# Spartan_Edge_Accelerator_Board_v1_0.net
KiCad netlist of a schematic drawn in EAGLE
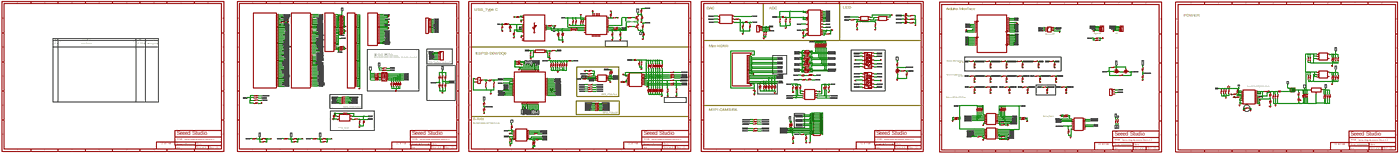
[diagram p0: schematic, sheet 1, overview]
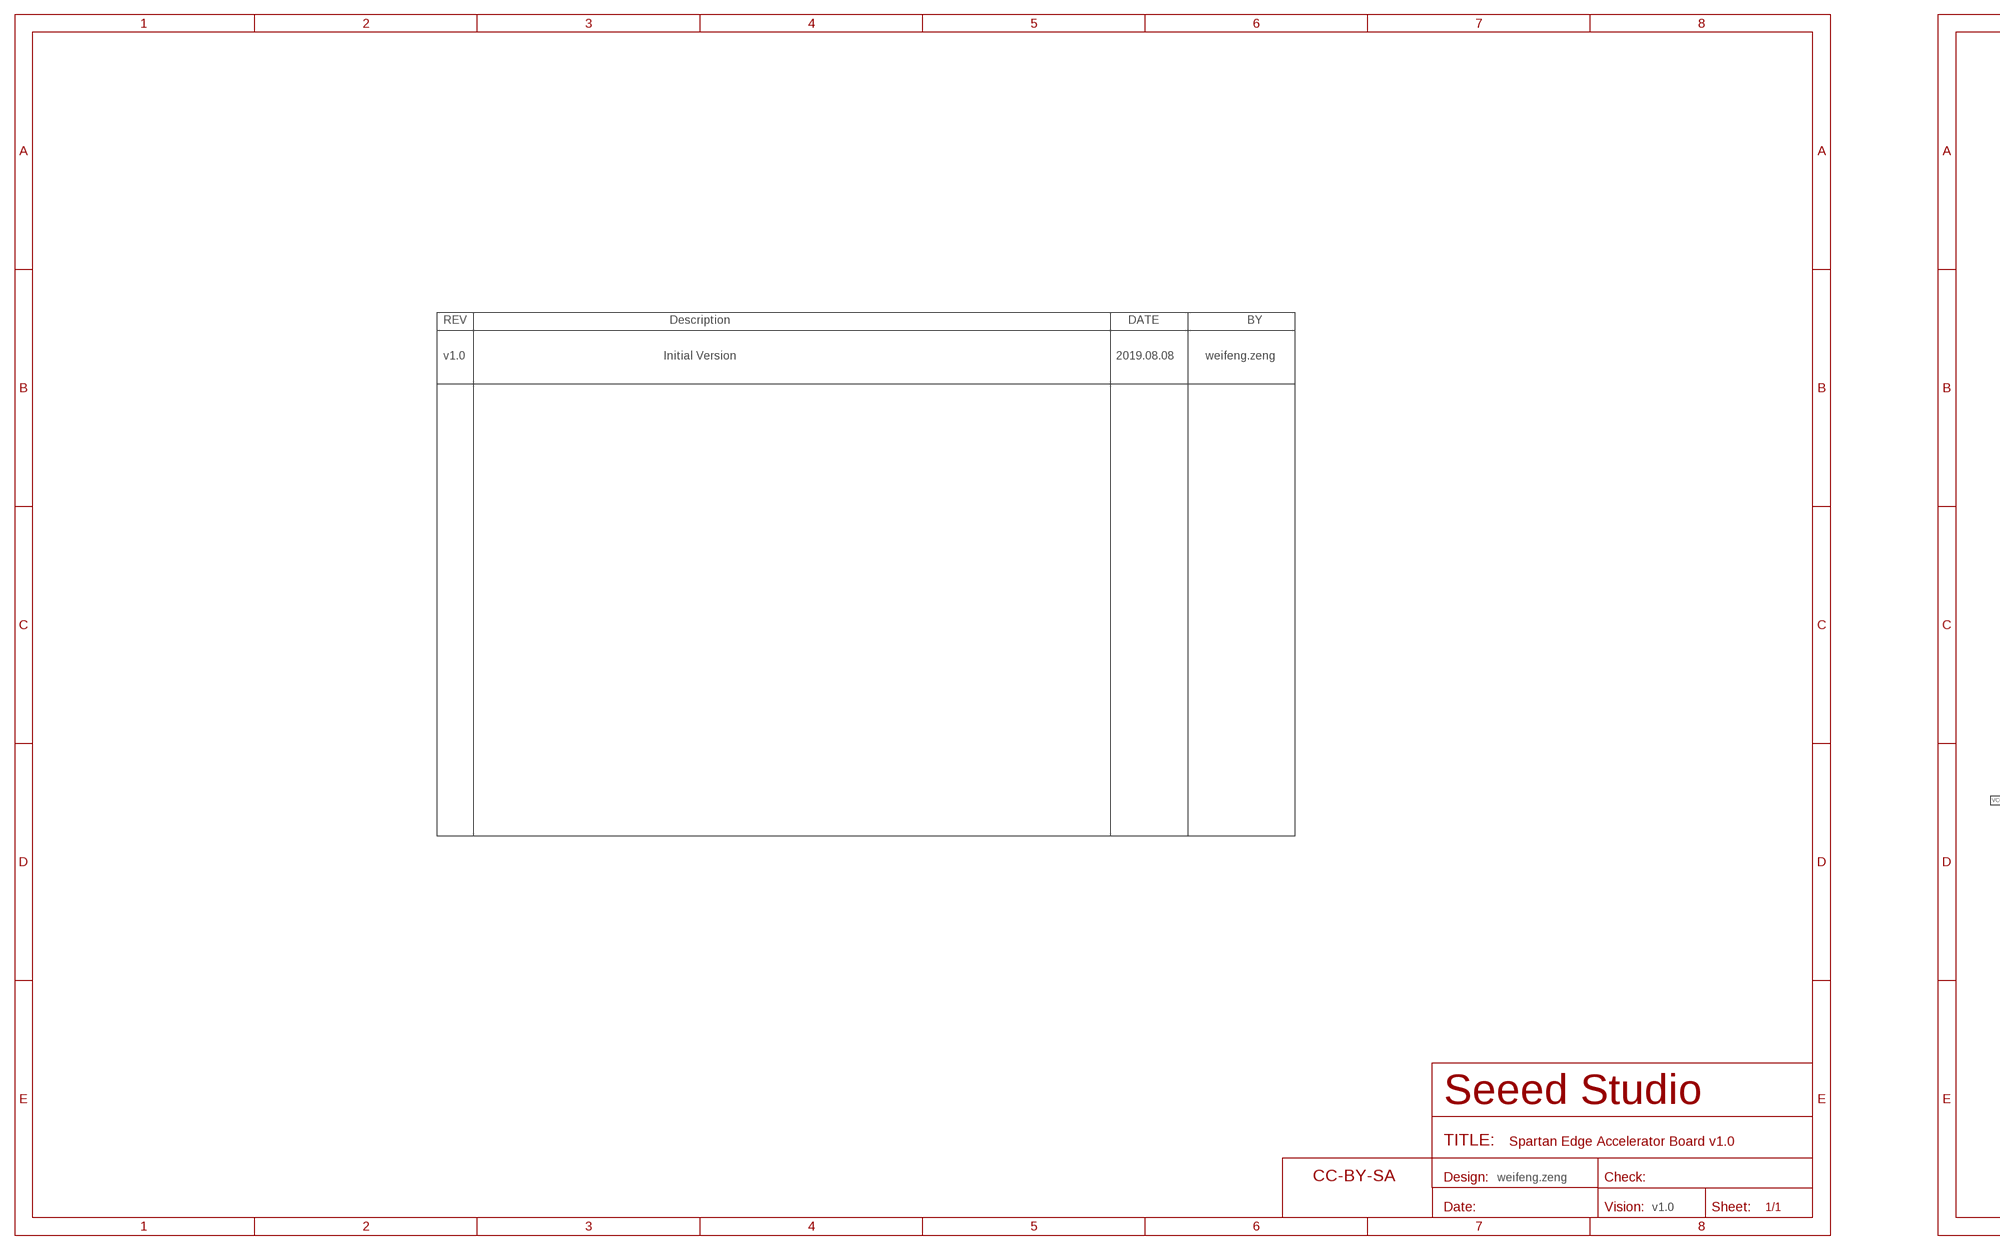
[diagram p1: schematic, sheet 1, part 1 of 7]
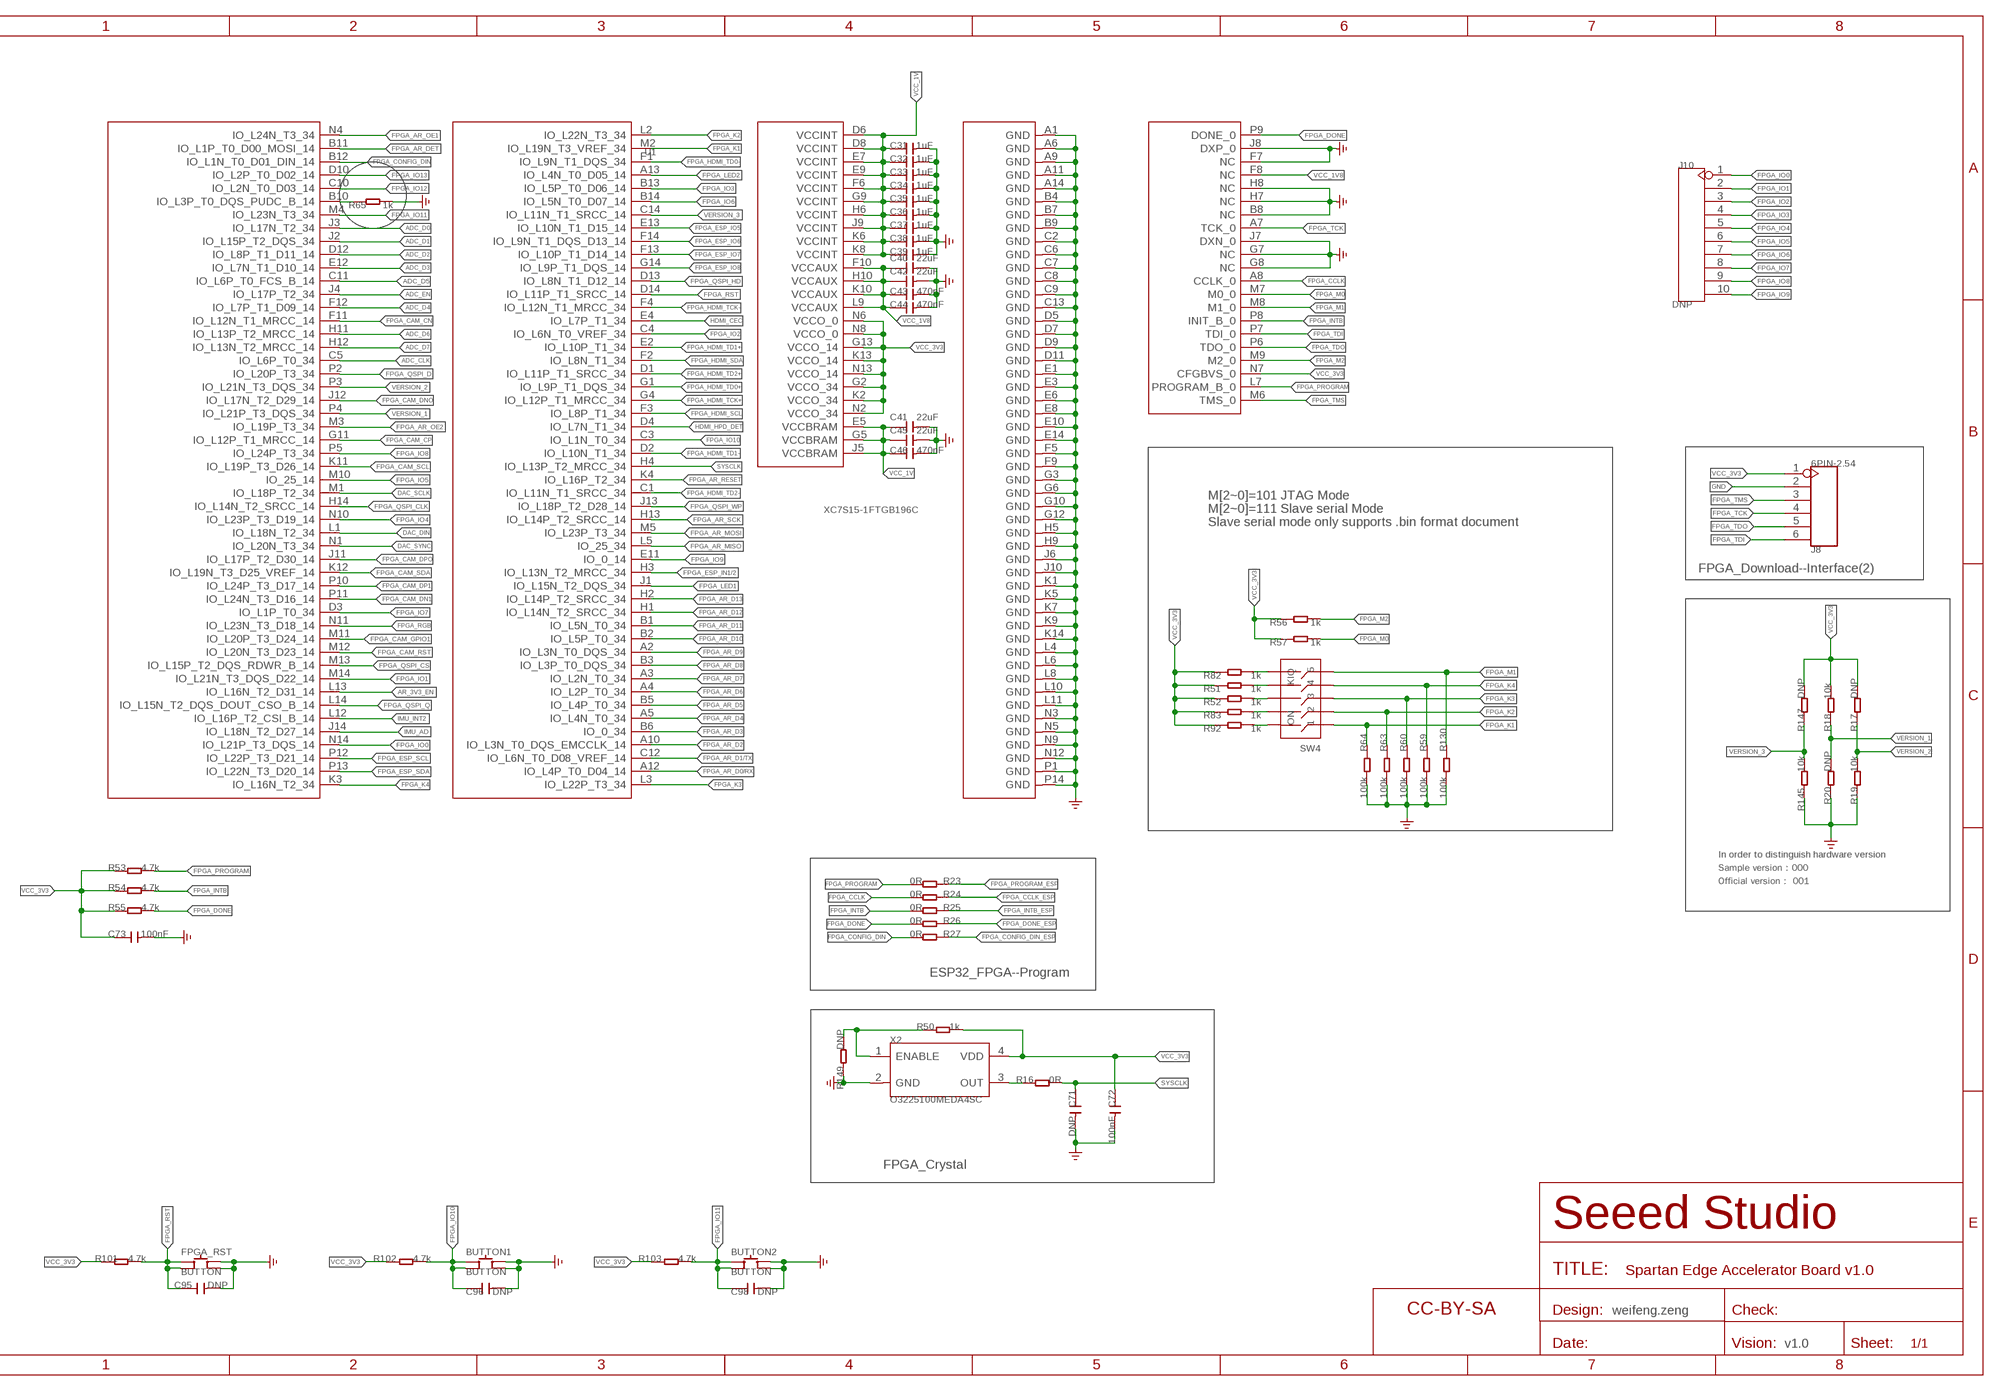
[diagram p2: schematic, sheet 1, part 2 of 7]
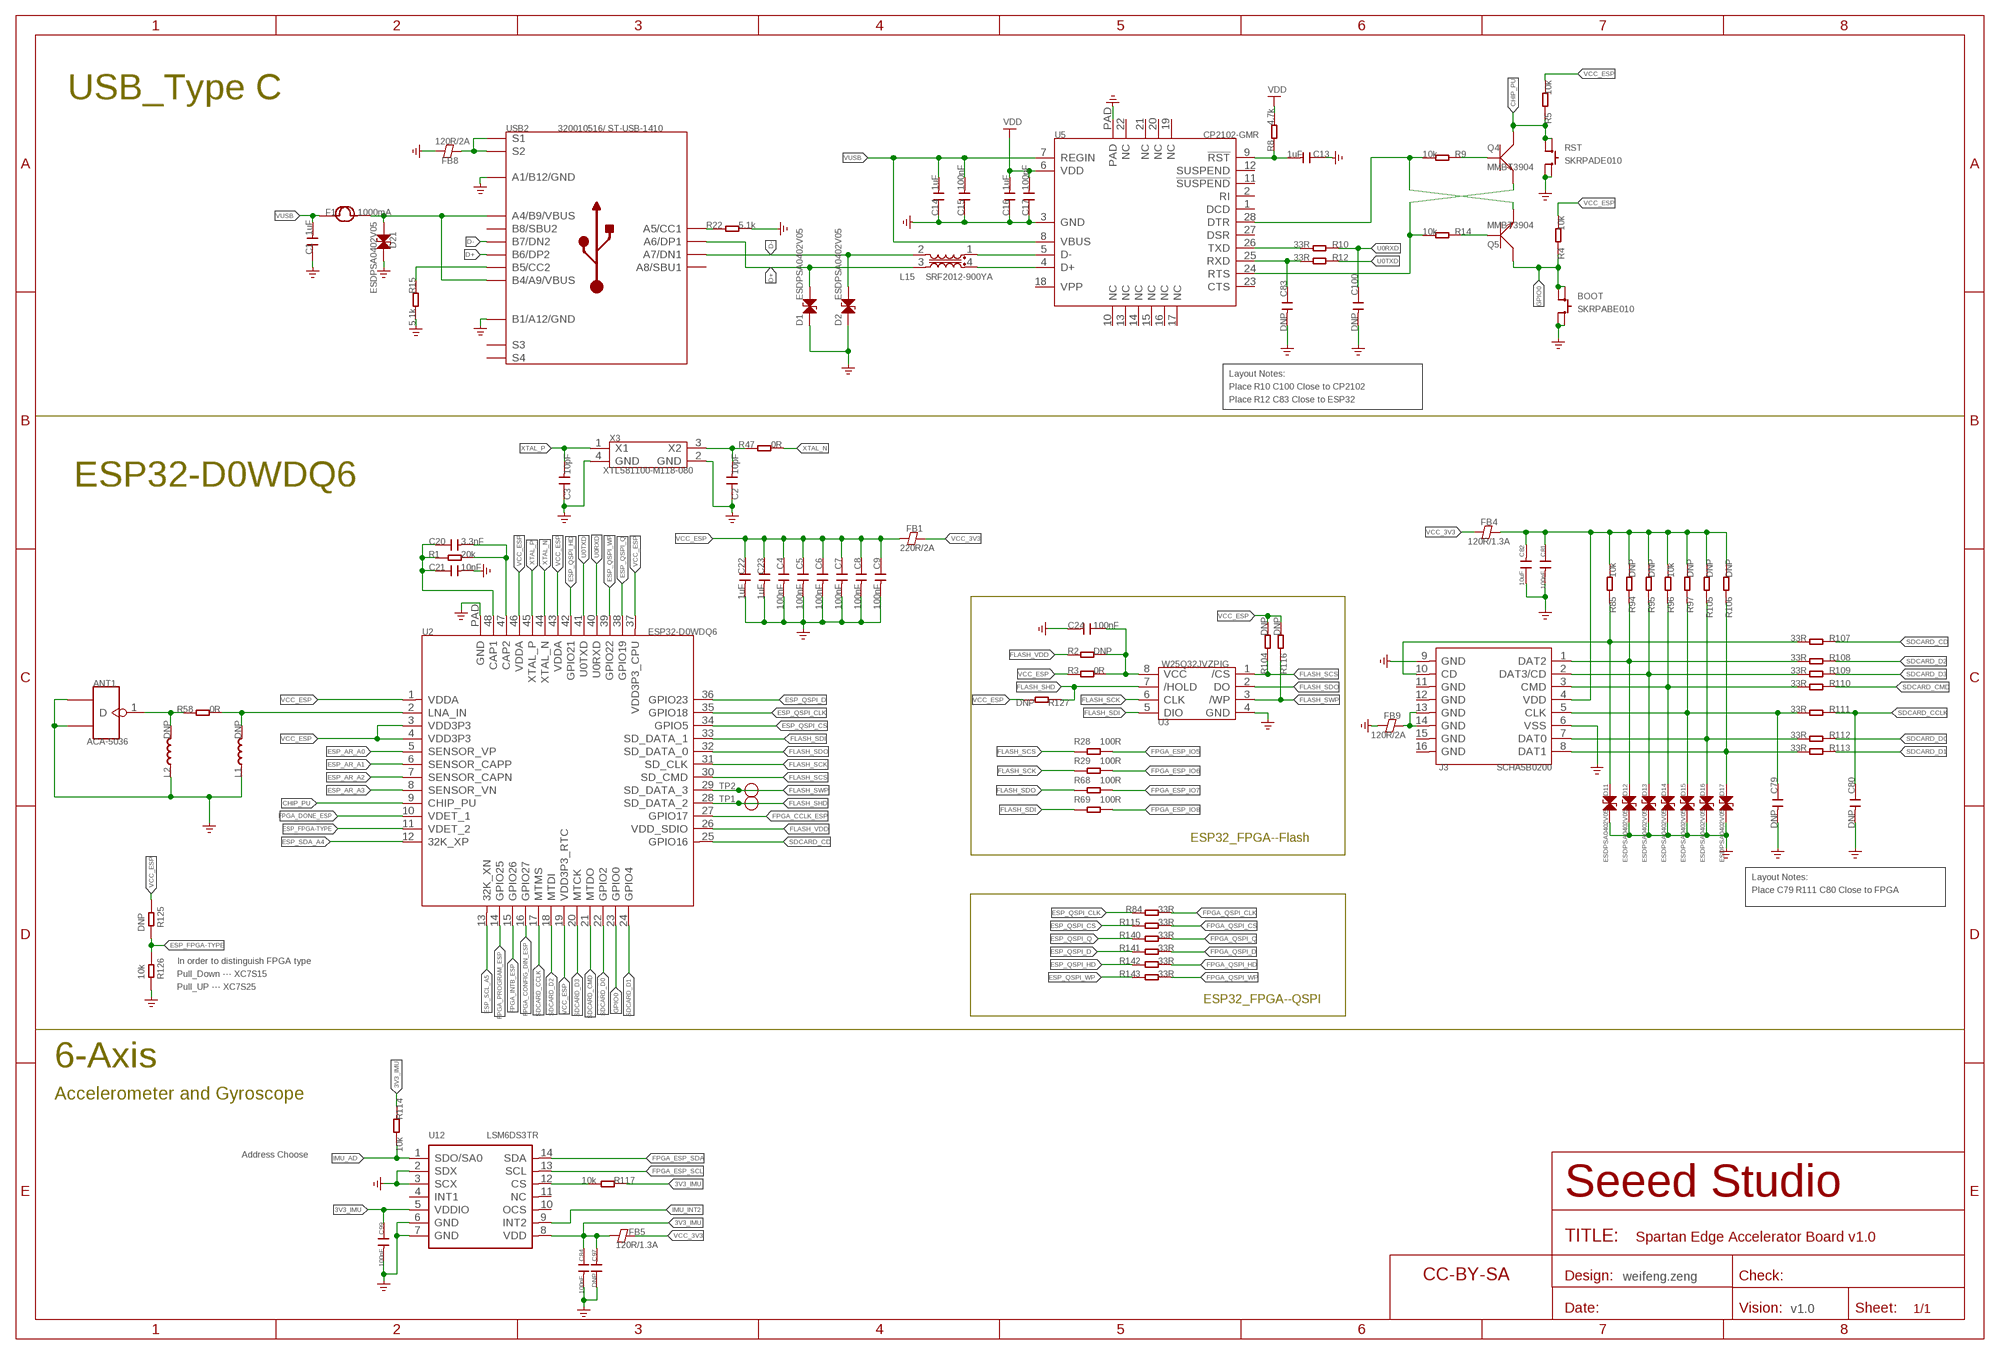
[diagram p3: schematic, sheet 1, part 3 of 7]
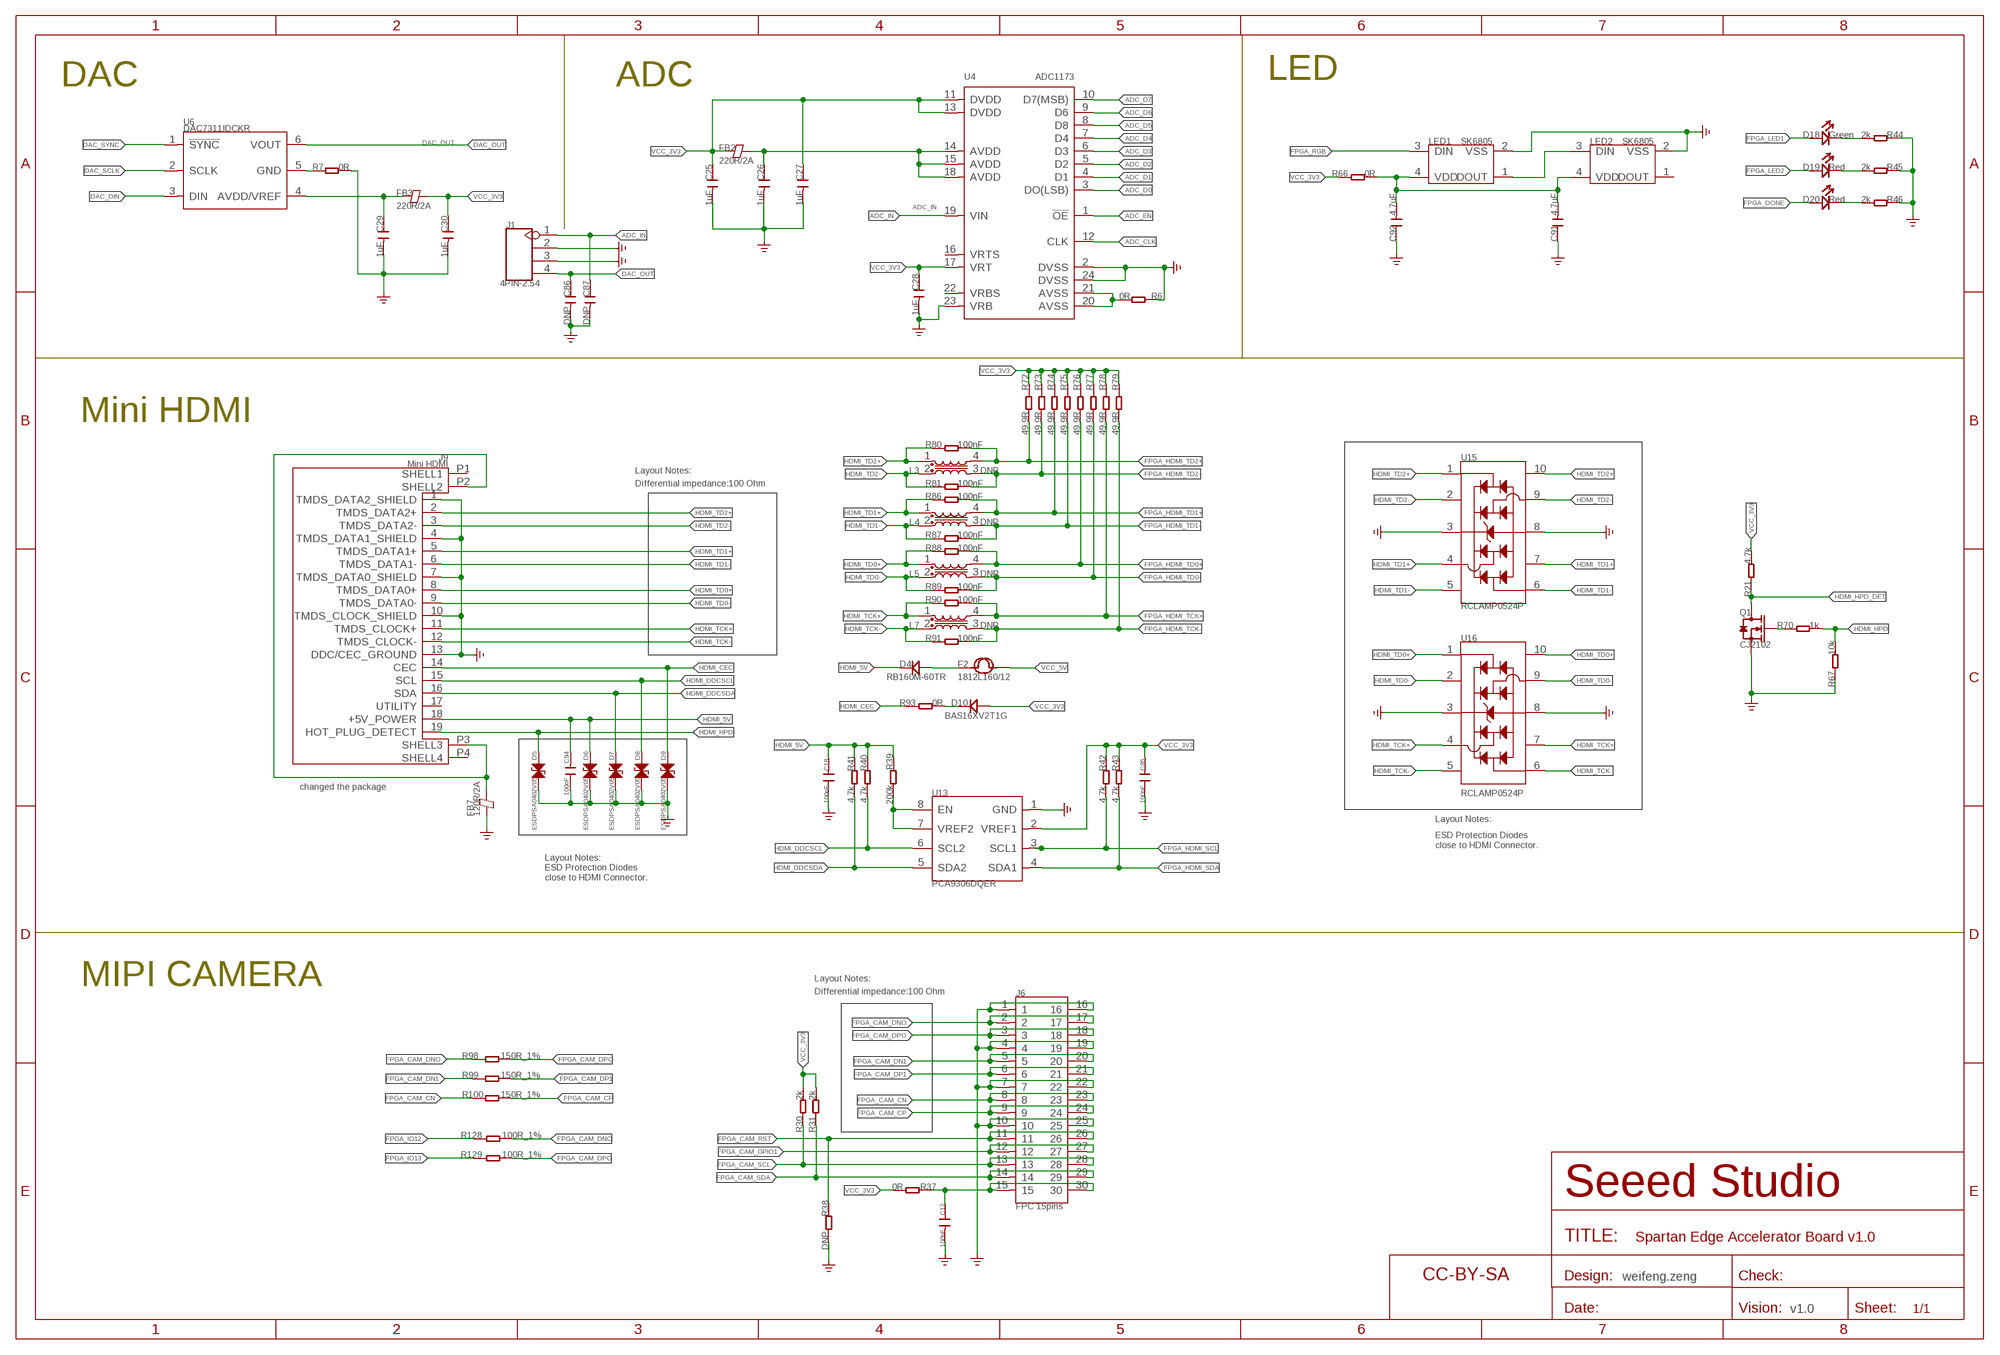
[diagram p4: schematic, sheet 1, part 4 of 7]
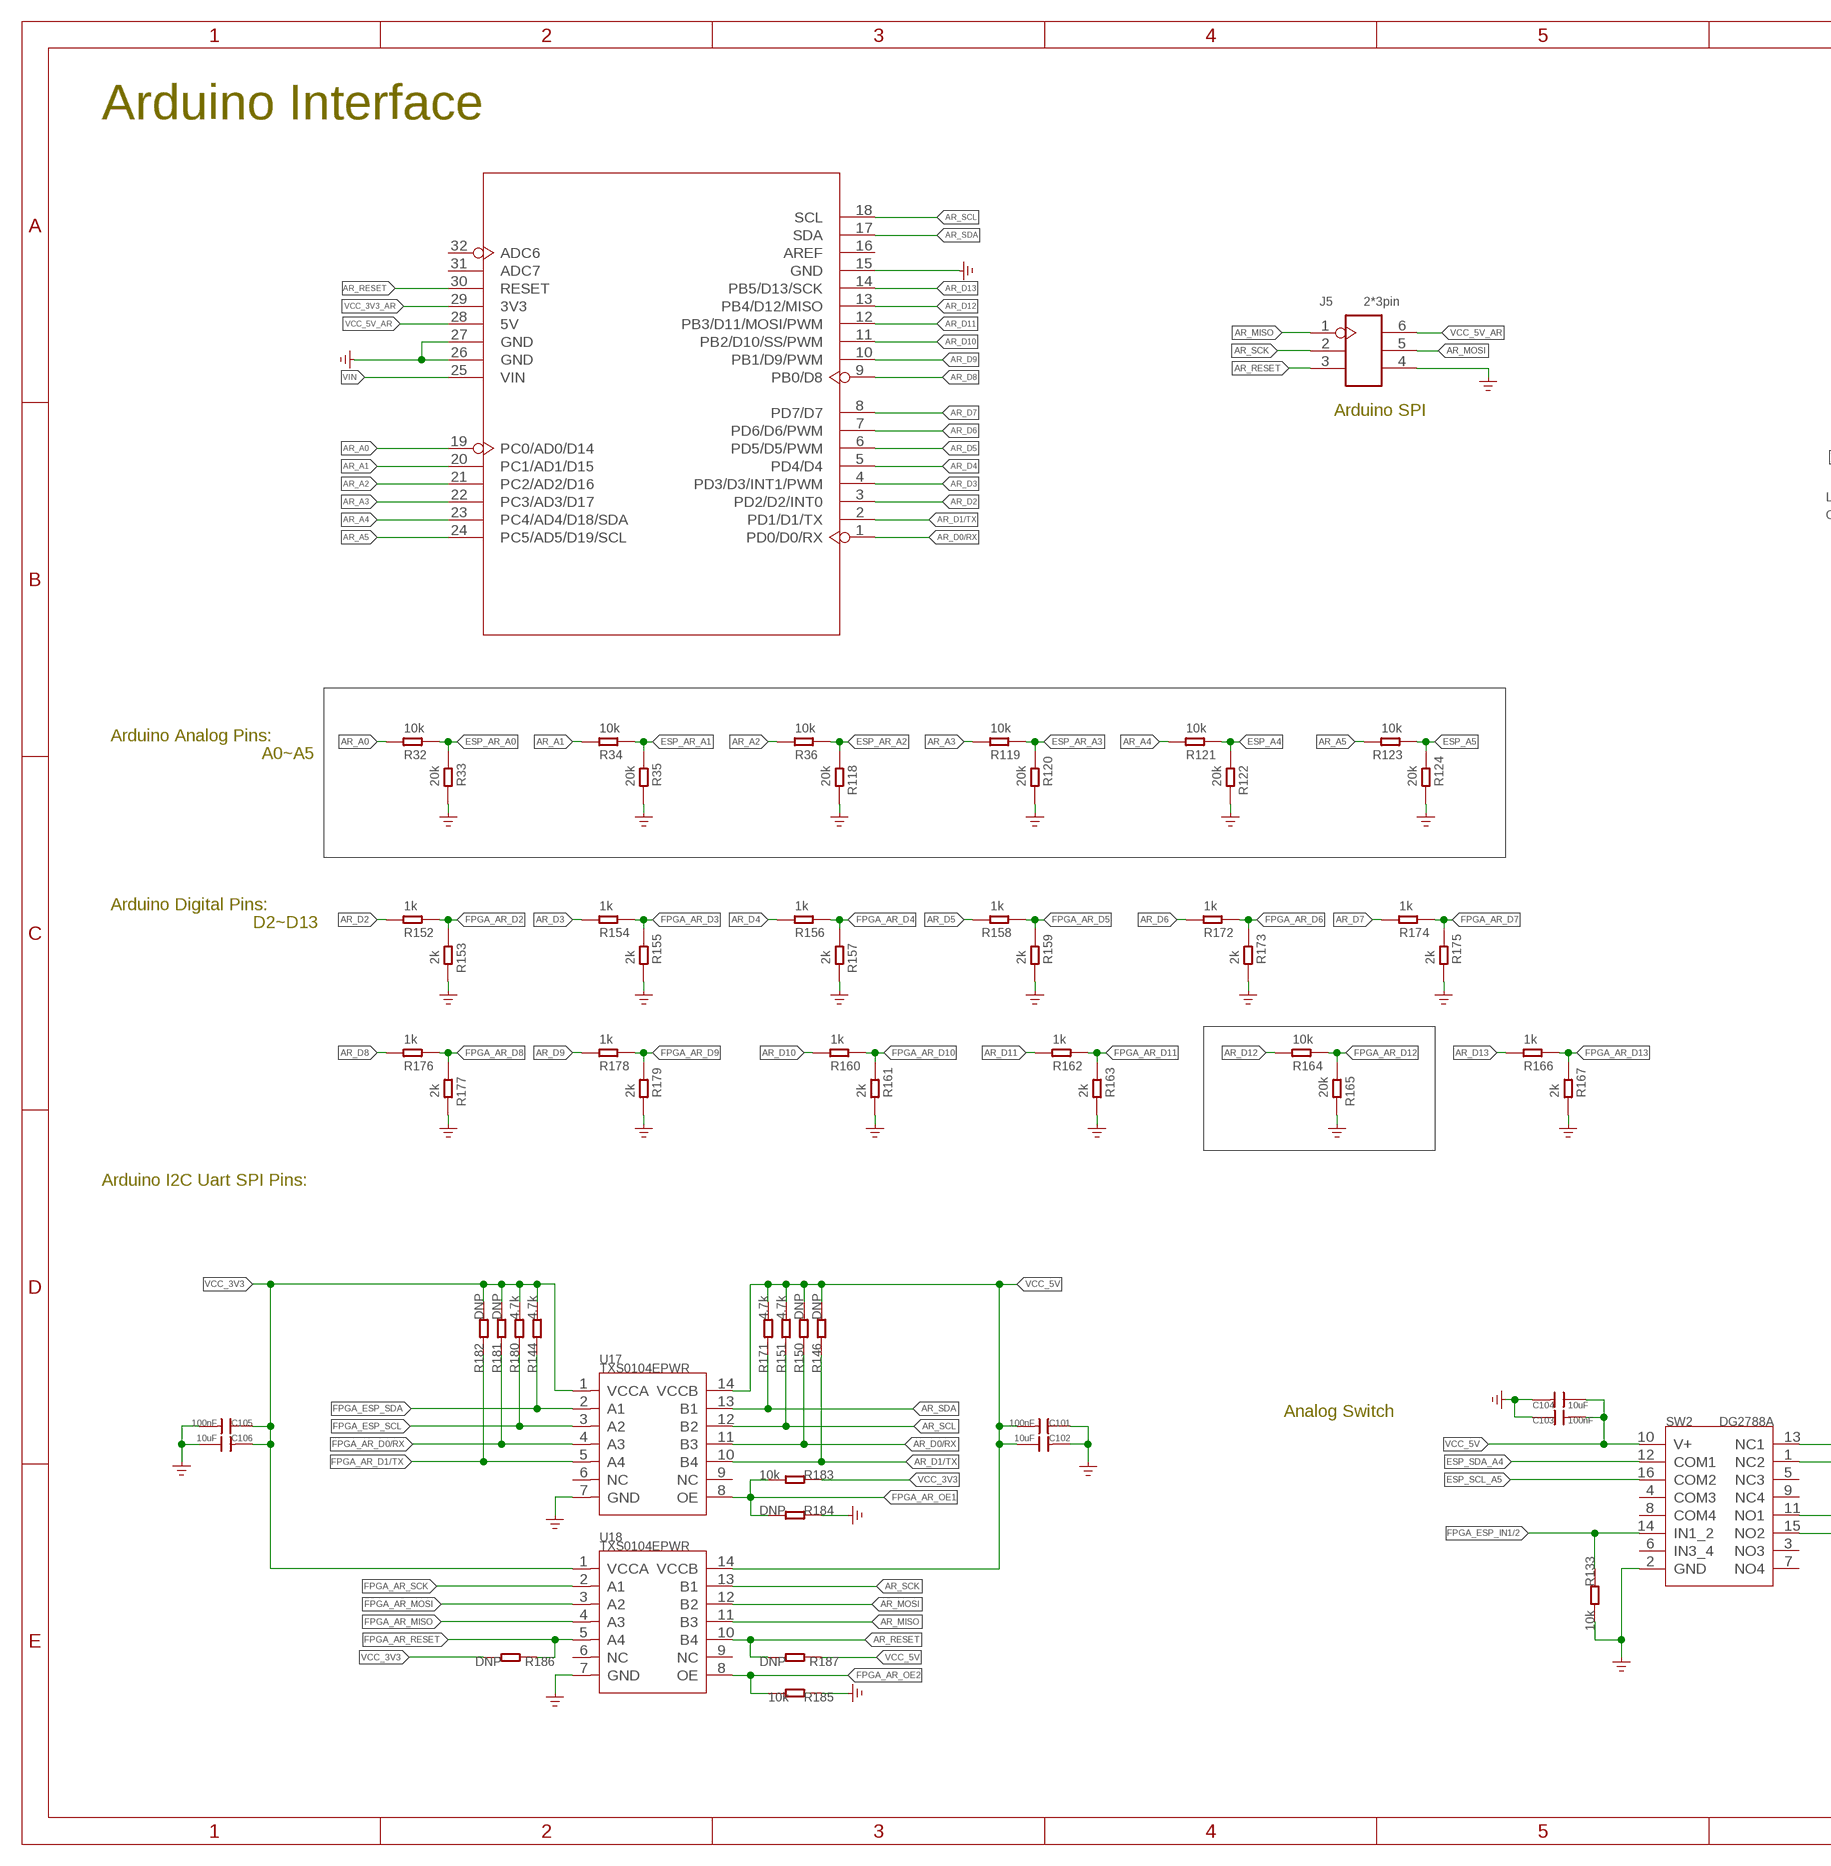
[diagram p5: schematic, sheet 1, part 5 of 7]
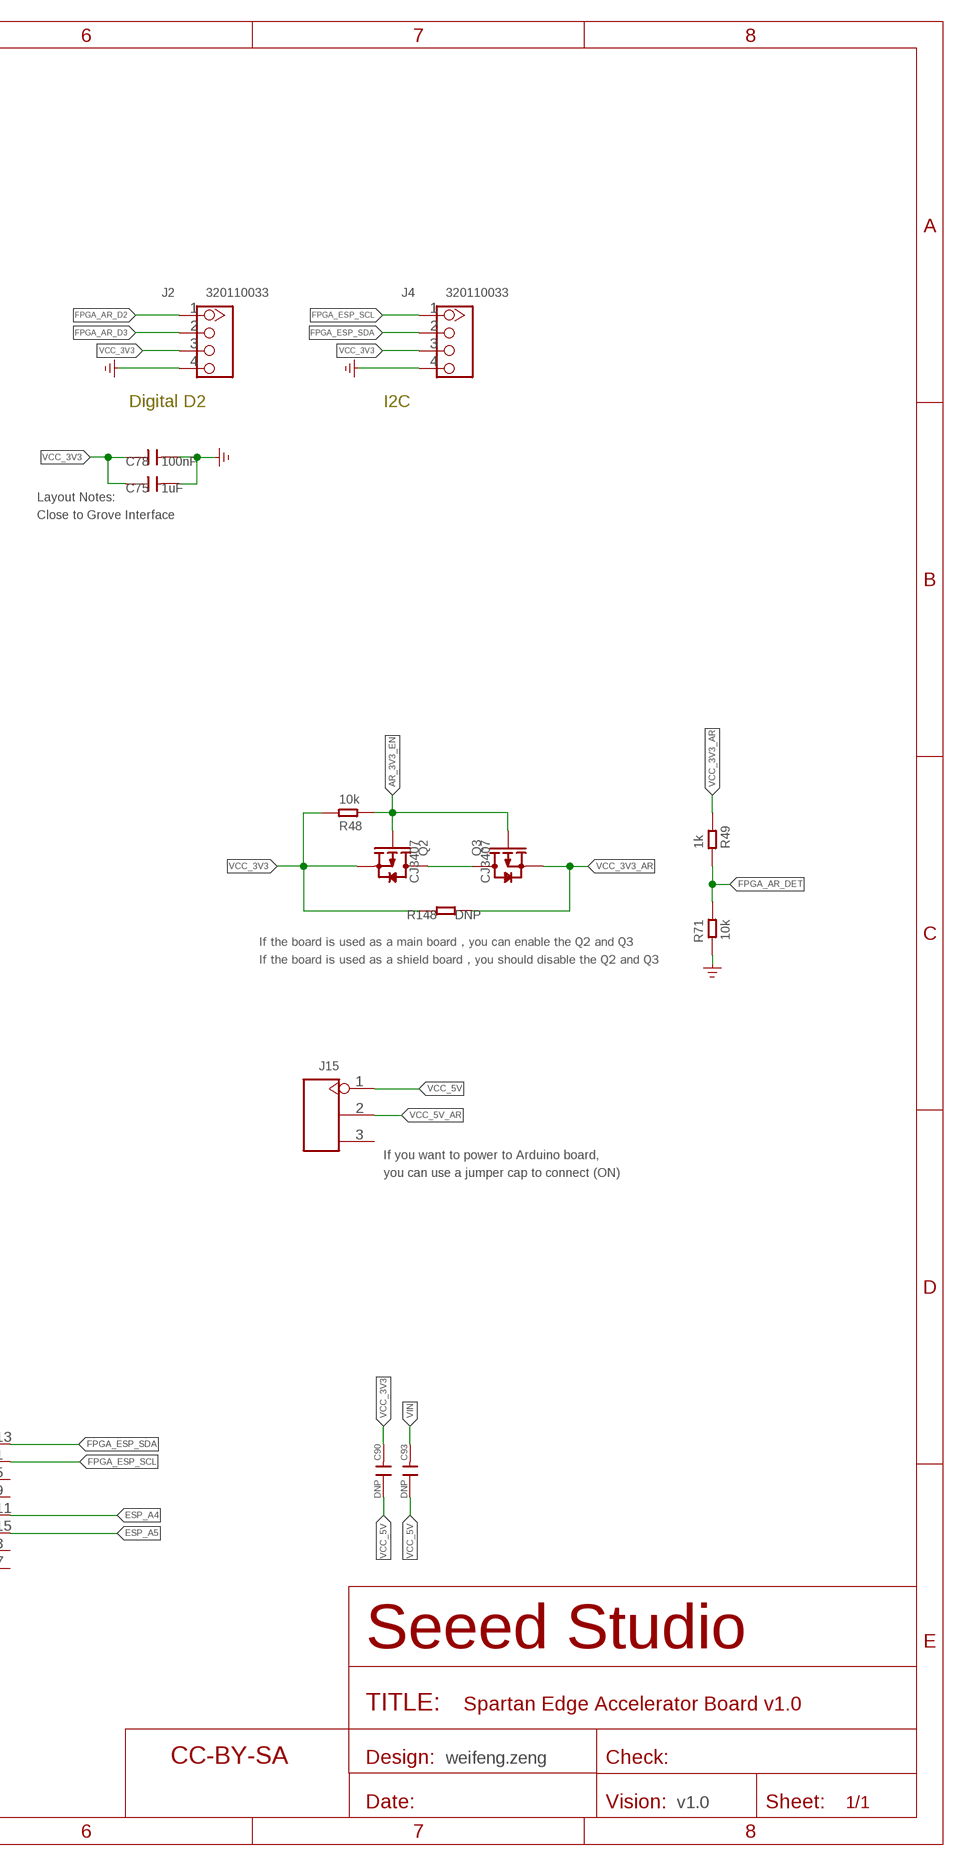
[diagram p6: schematic, sheet 1, part 6 of 7]
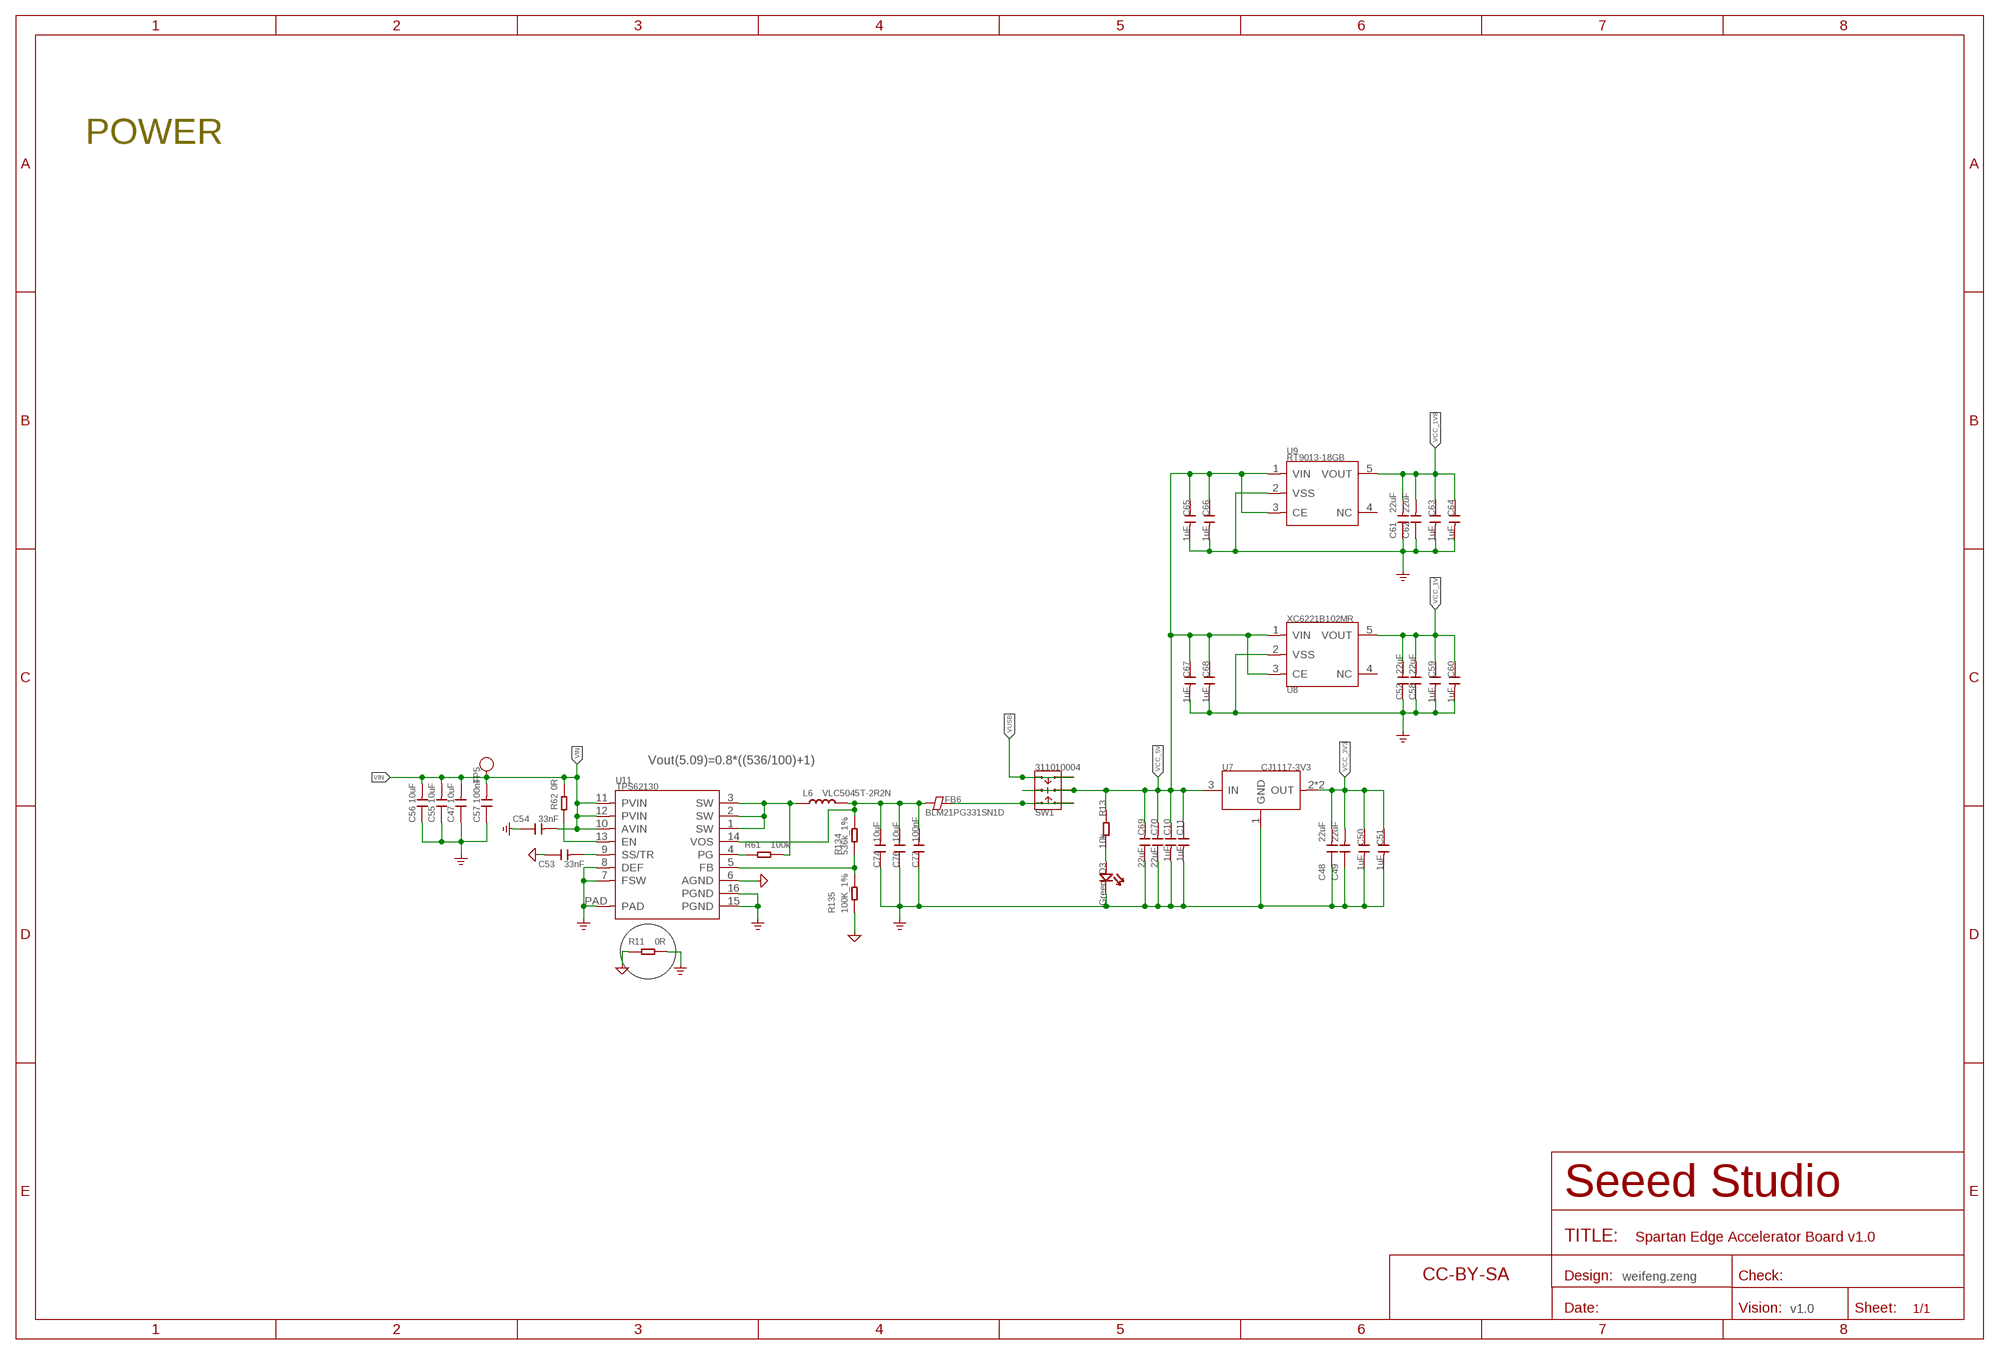
[diagram p7: schematic, sheet 1, part 7 of 7]

(export (version "E")
  (design (tool "Eeschema 10.0.6"))
  (components
    (comp (ref "ANT1")
      (value "ACA-5036")
      (footprint "eagle-import:ANT3-SMD-5.2X3.7X0.7MM")
      (fields (field (name "MPN") "ACD-5036-A3-CC-S"))
      (libsource (lib "eagle-import") (part "ANTENNA-ACD5036"))
    )
    (comp (ref "BOOT")
      (value "SKRPABE010")
      (footprint "eagle-import:SW4P-SMD-4.5X3.2X2.5MM")
      (libsource (lib "eagle-import") (part "BUTTON-4P-4.5X3.2"))
    )
    (comp (ref "BUTTON1")
      (value "BUTTON")
      (footprint "eagle-import:SW4P-SMD-4.5X3.2X2.5MM")
      (libsource (lib "eagle-import") (part "BUTTON-4P-4.5X3.2"))
    )
    (comp (ref "BUTTON2")
      (value "BUTTON")
      (footprint "eagle-import:SW4P-SMD-4.5X3.2X2.5MM")
      (libsource (lib "eagle-import") (part "BUTTON-4P-4.5X3.2"))
    )
    (comp (ref "C1")
      (value "1uF")
      (footprint "eagle-import:C0402")
      (libsource (lib "eagle-import") (part "CAP-0402"))
    )
    (comp (ref "C2")
      (value "10pF")
      (footprint "eagle-import:C0402")
      (libsource (lib "eagle-import") (part "CAP-0402"))
    )
    (comp (ref "C3")
      (value "10pF")
      (footprint "eagle-import:C0402")
      (libsource (lib "eagle-import") (part "CAP-0402"))
    )
    (comp (ref "C4")
      (value "100nF")
      (footprint "eagle-import:C0402")
      (libsource (lib "eagle-import") (part "CAP-0402"))
    )
    (comp (ref "C5")
      (value "100nF")
      (footprint "eagle-import:C0402")
      (libsource (lib "eagle-import") (part "CAP-0402"))
    )
    (comp (ref "C6")
      (value "100nF")
      (footprint "eagle-import:C0402")
      (libsource (lib "eagle-import") (part "CAP-0402"))
    )
    (comp (ref "C7")
      (value "100nF")
      (footprint "eagle-import:C0402")
      (libsource (lib "eagle-import") (part "CAP-0402"))
    )
    (comp (ref "C8")
      (value "100nF")
      (footprint "eagle-import:C0402")
      (libsource (lib "eagle-import") (part "CAP-0402"))
    )
    (comp (ref "C9")
      (value "100nF")
      (footprint "eagle-import:C0402")
      (libsource (lib "eagle-import") (part "CAP-0402"))
    )
    (comp (ref "C10")
      (value "1uF")
      (footprint "eagle-import:C0402")
      (libsource (lib "eagle-import") (part "CAP-0402"))
    )
    (comp (ref "C11")
      (value "1uF")
      (footprint "eagle-import:C0402")
      (libsource (lib "eagle-import") (part "CAP-0402"))
    )
    (comp (ref "C12")
      (value "100nF")
      (footprint "eagle-import:C0402")
      (libsource (lib "eagle-import") (part "CAP-0402"))
    )
    (comp (ref "C13")
      (value "1uF")
      (footprint "eagle-import:C0402")
      (libsource (lib "eagle-import") (part "CAP-0402"))
    )
    (comp (ref "C14")
      (value "1uF")
      (footprint "eagle-import:C0402")
      (libsource (lib "eagle-import") (part "CAP-0402"))
    )
    (comp (ref "C15")
      (value "100nF")
      (footprint "eagle-import:C0402")
      (libsource (lib "eagle-import") (part "CAP-0402"))
    )
    (comp (ref "C16")
      (value "1uF")
      (footprint "eagle-import:C0402")
      (libsource (lib "eagle-import") (part "CAP-0402"))
    )
    (comp (ref "C17")
      (value "100nF")
      (footprint "eagle-import:C0402")
      (libsource (lib "eagle-import") (part "CAP-0402"))
    )
    (comp (ref "C18")
      (value "100nF")
      (footprint "eagle-import:C0603")
      (libsource (lib "eagle-import") (part "CAP-0603"))
    )
    (comp (ref "C20")
      (value "3.3nF")
      (footprint "eagle-import:C0402")
      (libsource (lib "eagle-import") (part "CAP-0402"))
    )
    (comp (ref "C21")
      (value "10nF")
      (footprint "eagle-import:C0402")
      (libsource (lib "eagle-import") (part "CAP-0402"))
    )
    (comp (ref "C22")
      (value "1uF")
      (footprint "eagle-import:C0402")
      (libsource (lib "eagle-import") (part "CAP-0402"))
    )
    (comp (ref "C23")
      (value "1uF")
      (footprint "eagle-import:C0402")
      (libsource (lib "eagle-import") (part "CAP-0402"))
    )
    (comp (ref "C24")
      (value "100nF")
      (footprint "eagle-import:C0402")
      (libsource (lib "eagle-import") (part "CAP-0402"))
    )
    (comp (ref "C25")
      (value "1uF")
      (footprint "eagle-import:C0402")
      (libsource (lib "eagle-import") (part "CAP-0402"))
    )
    (comp (ref "C26")
      (value "1uF")
      (footprint "eagle-import:C0402")
      (libsource (lib "eagle-import") (part "CAP-0402"))
    )
    (comp (ref "C27")
      (value "1uF")
      (footprint "eagle-import:C0402")
      (libsource (lib "eagle-import") (part "CAP-0402"))
    )
    (comp (ref "C28")
      (value "1uF")
      (footprint "eagle-import:C0402")
      (libsource (lib "eagle-import") (part "CAP-0402"))
    )
    (comp (ref "C29")
      (value "1uF")
      (footprint "eagle-import:C0402")
      (libsource (lib "eagle-import") (part "CAP-0402"))
    )
    (comp (ref "C30")
      (value "1uF")
      (footprint "eagle-import:C0402")
      (libsource (lib "eagle-import") (part "CAP-0402"))
    )
    (comp (ref "C31")
      (value "1uF")
      (footprint "eagle-import:C0402")
      (libsource (lib "eagle-import") (part "CAP-0402"))
    )
    (comp (ref "C32")
      (value "1uF")
      (footprint "eagle-import:C0402")
      (libsource (lib "eagle-import") (part "CAP-0402"))
    )
    (comp (ref "C33")
      (value "1uF")
      (footprint "eagle-import:C0402")
      (libsource (lib "eagle-import") (part "CAP-0402"))
    )
    (comp (ref "C34")
      (value "1uF")
      (footprint "eagle-import:C0402")
      (libsource (lib "eagle-import") (part "CAP-0402"))
    )
    (comp (ref "C35")
      (value "1uF")
      (footprint "eagle-import:C0402")
      (libsource (lib "eagle-import") (part "CAP-0402"))
    )
    (comp (ref "C36")
      (value "1uF")
      (footprint "eagle-import:C0402")
      (libsource (lib "eagle-import") (part "CAP-0402"))
    )
    (comp (ref "C37")
      (value "1uF")
      (footprint "eagle-import:C0402")
      (libsource (lib "eagle-import") (part "CAP-0402"))
    )
    (comp (ref "C38")
      (value "1uF")
      (footprint "eagle-import:C0402")
      (libsource (lib "eagle-import") (part "CAP-0402"))
    )
    (comp (ref "C39")
      (value "1uF")
      (footprint "eagle-import:C0402")
      (libsource (lib "eagle-import") (part "CAP-0402"))
    )
    (comp (ref "C40")
      (value "22uF")
      (footprint "eagle-import:C1206")
      (libsource (lib "eagle-import") (part "CAP-1206"))
    )
    (comp (ref "C41")
      (value "22uF")
      (footprint "eagle-import:C1206")
      (libsource (lib "eagle-import") (part "CAP-1206"))
    )
    (comp (ref "C42")
      (value "22uF")
      (footprint "eagle-import:C1206")
      (libsource (lib "eagle-import") (part "CAP-1206"))
    )
    (comp (ref "C43")
      (value "470nF")
      (footprint "eagle-import:C0402")
      (libsource (lib "eagle-import") (part "CAP-0402"))
    )
    (comp (ref "C44")
      (value "470nF")
      (footprint "eagle-import:C0402")
      (libsource (lib "eagle-import") (part "CAP-0402"))
    )
    (comp (ref "C45")
      (value "22uF")
      (footprint "eagle-import:C1206")
      (libsource (lib "eagle-import") (part "CAP-1206"))
    )
    (comp (ref "C46")
      (value "470nF")
      (footprint "eagle-import:C0402")
      (libsource (lib "eagle-import") (part "CAP-0402"))
    )
    (comp (ref "C47")
      (value "10uF")
      (footprint "eagle-import:C0805")
      (libsource (lib "eagle-import") (part "CAP-0805"))
    )
    (comp (ref "C48")
      (value "22uF")
      (footprint "eagle-import:C1206")
      (libsource (lib "eagle-import") (part "CAP-1206"))
    )
    (comp (ref "C49")
      (value "22uF")
      (footprint "eagle-import:C1206")
      (libsource (lib "eagle-import") (part "CAP-1206"))
    )
    (comp (ref "C50")
      (value "1uF")
      (footprint "eagle-import:C0402")
      (libsource (lib "eagle-import") (part "CAP-0402"))
    )
    (comp (ref "C51")
      (value "1uF")
      (footprint "eagle-import:C0402")
      (libsource (lib "eagle-import") (part "CAP-0402"))
    )
    (comp (ref "C52")
      (value "22uF")
      (footprint "eagle-import:C1206")
      (libsource (lib "eagle-import") (part "CAP-1206"))
    )
    (comp (ref "C53")
      (value "33nF")
      (footprint "eagle-import:C0603")
      (libsource (lib "eagle-import") (part "CAP-0603"))
    )
    (comp (ref "C54")
      (value "33nF")
      (footprint "eagle-import:C0603")
      (libsource (lib "eagle-import") (part "CAP-0603"))
    )
    (comp (ref "C55")
      (value "10uF")
      (footprint "eagle-import:C0805")
      (libsource (lib "eagle-import") (part "CAP-0805"))
    )
    (comp (ref "C56")
      (value "10uF")
      (footprint "eagle-import:C0805")
      (libsource (lib "eagle-import") (part "CAP-0805"))
    )
    (comp (ref "C57")
      (value "100nF")
      (footprint "eagle-import:C0603")
      (libsource (lib "eagle-import") (part "CAP-0603"))
    )
    (comp (ref "C58")
      (value "22uF")
      (footprint "eagle-import:C1206")
      (libsource (lib "eagle-import") (part "CAP-1206"))
    )
    (comp (ref "C59")
      (value "1uF")
      (footprint "eagle-import:C0402")
      (libsource (lib "eagle-import") (part "CAP-0402"))
    )
    (comp (ref "C60")
      (value "1uF")
      (footprint "eagle-import:C0402")
      (libsource (lib "eagle-import") (part "CAP-0402"))
    )
    (comp (ref "C61")
      (value "22uF")
      (footprint "eagle-import:C1206")
      (libsource (lib "eagle-import") (part "CAP-1206"))
    )
    (comp (ref "C62")
      (value "22uF")
      (footprint "eagle-import:C1206")
      (libsource (lib "eagle-import") (part "CAP-1206"))
    )
    (comp (ref "C63")
      (value "1uF")
      (footprint "eagle-import:C0402")
      (libsource (lib "eagle-import") (part "CAP-0402"))
    )
    (comp (ref "C64")
      (value "1uF")
      (footprint "eagle-import:C0402")
      (libsource (lib "eagle-import") (part "CAP-0402"))
    )
    (comp (ref "C65")
      (value "1uF")
      (footprint "eagle-import:C0402")
      (libsource (lib "eagle-import") (part "CAP-0402"))
    )
    (comp (ref "C66")
      (value "1uF")
      (footprint "eagle-import:C0402")
      (libsource (lib "eagle-import") (part "CAP-0402"))
    )
    (comp (ref "C67")
      (value "1uF")
      (footprint "eagle-import:C0402")
      (libsource (lib "eagle-import") (part "CAP-0402"))
    )
    (comp (ref "C68")
      (value "1uF")
      (footprint "eagle-import:C0402")
      (libsource (lib "eagle-import") (part "CAP-0402"))
    )
    (comp (ref "C69")
      (value "22uF")
      (footprint "eagle-import:C1206")
      (libsource (lib "eagle-import") (part "CAP-1206"))
    )
    (comp (ref "C70")
      (value "22uF")
      (footprint "eagle-import:C1206")
      (libsource (lib "eagle-import") (part "CAP-1206"))
    )
    (comp (ref "C71")
      (value "DNP")
      (footprint "eagle-import:C0402")
      (libsource (lib "eagle-import") (part "CAP-0402"))
    )
    (comp (ref "C72")
      (value "100nF")
      (footprint "eagle-import:C0402")
      (libsource (lib "eagle-import") (part "CAP-0402"))
    )
    (comp (ref "C73")
      (value "100nF")
      (footprint "eagle-import:C0402")
      (libsource (lib "eagle-import") (part "CAP-0402"))
    )
    (comp (ref "C74")
      (value "10uF")
      (footprint "eagle-import:C0805")
      (libsource (lib "eagle-import") (part "CAP-0805"))
    )
    (comp (ref "C75")
      (value "1uF")
      (footprint "eagle-import:C0402")
      (libsource (lib "eagle-import") (part "CAP-0402"))
    )
    (comp (ref "C76")
      (value "10uF")
      (footprint "eagle-import:C0805")
      (libsource (lib "eagle-import") (part "CAP-0805"))
    )
    (comp (ref "C77")
      (value "100nF")
      (footprint "eagle-import:C0603")
      (libsource (lib "eagle-import") (part "CAP-0603"))
    )
    (comp (ref "C78")
      (value "100nF")
      (footprint "eagle-import:C0402")
      (libsource (lib "eagle-import") (part "CAP-0402"))
    )
    (comp (ref "C79")
      (value "DNP")
      (footprint "eagle-import:C0402")
      (libsource (lib "eagle-import") (part "CAP-0402"))
    )
    (comp (ref "C80")
      (value "DNP")
      (footprint "eagle-import:C0402")
      (libsource (lib "eagle-import") (part "CAP-0402"))
    )
    (comp (ref "C81")
      (value "100nF")
      (footprint "eagle-import:C0402")
      (libsource (lib "eagle-import") (part "CAP-0402"))
    )
    (comp (ref "C82")
      (value "10uF")
      (footprint "eagle-import:C0603")
      (libsource (lib "eagle-import") (part "CAP-0603"))
    )
    (comp (ref "C83")
      (value "DNP")
      (footprint "eagle-import:C0402")
      (libsource (lib "eagle-import") (part "CAP-0402"))
    )
    (comp (ref "C84")
      (value "100nF")
      (footprint "eagle-import:C0402")
      (libsource (lib "eagle-import") (part "CAP-0402"))
    )
    (comp (ref "C85")
      (value "100nF")
      (footprint "eagle-import:C0603")
      (libsource (lib "eagle-import") (part "CAP-0603"))
    )
    (comp (ref "C86")
      (value "DNP")
      (footprint "eagle-import:C0402")
      (libsource (lib "eagle-import") (part "CAP-0402"))
    )
    (comp (ref "C87")
      (value "DNP")
      (footprint "eagle-import:C0402")
      (libsource (lib "eagle-import") (part "CAP-0402"))
    )
    (comp (ref "C90")
      (value "DNP")
      (footprint "eagle-import:C0603")
      (libsource (lib "eagle-import") (part "CAP-0603"))
    )
    (comp (ref "C91")
      (value "4.7uF")
      (footprint "eagle-import:C0603")
      (libsource (lib "eagle-import") (part "CAP-0603"))
    )
    (comp (ref "C92")
      (value "4.7uF")
      (footprint "eagle-import:C0603")
      (libsource (lib "eagle-import") (part "CAP-0603"))
    )
    (comp (ref "C93")
      (value "DNP")
      (footprint "eagle-import:C0603")
      (libsource (lib "eagle-import") (part "CAP-0603"))
    )
    (comp (ref "C94")
      (value "100nF")
      (footprint "eagle-import:C0603")
      (libsource (lib "eagle-import") (part "CAP-0603"))
    )
    (comp (ref "C95")
      (value "DNP")
      (footprint "eagle-import:C0402")
      (libsource (lib "eagle-import") (part "CAP-0402"))
    )
    (comp (ref "C96")
      (value "DNP")
      (footprint "eagle-import:C0402")
      (libsource (lib "eagle-import") (part "CAP-0402"))
    )
    (comp (ref "C97")
      (value "DNP")
      (footprint "eagle-import:C0603")
      (libsource (lib "eagle-import") (part "CAP-0603"))
    )
    (comp (ref "C98")
      (value "DNP")
      (footprint "eagle-import:C0402")
      (libsource (lib "eagle-import") (part "CAP-0402"))
    )
    (comp (ref "C99")
      (value "100nF")
      (footprint "eagle-import:C0402")
      (libsource (lib "eagle-import") (part "CAP-0402"))
    )
    (comp (ref "C100")
      (value "DNP")
      (footprint "eagle-import:C0402")
      (libsource (lib "eagle-import") (part "CAP-0402"))
    )
    (comp (ref "C101")
      (value "100nF")
      (footprint "eagle-import:C0402")
      (libsource (lib "eagle-import") (part "CAP-0402"))
    )
    (comp (ref "C102")
      (value "10uF")
      (footprint "eagle-import:C0603")
      (libsource (lib "eagle-import") (part "CAP-0603"))
    )
    (comp (ref "C103")
      (value "100nF")
      (footprint "eagle-import:C0402")
      (libsource (lib "eagle-import") (part "CAP-0402"))
    )
    (comp (ref "C104")
      (value "10uF")
      (footprint "eagle-import:C0603")
      (libsource (lib "eagle-import") (part "CAP-0603"))
    )
    (comp (ref "C105")
      (value "100nF")
      (footprint "eagle-import:C0402")
      (libsource (lib "eagle-import") (part "CAP-0402"))
    )
    (comp (ref "C106")
      (value "10uF")
      (footprint "eagle-import:C0603")
      (libsource (lib "eagle-import") (part "CAP-0603"))
    )
    (comp (ref "D1")
      (value "ESDPSA0402V05")
      (footprint "eagle-import:ESD-0402")
      (libsource (lib "eagle-import") (part "D-ESD-2P-DOUBLE-0402"))
    )
    (comp (ref "D2")
      (value "ESDPSA0402V05")
      (footprint "eagle-import:ESD-0402")
      (libsource (lib "eagle-import") (part "D-ESD-2P-DOUBLE-0402"))
    )
    (comp (ref "D3")
      (value "Green")
      (footprint "eagle-import:LED-0402")
      (libsource (lib "eagle-import") (part "LED-0402"))
    )
    (comp (ref "D4")
      (value "RB160M-60TR")
      (footprint "eagle-import:SOD-123")
      (libsource (lib "eagle-import") (part "DIODE'1206'"))
    )
    (comp (ref "D5")
      (value "ESDPSA0402V05")
      (footprint "eagle-import:ESD-0402")
      (libsource (lib "eagle-import") (part "D-ESD-2P-DOUBLE-0402"))
    )
    (comp (ref "D6")
      (value "ESDPSA0402V05")
      (footprint "eagle-import:ESD-0402")
      (libsource (lib "eagle-import") (part "D-ESD-2P-DOUBLE-0402"))
    )
    (comp (ref "D7")
      (value "ESDPSA0402V05")
      (footprint "eagle-import:ESD-0402")
      (libsource (lib "eagle-import") (part "D-ESD-2P-DOUBLE-0402"))
    )
    (comp (ref "D8")
      (value "ESDPSA0402V05")
      (footprint "eagle-import:ESD-0402")
      (libsource (lib "eagle-import") (part "D-ESD-2P-DOUBLE-0402"))
    )
    (comp (ref "D9")
      (value "ESDPSA0402V05")
      (footprint "eagle-import:ESD-0402")
      (libsource (lib "eagle-import") (part "D-ESD-2P-DOUBLE-0402"))
    )
    (comp (ref "D10")
      (value "BAS16XV2T1G")
      (footprint "eagle-import:SOD-523")
      (libsource (lib "eagle-import") (part "DIODE'0603'"))
    )
    (comp (ref "D11")
      (value "ESDPSA0402V05")
      (footprint "eagle-import:ESD-0402")
      (libsource (lib "eagle-import") (part "D-ESD-2P-DOUBLE-0402"))
    )
    (comp (ref "D12")
      (value "ESDPSA0402V05")
      (footprint "eagle-import:ESD-0402")
      (libsource (lib "eagle-import") (part "D-ESD-2P-DOUBLE-0402"))
    )
    (comp (ref "D13")
      (value "ESDPSA0402V05")
      (footprint "eagle-import:ESD-0402")
      (libsource (lib "eagle-import") (part "D-ESD-2P-DOUBLE-0402"))
    )
    (comp (ref "D14")
      (value "ESDPSA0402V05")
      (footprint "eagle-import:ESD-0402")
      (libsource (lib "eagle-import") (part "D-ESD-2P-DOUBLE-0402"))
    )
    (comp (ref "D15")
      (value "ESDPSA0402V05")
      (footprint "eagle-import:ESD-0402")
      (libsource (lib "eagle-import") (part "D-ESD-2P-DOUBLE-0402"))
    )
    (comp (ref "D16")
      (value "ESDPSA0402V05")
      (footprint "eagle-import:ESD-0402")
      (libsource (lib "eagle-import") (part "D-ESD-2P-DOUBLE-0402"))
    )
    (comp (ref "D17")
      (value "ESDPSA0402V05")
      (footprint "eagle-import:ESD-0402")
      (libsource (lib "eagle-import") (part "D-ESD-2P-DOUBLE-0402"))
    )
    (comp (ref "D18")
      (value "Green")
      (footprint "eagle-import:LED-0402")
      (libsource (lib "eagle-import") (part "LED-0402"))
    )
    (comp (ref "D19")
      (value "Red")
      (footprint "eagle-import:LED-0402")
      (libsource (lib "eagle-import") (part "LED-0402"))
    )
    (comp (ref "D20")
      (value "Red")
      (footprint "eagle-import:LED-0402")
      (libsource (lib "eagle-import") (part "LED-0402"))
    )
    (comp (ref "D21")
      (value "ESDPSA0402V05")
      (footprint "eagle-import:ESD-0402")
      (libsource (lib "eagle-import") (part "D-ESD-2P-DOUBLE-0402"))
    )
    (comp (ref "F1")
      (value "1000mA")
      (footprint "eagle-import:F1206")
      (libsource (lib "eagle-import") (part "FUSE'1206'"))
    )
    (comp (ref "F2")
      (value "1812L160/12")
      (footprint "eagle-import:F1812")
      (libsource (lib "eagle-import") (part "FUSE'1812'"))
    )
    (comp (ref "FB1")
      (value "220R/2A")
      (footprint "eagle-import:F0603")
      (libsource (lib "eagle-import") (part "FERRITE-BEAD-0603"))
    )
    (comp (ref "FB2")
      (value "220R/2A")
      (footprint "eagle-import:F0603")
      (libsource (lib "eagle-import") (part "FERRITE-BEAD-0603"))
    )
    (comp (ref "FB3")
      (value "220R/2A")
      (footprint "eagle-import:F0603")
      (libsource (lib "eagle-import") (part "FERRITE-BEAD-0603"))
    )
    (comp (ref "FB4")
      (value "120R/1.3A")
      (footprint "eagle-import:F0402")
      (libsource (lib "eagle-import") (part "FERRITE-BEAD-0402"))
    )
    (comp (ref "FB5")
      (value "120R/1.3A")
      (footprint "eagle-import:F0402")
      (libsource (lib "eagle-import") (part "FERRITE-BEAD-0402"))
    )
    (comp (ref "FB6")
      (value "BLM21PG331SN1D")
      (footprint "eagle-import:F0805")
      (libsource (lib "eagle-import") (part "FERRITE-BEAD-0805"))
    )
    (comp (ref "FB7")
      (value "120R/2A")
      (footprint "eagle-import:F0603")
      (libsource (lib "eagle-import") (part "FERRITE-BEAD-0603"))
    )
    (comp (ref "FB8")
      (value "120R/2A")
      (footprint "eagle-import:F0603")
      (libsource (lib "eagle-import") (part "FERRITE-BEAD-0603"))
    )
    (comp (ref "FB9")
      (value "120R/2A")
      (footprint "eagle-import:F0603")
      (libsource (lib "eagle-import") (part "FERRITE-BEAD-0603"))
    )
    (comp (ref "FPGA_RST")
      (value "BUTTON")
      (footprint "eagle-import:SW4P-SMD-4.5X3.2X2.5MM")
      (libsource (lib "eagle-import") (part "BUTTON-4P-4.5X3.2"))
    )
    (comp (ref "FR1")
      (value "SEEEDSTUDIO-OPEN-SCH-FRAME-BIG")
      (footprint "eagle-import:SEEEDSTUDIO-PCB-FRAME")
      (libsource (lib "eagle-import") (part "SEEEDSTUDIO-OPEN-SCH-FRAME-BIG"))
    )
    (comp (ref "FR2")
      (value "SEEEDSTUDIO-OPEN-SCH-FRAME-BIG")
      (footprint "eagle-import:SEEEDSTUDIO-PCB-FRAME")
      (libsource (lib "eagle-import") (part "SEEEDSTUDIO-OPEN-SCH-FRAME-BIG"))
    )
    (comp (ref "FR3")
      (value "SEEEDSTUDIO-OPEN-SCH-FRAME-BIG")
      (footprint "eagle-import:SEEEDSTUDIO-PCB-FRAME")
      (libsource (lib "eagle-import") (part "SEEEDSTUDIO-OPEN-SCH-FRAME-BIG"))
    )
    (comp (ref "FR4")
      (value "SEEEDSTUDIO-OPEN-SCH-FRAME-BIG")
      (footprint "eagle-import:SEEEDSTUDIO-PCB-FRAME")
      (libsource (lib "eagle-import") (part "SEEEDSTUDIO-OPEN-SCH-FRAME-BIG"))
    )
    (comp (ref "FR5")
      (value "SEEEDSTUDIO-OPEN-SCH-FRAME-BIG")
      (footprint "eagle-import:SEEEDSTUDIO-PCB-FRAME")
      (libsource (lib "eagle-import") (part "SEEEDSTUDIO-OPEN-SCH-FRAME-BIG"))
    )
    (comp (ref "FR6")
      (value "SEEEDSTUDIO-OPEN-SCH-FRAME-BIG")
      (footprint "eagle-import:SEEEDSTUDIO-PCB-FRAME")
      (libsource (lib "eagle-import") (part "SEEEDSTUDIO-OPEN-SCH-FRAME-BIG"))
    )
    (comp (ref "J1")
      (value "4PIN-2.54")
      (footprint "eagle-import:H4-2.54")
      (libsource (lib "eagle-import") (part "HEADER-4P-65/35MIL"))
    )
    (comp (ref "J2")
      (value "320110033")
      (footprint "eagle-import:HW4-2.0")
      (libsource (lib "eagle-import") (part "GROVE-CONNECTOR-DIP-320110033"))
    )
    (comp (ref "J3")
      (value "SCHA5B0200")
      (footprint "eagle-import:MICRO-SD9+7P-SMD-15X14.5X1.5")
      (libsource (lib "eagle-import") (part "MICRO-SD-CARD-HOLDER-9P-SCHA5B0200-SCHA5B0200"))
    )
    (comp (ref "J4")
      (value "320110033")
      (footprint "eagle-import:HW4-2.0")
      (libsource (lib "eagle-import") (part "GROVE-CONNECTOR-DIP-320110033"))
    )
    (comp (ref "J5")
      (value "2*3pin")
      (footprint "eagle-import:H2X3-2.54")
      (libsource (lib "eagle-import") (part "HEADER-2X3P-2.54"))
    )
    (comp (ref "J6")
      (value "FPC 15pins")
      (footprint "eagle-import:H2X15-SMD-1MM")
      (libsource (lib "eagle-import") (part "HEADER-2X15P-SMD"))
    )
    (comp (ref "J8")
      (value "6PIN-2.54")
      (footprint "eagle-import:H6-2.54-C65D35MIL")
      (libsource (lib "eagle-import") (part "HEADER-6P-65/35MIL"))
    )
    (comp (ref "J9")
      (value "Mini HDMI")
      (footprint "eagle-import:HDMI-19+4P-0.4-11.2X7.5MM")
      (libsource (lib "eagle-import") (part "MINI-HDMI-19PIN-SMT-C-TYPE-ST-HD-002B"))
    )
    (comp (ref "J10")
      (value "DNP")
      (footprint "eagle-import:H10-2.54")
      (libsource (lib "eagle-import") (part "HEADER-10P-2.54"))
    )
    (comp (ref "J15")
      (value "HEADER-3P-2.54")
      (footprint "eagle-import:H3-2.54")
      (libsource (lib "eagle-import") (part "HEADER-3P-2.54"))
    )
    (comp (ref "L1")
      (value "DNP")
      (footprint "eagle-import:L0402")
      (libsource (lib "eagle-import") (part "INDUCTOR'0402'"))
    )
    (comp (ref "L2")
      (value "DNP")
      (footprint "eagle-import:L0402")
      (libsource (lib "eagle-import") (part "INDUCTOR'0402'"))
    )
    (comp (ref "L3")
      (value "DNP")
      (footprint "eagle-import:INT4-0.8-2X1.2MM")
      (libsource (lib "eagle-import") (part "INDUCTOR-COMMON-MODE-WCM-HDMI"))
    )
    (comp (ref "L4")
      (value "DNP")
      (footprint "eagle-import:INT4-0.8-2X1.2MM")
      (libsource (lib "eagle-import") (part "INDUCTOR-COMMON-MODE-WCM-HDMI"))
    )
    (comp (ref "L5")
      (value "DNP")
      (footprint "eagle-import:INT4-0.8-2X1.2MM")
      (libsource (lib "eagle-import") (part "INDUCTOR-COMMON-MODE-WCM-HDMI"))
    )
    (comp (ref "L6")
      (value "VLC5045T-2R2N")
      (footprint "eagle-import:INT2-SMD-4.8X4.8X3MM")
      (libsource (lib "eagle-import") (part "INDUCTOR-4.8X4.8"))
    )
    (comp (ref "L7")
      (value "DNP")
      (footprint "eagle-import:INT4-0.8-2X1.2MM")
      (libsource (lib "eagle-import") (part "INDUCTOR-COMMON-MODE-WCM-HDMI"))
    )
    (comp (ref "L15")
      (value "SRF2012-900YA")
      (footprint "eagle-import:INT4-0.85-2X1.25X1.2MM")
      (libsource (lib "eagle-import") (part "INDUCTOR-COMMON-MODE-SRF2012-900YA"))
    )
    (comp (ref "LED1")
      (value "SK6805")
      (footprint "eagle-import:LED-4P-SMD-2.7X2.4MM")
      (libsource (lib "eagle-import") (part "LED-SK6805-2427"))
    )
    (comp (ref "LED2")
      (value "SK6805")
      (footprint "eagle-import:LED-4P-SMD-2.7X2.4MM")
      (libsource (lib "eagle-import") (part "LED-SK6805-2427"))
    )
    (comp (ref "Q1")
      (value "CJ2102")
      (footprint "eagle-import:SOT-323")
      (libsource (lib "eagle-import") (part "MOSFET-N'SI1304BDL'"))
    )
    (comp (ref "Q2")
      (value "CJ3407")
      (footprint "eagle-import:SOT-23")
      (libsource (lib "eagle-import") (part "MOSFET-P'SI2323CDS/SI2305DS{lt}BR{gt}'"))
    )
    (comp (ref "Q3")
      (value "CJ3407")
      (footprint "eagle-import:SOT-23")
      (libsource (lib "eagle-import") (part "MOSFET-P'SI2323CDS/SI2305DS{lt}BR{gt}'"))
    )
    (comp (ref "Q4")
      (value "MMBT3904")
      (footprint "eagle-import:SOT-23")
      (libsource (lib "eagle-import") (part "TRANSISTOR-NPN-SOT23"))
    )
    (comp (ref "Q5")
      (value "MMBT3904")
      (footprint "eagle-import:SOT-23")
      (libsource (lib "eagle-import") (part "TRANSISTOR-NPN-SOT23"))
    )
    (comp (ref "R1")
      (value "20k")
      (footprint "eagle-import:R0402")
      (libsource (lib "eagle-import") (part "RES-0402"))
    )
    (comp (ref "R2")
      (value "DNP")
      (footprint "eagle-import:R0402")
      (libsource (lib "eagle-import") (part "RES-0402"))
    )
    (comp (ref "R3")
      (value "0R")
      (footprint "eagle-import:R0402")
      (libsource (lib "eagle-import") (part "RES-0402"))
    )
    (comp (ref "R4")
      (value "10k")
      (footprint "eagle-import:R0402")
      (libsource (lib "eagle-import") (part "RES-0402"))
    )
    (comp (ref "R5")
      (value "10k")
      (footprint "eagle-import:R0402")
      (libsource (lib "eagle-import") (part "RES-0402"))
    )
    (comp (ref "R6")
      (value "0R")
      (footprint "eagle-import:R0402")
      (libsource (lib "eagle-import") (part "RES-0402"))
    )
    (comp (ref "R7")
      (value "0R")
      (footprint "eagle-import:R0402")
      (libsource (lib "eagle-import") (part "RES-0402"))
    )
    (comp (ref "R8")
      (value "4.7k")
      (footprint "eagle-import:R0402")
      (libsource (lib "eagle-import") (part "RES-0402"))
    )
    (comp (ref "R9")
      (value "10k")
      (footprint "eagle-import:R0402")
      (libsource (lib "eagle-import") (part "RES-0402"))
    )
    (comp (ref "R10")
      (value "33R")
      (footprint "eagle-import:R0402")
      (libsource (lib "eagle-import") (part "RES-0402"))
    )
    (comp (ref "R11")
      (value "0R")
      (footprint "eagle-import:R0603")
      (libsource (lib "eagle-import") (part "RES-0603"))
    )
    (comp (ref "R12")
      (value "33R")
      (footprint "eagle-import:R0402")
      (libsource (lib "eagle-import") (part "RES-0402"))
    )
    (comp (ref "R13")
      (value "10k")
      (footprint "eagle-import:R0402")
      (libsource (lib "eagle-import") (part "RES-0402"))
    )
    (comp (ref "R14")
      (value "10k")
      (footprint "eagle-import:R0402")
      (libsource (lib "eagle-import") (part "RES-0402"))
    )
    (comp (ref "R15")
      (value "5.1k")
      (footprint "eagle-import:R0402")
      (libsource (lib "eagle-import") (part "RES-0402"))
    )
    (comp (ref "R16")
      (value "0R")
      (footprint "eagle-import:R0402")
      (libsource (lib "eagle-import") (part "RES-0402"))
    )
    (comp (ref "R17")
      (value "DNP")
      (footprint "eagle-import:R0402")
      (libsource (lib "eagle-import") (part "RES-0402"))
    )
    (comp (ref "R18")
      (value "10k")
      (footprint "eagle-import:R0402")
      (libsource (lib "eagle-import") (part "RES-0402"))
    )
    (comp (ref "R19")
      (value "10k")
      (footprint "eagle-import:R0402")
      (libsource (lib "eagle-import") (part "RES-0402"))
    )
    (comp (ref "R20")
      (value "DNP")
      (footprint "eagle-import:R0402")
      (libsource (lib "eagle-import") (part "RES-0402"))
    )
    (comp (ref "R21")
      (value "4.7k")
      (footprint "eagle-import:R0402")
      (libsource (lib "eagle-import") (part "RES-0402"))
    )
    (comp (ref "R22")
      (value "5.1k")
      (footprint "eagle-import:R0402")
      (libsource (lib "eagle-import") (part "RES-0402"))
    )
    (comp (ref "R23")
      (value "0R")
      (footprint "eagle-import:R0402")
      (libsource (lib "eagle-import") (part "RES-0402"))
    )
    (comp (ref "R24")
      (value "0R")
      (footprint "eagle-import:R0402")
      (libsource (lib "eagle-import") (part "RES-0402"))
    )
    (comp (ref "R25")
      (value "0R")
      (footprint "eagle-import:R0402")
      (libsource (lib "eagle-import") (part "RES-0402"))
    )
    (comp (ref "R26")
      (value "0R")
      (footprint "eagle-import:R0402")
      (libsource (lib "eagle-import") (part "RES-0402"))
    )
    (comp (ref "R27")
      (value "0R")
      (footprint "eagle-import:R0402")
      (libsource (lib "eagle-import") (part "RES-0402"))
    )
    (comp (ref "R28")
      (value "100R")
      (footprint "eagle-import:R0402")
      (libsource (lib "eagle-import") (part "RES-0402"))
    )
    (comp (ref "R29")
      (value "100R")
      (footprint "eagle-import:R0402")
      (libsource (lib "eagle-import") (part "RES-0402"))
    )
    (comp (ref "R30")
      (value "2k")
      (footprint "eagle-import:R0402")
      (libsource (lib "eagle-import") (part "RES-0402"))
    )
    (comp (ref "R31")
      (value "2k")
      (footprint "eagle-import:R0402")
      (libsource (lib "eagle-import") (part "RES-0402"))
    )
    (comp (ref "R32")
      (value "10k")
      (footprint "eagle-import:R0402")
      (libsource (lib "eagle-import") (part "RES-0402"))
    )
    (comp (ref "R33")
      (value "20k")
      (footprint "eagle-import:R0402")
      (libsource (lib "eagle-import") (part "RES-0402"))
    )
    (comp (ref "R34")
      (value "10k")
      (footprint "eagle-import:R0402")
      (libsource (lib "eagle-import") (part "RES-0402"))
    )
    (comp (ref "R35")
      (value "20k")
      (footprint "eagle-import:R0402")
      (libsource (lib "eagle-import") (part "RES-0402"))
    )
    (comp (ref "R36")
      (value "10k")
      (footprint "eagle-import:R0402")
      (libsource (lib "eagle-import") (part "RES-0402"))
    )
    (comp (ref "R37")
      (value "0R")
      (footprint "eagle-import:R0402")
      (libsource (lib "eagle-import") (part "RES-0402"))
    )
    (comp (ref "R38")
      (value "DNP")
      (footprint "eagle-import:R0402")
      (libsource (lib "eagle-import") (part "RES-0402"))
    )
    (comp (ref "R39")
      (value "200k")
      (footprint "eagle-import:R0402")
      (libsource (lib "eagle-import") (part "RES-0402"))
    )
    (comp (ref "R40")
      (value "4.7k")
      (footprint "eagle-import:R0402")
      (libsource (lib "eagle-import") (part "RES-0402"))
    )
    (comp (ref "R41")
      (value "4.7k")
      (footprint "eagle-import:R0402")
      (libsource (lib "eagle-import") (part "RES-0402"))
    )
    (comp (ref "R42")
      (value "4.7k")
      (footprint "eagle-import:R0402")
      (libsource (lib "eagle-import") (part "RES-0402"))
    )
    (comp (ref "R43")
      (value "4.7k")
      (footprint "eagle-import:R0402")
      (libsource (lib "eagle-import") (part "RES-0402"))
    )
    (comp (ref "R44")
      (value "2k")
      (footprint "eagle-import:R0402")
      (libsource (lib "eagle-import") (part "RES-0402"))
    )
    (comp (ref "R45")
      (value "2k")
      (footprint "eagle-import:R0402")
      (libsource (lib "eagle-import") (part "RES-0402"))
    )
    (comp (ref "R46")
      (value "2k")
      (footprint "eagle-import:R0402")
      (libsource (lib "eagle-import") (part "RES-0402"))
    )
    (comp (ref "R47")
      (value "0R")
      (footprint "eagle-import:R0402")
      (libsource (lib "eagle-import") (part "RES-0402"))
    )
    (comp (ref "R48")
      (value "10k")
      (footprint "eagle-import:R0402")
      (libsource (lib "eagle-import") (part "RES-0402"))
    )
    (comp (ref "R49")
      (value "1k")
      (footprint "eagle-import:R0402")
      (libsource (lib "eagle-import") (part "RES-0402"))
    )
    (comp (ref "R50")
      (value "1k")
      (footprint "eagle-import:R0402")
      (libsource (lib "eagle-import") (part "RES-0402"))
    )
    (comp (ref "R51")
      (value "1k")
      (footprint "eagle-import:R0402")
      (libsource (lib "eagle-import") (part "RES-0402"))
    )
    (comp (ref "R52")
      (value "1k")
      (footprint "eagle-import:R0402")
      (libsource (lib "eagle-import") (part "RES-0402"))
    )
    (comp (ref "R53")
      (value "4.7k")
      (footprint "eagle-import:R0402")
      (libsource (lib "eagle-import") (part "RES-0402"))
    )
    (comp (ref "R54")
      (value "4.7k")
      (footprint "eagle-import:R0402")
      (libsource (lib "eagle-import") (part "RES-0402"))
    )
    (comp (ref "R55")
      (value "4.7k")
      (footprint "eagle-import:R0402")
      (libsource (lib "eagle-import") (part "RES-0402"))
    )
    (comp (ref "R56")
      (value "1k")
      (footprint "eagle-import:R0402")
      (libsource (lib "eagle-import") (part "RES-0402"))
    )
    (comp (ref "R57")
      (value "1k")
      (footprint "eagle-import:R0402")
      (libsource (lib "eagle-import") (part "RES-0402"))
    )
    (comp (ref "R58")
      (value "0R")
      (footprint "eagle-import:R0402")
      (libsource (lib "eagle-import") (part "RES-0402"))
    )
    (comp (ref "R59")
      (value "100k")
      (footprint "eagle-import:R0402")
      (libsource (lib "eagle-import") (part "RES-0402"))
    )
    (comp (ref "R60")
      (value "100k")
      (footprint "eagle-import:R0402")
      (libsource (lib "eagle-import") (part "RES-0402"))
    )
    (comp (ref "R61")
      (value "100k")
      (footprint "eagle-import:R0603")
      (libsource (lib "eagle-import") (part "RES-0603"))
    )
    (comp (ref "R62")
      (value "0R")
      (footprint "eagle-import:R0603")
      (libsource (lib "eagle-import") (part "RES-0603"))
    )
    (comp (ref "R63")
      (value "100k")
      (footprint "eagle-import:R0402")
      (libsource (lib "eagle-import") (part "RES-0402"))
    )
    (comp (ref "R64")
      (value "100k")
      (footprint "eagle-import:R0402")
      (libsource (lib "eagle-import") (part "RES-0402"))
    )
    (comp (ref "R65")
      (value "1k")
      (footprint "eagle-import:R0402")
      (libsource (lib "eagle-import") (part "RES-0402"))
    )
    (comp (ref "R66")
      (value "0R")
      (footprint "eagle-import:R0402")
      (libsource (lib "eagle-import") (part "RES-0402"))
    )
    (comp (ref "R67")
      (value "10k")
      (footprint "eagle-import:R0402")
      (libsource (lib "eagle-import") (part "RES-0402"))
    )
    (comp (ref "R68")
      (value "100R")
      (footprint "eagle-import:R0402")
      (libsource (lib "eagle-import") (part "RES-0402"))
    )
    (comp (ref "R69")
      (value "100R")
      (footprint "eagle-import:R0402")
      (libsource (lib "eagle-import") (part "RES-0402"))
    )
    (comp (ref "R70")
      (value "1k")
      (footprint "eagle-import:R0402")
      (libsource (lib "eagle-import") (part "RES-0402"))
    )
    (comp (ref "R71")
      (value "10k")
      (footprint "eagle-import:R0402")
      (libsource (lib "eagle-import") (part "RES-0402"))
    )
    (comp (ref "R72")
      (value "49.9R")
      (footprint "eagle-import:R0402")
      (libsource (lib "eagle-import") (part "RES-0402"))
    )
    (comp (ref "R73")
      (value "49.9R")
      (footprint "eagle-import:R0402")
      (libsource (lib "eagle-import") (part "RES-0402"))
    )
    (comp (ref "R74")
      (value "49.9R")
      (footprint "eagle-import:R0402")
      (libsource (lib "eagle-import") (part "RES-0402"))
    )
    (comp (ref "R75")
      (value "49.9R")
      (footprint "eagle-import:R0402")
      (libsource (lib "eagle-import") (part "RES-0402"))
    )
    (comp (ref "R76")
      (value "49.9R")
      (footprint "eagle-import:R0402")
      (libsource (lib "eagle-import") (part "RES-0402"))
    )
    (comp (ref "R77")
      (value "49.9R")
      (footprint "eagle-import:R0402")
      (libsource (lib "eagle-import") (part "RES-0402"))
    )
    (comp (ref "R78")
      (value "49.9R")
      (footprint "eagle-import:R0402")
      (libsource (lib "eagle-import") (part "RES-0402"))
    )
    (comp (ref "R79")
      (value "49.9R")
      (footprint "eagle-import:R0402")
      (libsource (lib "eagle-import") (part "RES-0402"))
    )
    (comp (ref "R80")
      (value "100nF")
      (footprint "eagle-import:R0603")
      (libsource (lib "eagle-import") (part "RES-0603"))
    )
    (comp (ref "R81")
      (value "100nF")
      (footprint "eagle-import:R0603")
      (libsource (lib "eagle-import") (part "RES-0603"))
    )
    (comp (ref "R82")
      (value "1k")
      (footprint "eagle-import:R0402")
      (libsource (lib "eagle-import") (part "RES-0402"))
    )
    (comp (ref "R83")
      (value "1k")
      (footprint "eagle-import:R0402")
      (libsource (lib "eagle-import") (part "RES-0402"))
    )
    (comp (ref "R84")
      (value "33R")
      (footprint "eagle-import:R0402")
      (libsource (lib "eagle-import") (part "RES-0402"))
    )
    (comp (ref "R85")
      (value "10k")
      (footprint "eagle-import:R0402")
      (libsource (lib "eagle-import") (part "RES-0402"))
    )
    (comp (ref "R86")
      (value "100nF")
      (footprint "eagle-import:R0603")
      (libsource (lib "eagle-import") (part "RES-0603"))
    )
    (comp (ref "R87")
      (value "100nF")
      (footprint "eagle-import:R0603")
      (libsource (lib "eagle-import") (part "RES-0603"))
    )
    (comp (ref "R88")
      (value "100nF")
      (footprint "eagle-import:R0603")
      (libsource (lib "eagle-import") (part "RES-0603"))
    )
    (comp (ref "R89")
      (value "100nF")
      (footprint "eagle-import:R0603")
      (libsource (lib "eagle-import") (part "RES-0603"))
    )
    (comp (ref "R90")
      (value "100nF")
      (footprint "eagle-import:R0603")
      (libsource (lib "eagle-import") (part "RES-0603"))
    )
    (comp (ref "R91")
      (value "100nF")
      (footprint "eagle-import:R0603")
      (libsource (lib "eagle-import") (part "RES-0603"))
    )
    (comp (ref "R92")
      (value "1k")
      (footprint "eagle-import:R0402")
      (libsource (lib "eagle-import") (part "RES-0402"))
    )
    (comp (ref "R93")
      (value "0R")
      (footprint "eagle-import:R0402")
      (libsource (lib "eagle-import") (part "RES-0402"))
    )
    (comp (ref "R94")
      (value "DNP")
      (footprint "eagle-import:R0402")
      (libsource (lib "eagle-import") (part "RES-0402"))
    )
    (comp (ref "R95")
      (value "DNP")
      (footprint "eagle-import:R0402")
      (libsource (lib "eagle-import") (part "RES-0402"))
    )
    (comp (ref "R96")
      (value "10k")
      (footprint "eagle-import:R0402")
      (libsource (lib "eagle-import") (part "RES-0402"))
    )
    (comp (ref "R97")
      (value "DNP")
      (footprint "eagle-import:R0402")
      (libsource (lib "eagle-import") (part "RES-0402"))
    )
    (comp (ref "R98")
      (value "150R_1%")
      (footprint "eagle-import:R0402")
      (libsource (lib "eagle-import") (part "RES-0402"))
    )
    (comp (ref "R99")
      (value "150R_1%")
      (footprint "eagle-import:R0402")
      (libsource (lib "eagle-import") (part "RES-0402"))
    )
    (comp (ref "R100")
      (value "150R_1%")
      (footprint "eagle-import:R0402")
      (libsource (lib "eagle-import") (part "RES-0402"))
    )
    (comp (ref "R101")
      (value "4.7k")
      (footprint "eagle-import:R0402")
      (libsource (lib "eagle-import") (part "RES-0402"))
    )
    (comp (ref "R102")
      (value "4.7k")
      (footprint "eagle-import:R0402")
      (libsource (lib "eagle-import") (part "RES-0402"))
    )
    (comp (ref "R103")
      (value "4.7k")
      (footprint "eagle-import:R0402")
      (libsource (lib "eagle-import") (part "RES-0402"))
    )
    (comp (ref "R104")
      (value "DNP")
      (footprint "eagle-import:R0402")
      (libsource (lib "eagle-import") (part "RES-0402"))
    )
    (comp (ref "R105")
      (value "DNP")
      (footprint "eagle-import:R0402")
      (libsource (lib "eagle-import") (part "RES-0402"))
    )
    (comp (ref "R106")
      (value "DNP")
      (footprint "eagle-import:R0402")
      (libsource (lib "eagle-import") (part "RES-0402"))
    )
    (comp (ref "R107")
      (value "33R")
      (footprint "eagle-import:R0402")
      (libsource (lib "eagle-import") (part "RES-0402"))
    )
    (comp (ref "R108")
      (value "33R")
      (footprint "eagle-import:R0402")
      (libsource (lib "eagle-import") (part "RES-0402"))
    )
    (comp (ref "R109")
      (value "33R")
      (footprint "eagle-import:R0402")
      (libsource (lib "eagle-import") (part "RES-0402"))
    )
    (comp (ref "R110")
      (value "33R")
      (footprint "eagle-import:R0402")
      (libsource (lib "eagle-import") (part "RES-0402"))
    )
    (comp (ref "R111")
      (value "33R")
      (footprint "eagle-import:R0402")
      (libsource (lib "eagle-import") (part "RES-0402"))
    )
    (comp (ref "R112")
      (value "33R")
      (footprint "eagle-import:R0402")
      (libsource (lib "eagle-import") (part "RES-0402"))
    )
    (comp (ref "R113")
      (value "33R")
      (footprint "eagle-import:R0402")
      (libsource (lib "eagle-import") (part "RES-0402"))
    )
    (comp (ref "R114")
      (value "10k")
      (footprint "eagle-import:R0402")
      (libsource (lib "eagle-import") (part "RES-0402"))
    )
    (comp (ref "R115")
      (value "33R")
      (footprint "eagle-import:R0402")
      (libsource (lib "eagle-import") (part "RES-0402"))
    )
    (comp (ref "R116")
      (value "DNP")
      (footprint "eagle-import:R0402")
      (libsource (lib "eagle-import") (part "RES-0402"))
    )
    (comp (ref "R117")
      (value "10k")
      (footprint "eagle-import:R0402")
      (libsource (lib "eagle-import") (part "RES-0402"))
    )
    (comp (ref "R118")
      (value "20k")
      (footprint "eagle-import:R0402")
      (libsource (lib "eagle-import") (part "RES-0402"))
    )
    (comp (ref "R119")
      (value "10k")
      (footprint "eagle-import:R0402")
      (libsource (lib "eagle-import") (part "RES-0402"))
    )
    (comp (ref "R120")
      (value "20k")
      (footprint "eagle-import:R0402")
      (libsource (lib "eagle-import") (part "RES-0402"))
    )
    (comp (ref "R121")
      (value "10k")
      (footprint "eagle-import:R0402")
      (libsource (lib "eagle-import") (part "RES-0402"))
    )
    (comp (ref "R122")
      (value "20k")
      (footprint "eagle-import:R0402")
      (libsource (lib "eagle-import") (part "RES-0402"))
    )
    (comp (ref "R123")
      (value "10k")
      (footprint "eagle-import:R0402")
      (libsource (lib "eagle-import") (part "RES-0402"))
    )
    (comp (ref "R124")
      (value "20k")
      (footprint "eagle-import:R0402")
      (libsource (lib "eagle-import") (part "RES-0402"))
    )
    (comp (ref "R125")
      (value "DNP")
      (footprint "eagle-import:R0402")
      (libsource (lib "eagle-import") (part "RES-0402"))
    )
    (comp (ref "R126")
      (value "10k")
      (footprint "eagle-import:R0402")
      (libsource (lib "eagle-import") (part "RES-0402"))
    )
    (comp (ref "R127")
      (value "DNP")
      (footprint "eagle-import:R0402")
      (libsource (lib "eagle-import") (part "RES-0402"))
    )
    (comp (ref "R128")
      (value "100R_1%")
      (footprint "eagle-import:R0402")
      (libsource (lib "eagle-import") (part "RES-0402"))
    )
    (comp (ref "R129")
      (value "100R_1%")
      (footprint "eagle-import:R0402")
      (libsource (lib "eagle-import") (part "RES-0402"))
    )
    (comp (ref "R130")
      (value "100k")
      (footprint "eagle-import:R0402")
      (libsource (lib "eagle-import") (part "RES-0402"))
    )
    (comp (ref "R133")
      (value "10k")
      (footprint "eagle-import:R0402")
      (libsource (lib "eagle-import") (part "RES-0402"))
    )
    (comp (ref "R134")
      (value "536k_1%")
      (footprint "eagle-import:R0603")
      (libsource (lib "eagle-import") (part "RES-0603"))
    )
    (comp (ref "R135")
      (value "100K_1%")
      (footprint "eagle-import:R0603")
      (libsource (lib "eagle-import") (part "RES-0603"))
    )
    (comp (ref "R140")
      (value "33R")
      (footprint "eagle-import:R0402")
      (libsource (lib "eagle-import") (part "RES-0402"))
    )
    (comp (ref "R141")
      (value "33R")
      (footprint "eagle-import:R0402")
      (libsource (lib "eagle-import") (part "RES-0402"))
    )
    (comp (ref "R142")
      (value "33R")
      (footprint "eagle-import:R0402")
      (libsource (lib "eagle-import") (part "RES-0402"))
    )
    (comp (ref "R143")
      (value "33R")
      (footprint "eagle-import:R0402")
      (libsource (lib "eagle-import") (part "RES-0402"))
    )
    (comp (ref "R144")
      (value "4.7k")
      (footprint "eagle-import:R0402")
      (libsource (lib "eagle-import") (part "RES-0402"))
    )
    (comp (ref "R145")
      (value "10k")
      (footprint "eagle-import:R0402")
      (libsource (lib "eagle-import") (part "RES-0402"))
    )
    (comp (ref "R146")
      (value "DNP")
      (footprint "eagle-import:R0402")
      (libsource (lib "eagle-import") (part "RES-0402"))
    )
    (comp (ref "R147")
      (value "DNP")
      (footprint "eagle-import:R0402")
      (libsource (lib "eagle-import") (part "RES-0402"))
    )
    (comp (ref "R148")
      (value "DNP")
      (footprint "eagle-import:R1206")
      (libsource (lib "eagle-import") (part "RES-1206"))
    )
    (comp (ref "R149")
      (value "DNP")
      (footprint "eagle-import:R0402")
      (libsource (lib "eagle-import") (part "RES-0402"))
    )
    (comp (ref "R150")
      (value "DNP")
      (footprint "eagle-import:R0402")
      (libsource (lib "eagle-import") (part "RES-0402"))
    )
    (comp (ref "R151")
      (value "4.7k")
      (footprint "eagle-import:R0402")
      (libsource (lib "eagle-import") (part "RES-0402"))
    )
    (comp (ref "R152")
      (value "1k")
      (footprint "eagle-import:R0402")
      (libsource (lib "eagle-import") (part "RES-0402"))
    )
    (comp (ref "R153")
      (value "2k")
      (footprint "eagle-import:R0402")
      (libsource (lib "eagle-import") (part "RES-0402"))
    )
    (comp (ref "R154")
      (value "1k")
      (footprint "eagle-import:R0402")
      (libsource (lib "eagle-import") (part "RES-0402"))
    )
    (comp (ref "R155")
      (value "2k")
      (footprint "eagle-import:R0402")
      (libsource (lib "eagle-import") (part "RES-0402"))
    )
    (comp (ref "R156")
      (value "1k")
      (footprint "eagle-import:R0402")
      (libsource (lib "eagle-import") (part "RES-0402"))
    )
    (comp (ref "R157")
      (value "2k")
      (footprint "eagle-import:R0402")
      (libsource (lib "eagle-import") (part "RES-0402"))
    )
    (comp (ref "R158")
      (value "1k")
      (footprint "eagle-import:R0402")
      (libsource (lib "eagle-import") (part "RES-0402"))
    )
    (comp (ref "R159")
      (value "2k")
      (footprint "eagle-import:R0402")
      (libsource (lib "eagle-import") (part "RES-0402"))
    )
    (comp (ref "R160")
      (value "1k")
      (footprint "eagle-import:R0402")
      (libsource (lib "eagle-import") (part "RES-0402"))
    )
    (comp (ref "R161")
      (value "2k")
      (footprint "eagle-import:R0402")
      (libsource (lib "eagle-import") (part "RES-0402"))
    )
    (comp (ref "R162")
      (value "1k")
      (footprint "eagle-import:R0402")
      (libsource (lib "eagle-import") (part "RES-0402"))
    )
    (comp (ref "R163")
      (value "2k")
      (footprint "eagle-import:R0402")
      (libsource (lib "eagle-import") (part "RES-0402"))
    )
    (comp (ref "R164")
      (value "10k")
      (footprint "eagle-import:R0402")
      (libsource (lib "eagle-import") (part "RES-0402"))
    )
    (comp (ref "R165")
      (value "20k")
      (footprint "eagle-import:R0402")
      (libsource (lib "eagle-import") (part "RES-0402"))
    )
    (comp (ref "R166")
      (value "1k")
      (footprint "eagle-import:R0402")
      (libsource (lib "eagle-import") (part "RES-0402"))
    )
    (comp (ref "R167")
      (value "2k")
      (footprint "eagle-import:R0402")
      (libsource (lib "eagle-import") (part "RES-0402"))
    )
    (comp (ref "R171")
      (value "4.7k")
      (footprint "eagle-import:R0402")
      (libsource (lib "eagle-import") (part "RES-0402"))
    )
    (comp (ref "R172")
      (value "1k")
      (footprint "eagle-import:R0402")
      (libsource (lib "eagle-import") (part "RES-0402"))
    )
    (comp (ref "R173")
      (value "2k")
      (footprint "eagle-import:R0402")
      (libsource (lib "eagle-import") (part "RES-0402"))
    )
    (comp (ref "R174")
      (value "1k")
      (footprint "eagle-import:R0402")
      (libsource (lib "eagle-import") (part "RES-0402"))
    )
    (comp (ref "R175")
      (value "2k")
      (footprint "eagle-import:R0402")
      (libsource (lib "eagle-import") (part "RES-0402"))
    )
    (comp (ref "R176")
      (value "1k")
      (footprint "eagle-import:R0402")
      (libsource (lib "eagle-import") (part "RES-0402"))
    )
    (comp (ref "R177")
      (value "2k")
      (footprint "eagle-import:R0402")
      (libsource (lib "eagle-import") (part "RES-0402"))
    )
    (comp (ref "R178")
      (value "1k")
      (footprint "eagle-import:R0402")
      (libsource (lib "eagle-import") (part "RES-0402"))
    )
    (comp (ref "R179")
      (value "2k")
      (footprint "eagle-import:R0402")
      (libsource (lib "eagle-import") (part "RES-0402"))
    )
    (comp (ref "R180")
      (value "4.7k")
      (footprint "eagle-import:R0402")
      (libsource (lib "eagle-import") (part "RES-0402"))
    )
    (comp (ref "R181")
      (value "DNP")
      (footprint "eagle-import:R0402")
      (libsource (lib "eagle-import") (part "RES-0402"))
    )
    (comp (ref "R182")
      (value "DNP")
      (footprint "eagle-import:R0402")
      (libsource (lib "eagle-import") (part "RES-0402"))
    )
    (comp (ref "R183")
      (value "10k")
      (footprint "eagle-import:R0402")
      (libsource (lib "eagle-import") (part "RES-0402"))
    )
    (comp (ref "R184")
      (value "DNP")
      (footprint "eagle-import:R0402")
      (libsource (lib "eagle-import") (part "RES-0402"))
    )
    (comp (ref "R185")
      (value "10k")
      (footprint "eagle-import:R0402")
      (libsource (lib "eagle-import") (part "RES-0402"))
    )
    (comp (ref "R186")
      (value "DNP")
      (footprint "eagle-import:R0402")
      (libsource (lib "eagle-import") (part "RES-0402"))
    )
    (comp (ref "R187")
      (value "DNP")
      (footprint "eagle-import:R0402")
      (libsource (lib "eagle-import") (part "RES-0402"))
    )
    (comp (ref "RST")
      (value "SKRPADE010")
      (footprint "eagle-import:SW4P-SMD-4.5X3.2X2.5MM")
      (libsource (lib "eagle-import") (part "BUTTON-4P-4.5X3.2"))
    )
    (comp (ref "SW1")
      (value "311010004")
      (footprint "eagle-import:SW6-2.54-9.0X3.5X3.2+2.0MM")
      (libsource (lib "eagle-import") (part "SWITCH-2CH-6P-311010004"))
    )
    (comp (ref "SW2")
      (value "DG2788A")
      (footprint "eagle-import:MINI-QFN16-0.4-2.6X1.8X0.55MM")
      (libsource (lib "eagle-import") (part "SWITCH-DG2788A"))
    )
    (comp (ref "SW4")
      (value "SWITCH-5BIT-DSHP05TSGER")
      (footprint "eagle-import:10P-SMD-7.95X5.4X2.3MM")
      (libsource (lib "eagle-import") (part "SWITCH-5BIT-DSHP05TSGER"))
    )
    (comp (ref "TP1")
      (value "TEST-POINT-35")
      (footprint "eagle-import:TP_3535")
      (libsource (lib "eagle-import") (part "TEST-POINT-35"))
    )
    (comp (ref "TP2")
      (value "TEST-POINT-35")
      (footprint "eagle-import:TP_3535")
      (libsource (lib "eagle-import") (part "TEST-POINT-35"))
    )
    (comp (ref "TP5")
      (value "TEST-POINT'4545'")
      (footprint "eagle-import:TP-D45MIL")
      (fields (field (name "PARTNO") "DNP"))
      (libsource (lib "eagle-import") (part "TEST-POINT'4545'"))
    )
    (comp (ref "U1")
      (value "XC7S15-1FTGB196C")
      (footprint "eagle-import:FTGB196-1.0-15X15X1.46MM")
      (libsource (lib "eagle-import") (part "XC7S15"))
    )
    (comp (ref "U2")
      (value "ESP32-D0WDQ6")
      (footprint "eagle-import:QFN48G-0.4-6X6MM")
      (libsource (lib "eagle-import") (part "MCU-ESP32-DD0WDQ6"))
    )
    (comp (ref "U3")
      (value "W25Q32JVZPIG")
      (footprint "eagle-import:SOIC8-1.27-5X4MM")
      (libsource (lib "eagle-import") (part "FLASH-W25X80-5X4-SN"))
    )
    (comp (ref "U4")
      (value "ADC1173")
      (footprint "eagle-import:TSSOP24-0.65-7.8X4.4MM")
      (libsource (lib "eagle-import") (part "CONVERTER-ADC1173"))
    )
    (comp (ref "U5")
      (value "CP2102-GMR")
      (footprint "eagle-import:QFN28")
      (libsource (lib "eagle-import") (part "TRANSFER_CP2102_9"))
    )
    (comp (ref "U6")
      (value "DAC7311IDCKR")
      (footprint "eagle-import:SC-70-6")
      (libsource (lib "eagle-import") (part "CONVERTER-DAC7311"))
    )
    (comp (ref "U7")
      (value "CJ1117-3V3")
      (footprint "eagle-import:SOT-223")
      (libsource (lib "eagle-import") (part "PMIC-CJ1117S"))
    )
    (comp (ref "U8")
      (value "XC6221B102MR")
      (footprint "eagle-import:SOT-23-5")
      (libsource (lib "eagle-import") (part "PMIC-LDO-XC6210"))
    )
    (comp (ref "U9")
      (value "RT9013-18GB")
      (footprint "eagle-import:SOT-23-5")
      (libsource (lib "eagle-import") (part "PMIC-LDO-XC6210"))
    )
    (comp (ref "U10")
      (value "Arduino pins")
      (footprint "eagle-import:ARDUINO-32P")
      (libsource (lib "eagle-import") (part "ARDUINO-32P"))
    )
    (comp (ref "U11")
      (value "TPS62130")
      (footprint "eagle-import:VQFN16-0.5-3X3X1MM")
      (libsource (lib "eagle-import") (part "PMIC-TPS62140"))
    )
    (comp (ref "U12")
      (value "LSM6DS3TR")
      (footprint "eagle-import:LGA14L_DOT_INDICATOR")
      (libsource (lib "eagle-import") (part "SENSOR-LSM6DS3DOT_INDICATION"))
    )
    (comp (ref "U13")
      (value "PCA9306DQER")
      (footprint "eagle-import:X2SON8-0.35-1.4X1X0.37MM")
      (libsource (lib "eagle-import") (part "TRANSLATOR-PCA9306DQER"))
    )
    (comp (ref "U15")
      (value "RCLAMP0524P")
      (footprint "eagle-import:ESD10P-0.5-2.5X1X0.58MM")
      (libsource (lib "eagle-import") (part "ESD-RCLAMP0524P"))
    )
    (comp (ref "U16")
      (value "RCLAMP0524P")
      (footprint "eagle-import:ESD10P-0.5-2.5X1X0.58MM")
      (libsource (lib "eagle-import") (part "ESD-RCLAMP0524P"))
    )
    (comp (ref "U17")
      (value "TXS0104EPWR")
      (footprint "eagle-import:TSSOP14-0.65-5X4.4MM")
      (libsource (lib "eagle-import") (part "TRANSLATOR-TXS0104E"))
    )
    (comp (ref "U18")
      (value "TXS0104EPWR")
      (footprint "eagle-import:TSSOP14-0.65-5X4.4MM")
      (libsource (lib "eagle-import") (part "TRANSLATOR-TXS0104E"))
    )
    (comp (ref "USB2")
      (value "320010516/ ST-USB-1410")
      (footprint "eagle-import:USB2.0-TYPE-C")
      (libsource (lib "eagle-import") (part "USB2.0-TYPE-C"))
    )
    (comp (ref "X2")
      (value "O3225100MEDA4SC")
      (footprint "eagle-import:X4-SMD-3.2X2.5X1MM")
      (libsource (lib "eagle-import") (part "CRYSTAL-OSCILLATOR-3225"))
    )
    (comp (ref "X3")
      (value "XTL581100-M118-080")
      (footprint "eagle-import:X4-SMD-2.5X2.0X1.0MM")
      (libsource (lib "eagle-import") (part "CRYSTAL-4P-2520"))
    )
  )
  (nets
    (net (code "1") (name "3V3_IMU") (class "Default")
      (node (ref "C84") (pin "1") (pinfunction "1_1") (pintype "passive"))
      (node (ref "C97") (pin "2") (pinfunction "2_2") (pintype "passive"))
      (node (ref "C99") (pin "1") (pinfunction "1_1") (pintype "passive"))
      (node (ref "FB5") (pin "2") (pinfunction "2_2") (pintype "bidirectional"))
      (node (ref "R114") (pin "2") (pinfunction "2_2") (pintype "passive"))
      (node (ref "R117") (pin "2") (pinfunction "2_2") (pintype "passive"))
      (node (ref "U12") (pin "5") (pinfunction "VDDIO_5") (pintype "bidirectional"))
      (node (ref "U12") (pin "8") (pinfunction "VDD_8") (pintype "bidirectional"))
    )
    (net (code "2") (name "ADC_CLK") (class "Default")
      (node (ref "U1") (pin "C5") (pinfunction "IO_L6P_T0_34_C5") (pintype "bidirectional"))
      (node (ref "U4") (pin "12") (pinfunction "CLK_12") (pintype "bidirectional"))
    )
    (net (code "3") (name "ADC_D0") (class "Default")
      (node (ref "U1") (pin "J3") (pinfunction "IO_L17N_T2_34_J3") (pintype "bidirectional"))
      (node (ref "U4") (pin "3") (pinfunction "DO(LSB)_3") (pintype "bidirectional"))
    )
    (net (code "4") (name "ADC_D1") (class "Default")
      (node (ref "U1") (pin "J2") (pinfunction "IO_L15P_T2_DQS_34_J2") (pintype "bidirectional"))
      (node (ref "U4") (pin "4") (pinfunction "D1_4") (pintype "bidirectional"))
    )
    (net (code "5") (name "ADC_D2") (class "Default")
      (node (ref "U1") (pin "D12") (pinfunction "IO_L8P_T1_D11_14_D12") (pintype "bidirectional"))
      (node (ref "U4") (pin "5") (pinfunction "D2_5") (pintype "bidirectional"))
    )
    (net (code "6") (name "ADC_D3") (class "Default")
      (node (ref "U1") (pin "E12") (pinfunction "IO_L7N_T1_D10_14_E12") (pintype "bidirectional"))
      (node (ref "U4") (pin "6") (pinfunction "D3_6") (pintype "bidirectional"))
    )
    (net (code "7") (name "ADC_D4") (class "Default")
      (node (ref "U1") (pin "F12") (pinfunction "IO_L7P_T1_D09_14_F12") (pintype "bidirectional"))
      (node (ref "U4") (pin "7") (pinfunction "D4_7") (pintype "bidirectional"))
    )
    (net (code "8") (name "ADC_D5") (class "Default")
      (node (ref "U1") (pin "C11") (pinfunction "IO_L6P_T0_FCS_B_14_C11") (pintype "bidirectional"))
      (node (ref "U4") (pin "8") (pinfunction "D8_8") (pintype "bidirectional"))
    )
    (net (code "9") (name "ADC_D6") (class "Default")
      (node (ref "U1") (pin "H11") (pinfunction "IO_L13P_T2_MRCC_14_H11") (pintype "bidirectional"))
      (node (ref "U4") (pin "9") (pinfunction "D6_9") (pintype "bidirectional"))
    )
    (net (code "10") (name "ADC_D7") (class "Default")
      (node (ref "U1") (pin "H12") (pinfunction "IO_L13N_T2_MRCC_14_H12") (pintype "bidirectional"))
      (node (ref "U4") (pin "10") (pinfunction "D7(MSB)_10") (pintype "bidirectional"))
    )
    (net (code "11") (name "ADC_EN") (class "Default")
      (node (ref "U1") (pin "J4") (pinfunction "IO_L17P_T2_34_J4") (pintype "bidirectional"))
      (node (ref "U4") (pin "1") (pinfunction "~{OE}_1") (pintype "bidirectional"))
    )
    (net (code "12") (name "ADC_IN") (class "Default")
      (node (ref "C87") (pin "1") (pinfunction "1_1") (pintype "passive"))
      (node (ref "J1") (pin "1") (pinfunction "P$1_1") (pintype "bidirectional"))
      (node (ref "U4") (pin "19") (pinfunction "VIN_19") (pintype "bidirectional"))
    )
    (net (code "13") (name "AR_3V3_EN") (class "Default")
      (node (ref "Q2") (pin "1") (pinfunction "G_1") (pintype "passive"))
      (node (ref "Q3") (pin "1") (pinfunction "G_1") (pintype "passive"))
      (node (ref "R48") (pin "1") (pinfunction "1_1") (pintype "passive"))
      (node (ref "U1") (pin "L13") (pinfunction "IO_L16N_T2_D31_14_L13") (pintype "bidirectional"))
    )
    (net (code "14") (name "AR_A0") (class "Default")
      (node (ref "R32") (pin "2") (pinfunction "2_2") (pintype "passive"))
      (node (ref "U10") (pin "19") (pinfunction "PC0/AD0/D14_19") (pintype "bidirectional"))
    )
    (net (code "15") (name "AR_A1") (class "Default")
      (node (ref "R34") (pin "2") (pinfunction "2_2") (pintype "passive"))
      (node (ref "U10") (pin "20") (pinfunction "PC1/AD1/D15_20") (pintype "bidirectional"))
    )
    (net (code "16") (name "AR_A2") (class "Default")
      (node (ref "R36") (pin "2") (pinfunction "2_2") (pintype "passive"))
      (node (ref "U10") (pin "21") (pinfunction "PC2/AD2/D16_21") (pintype "bidirectional"))
    )
    (net (code "17") (name "AR_A3") (class "Default")
      (node (ref "R119") (pin "2") (pinfunction "2_2") (pintype "passive"))
      (node (ref "U10") (pin "22") (pinfunction "PC3/AD3/D17_22") (pintype "bidirectional"))
    )
    (net (code "18") (name "AR_A4") (class "Default")
      (node (ref "R121") (pin "2") (pinfunction "2_2") (pintype "passive"))
      (node (ref "U10") (pin "23") (pinfunction "PC4/AD4/D18/SDA_23") (pintype "bidirectional"))
    )
    (net (code "19") (name "AR_A5") (class "Default")
      (node (ref "R123") (pin "2") (pinfunction "2_2") (pintype "passive"))
      (node (ref "U10") (pin "24") (pinfunction "PC5/AD5/D19/SCL_24") (pintype "bidirectional"))
    )
    (net (code "20") (name "AR_D0{slash}RX") (class "Default")
      (node (ref "R150") (pin "1") (pinfunction "1_1") (pintype "passive"))
      (node (ref "U10") (pin "1") (pinfunction "PD0/D0/RX_1") (pintype "bidirectional"))
      (node (ref "U17") (pin "11") (pinfunction "B3_11") (pintype "bidirectional"))
    )
    (net (code "21") (name "AR_D1{slash}TX") (class "Default")
      (node (ref "R146") (pin "1") (pinfunction "1_1") (pintype "passive"))
      (node (ref "U10") (pin "2") (pinfunction "PD1/D1/TX_2") (pintype "bidirectional"))
      (node (ref "U17") (pin "10") (pinfunction "B4_10") (pintype "bidirectional"))
    )
    (net (code "22") (name "AR_D2") (class "Default")
      (node (ref "R152") (pin "2") (pinfunction "2_2") (pintype "passive"))
      (node (ref "U10") (pin "3") (pinfunction "PD2/D2/INT0_3") (pintype "bidirectional"))
    )
    (net (code "23") (name "AR_D3") (class "Default")
      (node (ref "R154") (pin "2") (pinfunction "2_2") (pintype "passive"))
      (node (ref "U10") (pin "4") (pinfunction "PD3/D3/INT1/PWM_4") (pintype "bidirectional"))
    )
    (net (code "24") (name "AR_D4") (class "Default")
      (node (ref "R156") (pin "2") (pinfunction "2_2") (pintype "passive"))
      (node (ref "U10") (pin "5") (pinfunction "PD4/D4_5") (pintype "bidirectional"))
    )
    (net (code "25") (name "AR_D5") (class "Default")
      (node (ref "R158") (pin "2") (pinfunction "2_2") (pintype "passive"))
      (node (ref "U10") (pin "6") (pinfunction "PD5/D5/PWM_6") (pintype "bidirectional"))
    )
    (net (code "26") (name "AR_D6") (class "Default")
      (node (ref "R172") (pin "2") (pinfunction "2_2") (pintype "passive"))
      (node (ref "U10") (pin "7") (pinfunction "PD6/D6/PWM_7") (pintype "bidirectional"))
    )
    (net (code "27") (name "AR_D7") (class "Default")
      (node (ref "R174") (pin "2") (pinfunction "2_2") (pintype "passive"))
      (node (ref "U10") (pin "8") (pinfunction "PD7/D7_8") (pintype "bidirectional"))
    )
    (net (code "28") (name "AR_D8") (class "Default")
      (node (ref "R176") (pin "2") (pinfunction "2_2") (pintype "passive"))
      (node (ref "U10") (pin "9") (pinfunction "PB0/D8_9") (pintype "bidirectional"))
    )
    (net (code "29") (name "AR_D9") (class "Default")
      (node (ref "R178") (pin "2") (pinfunction "2_2") (pintype "passive"))
      (node (ref "U10") (pin "10") (pinfunction "PB1/D9/PWM_10") (pintype "bidirectional"))
    )
    (net (code "30") (name "AR_D10") (class "Default")
      (node (ref "R160") (pin "2") (pinfunction "2_2") (pintype "passive"))
      (node (ref "U10") (pin "11") (pinfunction "PB2/D10/SS/PWM_11") (pintype "bidirectional"))
    )
    (net (code "31") (name "AR_D11") (class "Default")
      (node (ref "R162") (pin "2") (pinfunction "2_2") (pintype "passive"))
      (node (ref "U10") (pin "12") (pinfunction "PB3/D11/MOSI/PWM_12") (pintype "bidirectional"))
    )
    (net (code "32") (name "AR_D12") (class "Default")
      (node (ref "R164") (pin "2") (pinfunction "2_2") (pintype "passive"))
      (node (ref "U10") (pin "13") (pinfunction "PB4/D12/MISO_13") (pintype "bidirectional"))
    )
    (net (code "33") (name "AR_D13") (class "Default")
      (node (ref "R166") (pin "2") (pinfunction "2_2") (pintype "passive"))
      (node (ref "U10") (pin "14") (pinfunction "PB5/D13/SCK_14") (pintype "bidirectional"))
    )
    (net (code "34") (name "AR_MISO") (class "Default")
      (node (ref "J5") (pin "1") (pinfunction "1_1") (pintype "bidirectional"))
      (node (ref "U18") (pin "11") (pinfunction "B3_11") (pintype "bidirectional"))
    )
    (net (code "35") (name "AR_MOSI") (class "Default")
      (node (ref "J5") (pin "5") (pinfunction "5_5") (pintype "bidirectional"))
      (node (ref "U18") (pin "12") (pinfunction "B2_12") (pintype "bidirectional"))
    )
    (net (code "36") (name "AR_RESET") (class "Default")
      (node (ref "J5") (pin "3") (pinfunction "3_3") (pintype "bidirectional"))
      (node (ref "R187") (pin "2") (pinfunction "2_2") (pintype "passive"))
      (node (ref "U10") (pin "30") (pinfunction "RESET_30") (pintype "bidirectional"))
      (node (ref "U18") (pin "10") (pinfunction "B4_10") (pintype "bidirectional"))
    )
    (net (code "37") (name "AR_SCK") (class "Default")
      (node (ref "J5") (pin "2") (pinfunction "2_2") (pintype "bidirectional"))
      (node (ref "U18") (pin "13") (pinfunction "B1_13") (pintype "bidirectional"))
    )
    (net (code "38") (name "AR_SCL") (class "Default")
      (node (ref "R151") (pin "1") (pinfunction "1_1") (pintype "passive"))
      (node (ref "U10") (pin "18") (pinfunction "SCL_18") (pintype "bidirectional"))
      (node (ref "U17") (pin "12") (pinfunction "B2_12") (pintype "bidirectional"))
    )
    (net (code "39") (name "AR_SDA") (class "Default")
      (node (ref "R171") (pin "1") (pinfunction "1_1") (pintype "passive"))
      (node (ref "U10") (pin "17") (pinfunction "SDA_17") (pintype "bidirectional"))
      (node (ref "U17") (pin "13") (pinfunction "B1_13") (pintype "bidirectional"))
    )
    (net (code "40") (name "CHIP_PU") (class "Default")
      (node (ref "Q4") (pin "3") (pinfunction "C_3") (pintype "passive"))
      (node (ref "R5") (pin "1") (pinfunction "1_1") (pintype "passive"))
      (node (ref "RST") (pin "1") (pinfunction "A0_1") (pintype "bidirectional"))
      (node (ref "RST") (pin "2") (pinfunction "A1_2") (pintype "bidirectional"))
      (node (ref "U2") (pin "9") (pinfunction "CHIP_PU_9") (pintype "bidirectional"))
    )
    (net (code "41") (name "D+") (class "Default")
      (node (ref "D1") (pin "2") (pinfunction "2_2") (pintype "bidirectional"))
      (node (ref "L15") (pin "3") (pinfunction "3_3") (pintype "bidirectional"))
      (node (ref "USB2") (pin "A6") (pinfunction "A6/DP1_A6") (pintype "bidirectional"))
      (node (ref "USB2") (pin "B6") (pinfunction "B6/DP2_B6") (pintype "bidirectional"))
    )
    (net (code "42") (name "D-") (class "Default")
      (node (ref "D2") (pin "2") (pinfunction "2_2") (pintype "bidirectional"))
      (node (ref "L15") (pin "2") (pinfunction "2_2") (pintype "bidirectional"))
      (node (ref "USB2") (pin "A7") (pinfunction "A7/DN1_A7") (pintype "bidirectional"))
      (node (ref "USB2") (pin "B7") (pinfunction "B7/DN2_B7") (pintype "bidirectional"))
    )
    (net (code "43") (name "DAC_DIN") (class "Default")
      (node (ref "U1") (pin "L1") (pinfunction "IO_L18N_T2_34_L1") (pintype "bidirectional"))
      (node (ref "U6") (pin "3") (pinfunction "DIN_3") (pintype "bidirectional"))
    )
    (net (code "44") (name "DAC_OUT") (class "Default")
      (node (ref "C86") (pin "1") (pinfunction "1_1") (pintype "passive"))
      (node (ref "J1") (pin "4") (pinfunction "P$4_4") (pintype "bidirectional"))
      (node (ref "U6") (pin "6") (pinfunction "VOUT_6") (pintype "bidirectional"))
    )
    (net (code "45") (name "DAC_SCLK") (class "Default")
      (node (ref "U1") (pin "M1") (pinfunction "IO_L18P_T2_34_M1") (pintype "bidirectional"))
      (node (ref "U6") (pin "2") (pinfunction "SCLK_2") (pintype "bidirectional"))
    )
    (net (code "46") (name "DAC_SYNC") (class "Default")
      (node (ref "U1") (pin "N1") (pinfunction "IO_L20N_T3_34_N1") (pintype "bidirectional"))
      (node (ref "U6") (pin "1") (pinfunction "~{SYNC}_1") (pintype "bidirectional"))
    )
    (net (code "47") (name "ESP_A4") (class "Default")
      (node (ref "R121") (pin "1") (pinfunction "1_1") (pintype "passive"))
      (node (ref "R122") (pin "1") (pinfunction "1_1") (pintype "passive"))
      (node (ref "SW2") (pin "11") (pinfunction "NO1_11") (pintype "bidirectional"))
    )
    (net (code "48") (name "ESP_A5") (class "Default")
      (node (ref "R123") (pin "1") (pinfunction "1_1") (pintype "passive"))
      (node (ref "R124") (pin "1") (pinfunction "1_1") (pintype "passive"))
      (node (ref "SW2") (pin "15") (pinfunction "NO2_15") (pintype "bidirectional"))
    )
    (net (code "49") (name "ESP_AR_A0") (class "Default")
      (node (ref "R32") (pin "1") (pinfunction "1_1") (pintype "passive"))
      (node (ref "R33") (pin "1") (pinfunction "1_1") (pintype "passive"))
      (node (ref "U2") (pin "5") (pinfunction "SENSOR_VP_5") (pintype "bidirectional"))
    )
    (net (code "50") (name "ESP_AR_A1") (class "Default")
      (node (ref "R34") (pin "1") (pinfunction "1_1") (pintype "passive"))
      (node (ref "R35") (pin "1") (pinfunction "1_1") (pintype "passive"))
      (node (ref "U2") (pin "6") (pinfunction "SENSOR_CAPP_6") (pintype "bidirectional"))
    )
    (net (code "51") (name "ESP_AR_A2") (class "Default")
      (node (ref "R118") (pin "1") (pinfunction "1_1") (pintype "passive"))
      (node (ref "R36") (pin "1") (pinfunction "1_1") (pintype "passive"))
      (node (ref "U2") (pin "7") (pinfunction "SENSOR_CAPN_7") (pintype "bidirectional"))
    )
    (net (code "52") (name "ESP_AR_A3") (class "Default")
      (node (ref "R119") (pin "1") (pinfunction "1_1") (pintype "passive"))
      (node (ref "R120") (pin "1") (pinfunction "1_1") (pintype "passive"))
      (node (ref "U2") (pin "8") (pinfunction "SENSOR_VN_8") (pintype "bidirectional"))
    )
    (net (code "53") (name "ESP_FPGA-TYPE") (class "Default")
      (node (ref "R125") (pin "1") (pinfunction "1_1") (pintype "passive"))
      (node (ref "R126") (pin "2") (pinfunction "2_2") (pintype "passive"))
      (node (ref "U2") (pin "11") (pinfunction "VDET_2_11") (pintype "bidirectional"))
    )
    (net (code "54") (name "ESP_QSPI_CLK") (class "Default")
      (node (ref "R84") (pin "2") (pinfunction "2_2") (pintype "passive"))
      (node (ref "U2") (pin "35") (pinfunction "GPIO18_35") (pintype "bidirectional"))
    )
    (net (code "55") (name "ESP_QSPI_CS") (class "Default")
      (node (ref "R115") (pin "2") (pinfunction "2_2") (pintype "passive"))
      (node (ref "U2") (pin "34") (pinfunction "GPIO5_34") (pintype "bidirectional"))
    )
    (net (code "56") (name "ESP_QSPI_D") (class "Default")
      (node (ref "R141") (pin "2") (pinfunction "2_2") (pintype "passive"))
      (node (ref "U2") (pin "36") (pinfunction "GPIO23_36") (pintype "bidirectional"))
    )
    (net (code "57") (name "ESP_QSPI_HD") (class "Default")
      (node (ref "R142") (pin "2") (pinfunction "2_2") (pintype "passive"))
      (node (ref "U2") (pin "42") (pinfunction "GPIO21_42") (pintype "bidirectional"))
    )
    (net (code "58") (name "ESP_QSPI_Q") (class "Default")
      (node (ref "R140") (pin "2") (pinfunction "2_2") (pintype "passive"))
      (node (ref "U2") (pin "38") (pinfunction "GPIO19_38") (pintype "bidirectional"))
    )
    (net (code "59") (name "ESP_QSPI_WP") (class "Default")
      (node (ref "R143") (pin "2") (pinfunction "2_2") (pintype "passive"))
      (node (ref "U2") (pin "39") (pinfunction "GPIO22_39") (pintype "bidirectional"))
    )
    (net (code "60") (name "ESP_SCL_A5") (class "Default")
      (node (ref "SW2") (pin "16") (pinfunction "COM2_16") (pintype "bidirectional"))
      (node (ref "U2") (pin "13") (pinfunction "32K_XN_13") (pintype "bidirectional"))
    )
    (net (code "61") (name "ESP_SDA_A4") (class "Default")
      (node (ref "SW2") (pin "12") (pinfunction "COM1_12") (pintype "bidirectional"))
      (node (ref "U2") (pin "12") (pinfunction "32K_XP_12") (pintype "bidirectional"))
    )
    (net (code "62") (name "FLASH_SCK") (class "Default")
      (node (ref "R29") (pin "2") (pinfunction "2_2") (pintype "passive"))
      (node (ref "U2") (pin "31") (pinfunction "SD_CLK_31") (pintype "bidirectional"))
      (node (ref "U3") (pin "6") (pinfunction "CLK_6") (pintype "bidirectional"))
    )
    (net (code "63") (name "FLASH_SCS") (class "Default")
      (node (ref "R104") (pin "2") (pinfunction "2_2") (pintype "passive"))
      (node (ref "R28") (pin "2") (pinfunction "2_2") (pintype "passive"))
      (node (ref "U2") (pin "30") (pinfunction "SD_CMD_30") (pintype "bidirectional"))
      (node (ref "U3") (pin "1") (pinfunction "/CS_1") (pintype "bidirectional"))
    )
    (net (code "64") (name "FLASH_SDI") (class "Default")
      (node (ref "R69") (pin "2") (pinfunction "2_2") (pintype "passive"))
      (node (ref "U2") (pin "33") (pinfunction "SD_DATA_1_33") (pintype "bidirectional"))
      (node (ref "U3") (pin "5") (pinfunction "DIO_5") (pintype "bidirectional"))
    )
    (net (code "65") (name "FLASH_SDO") (class "Default")
      (node (ref "R68") (pin "2") (pinfunction "2_2") (pintype "passive"))
      (node (ref "U2") (pin "32") (pinfunction "SD_DATA_0_32") (pintype "bidirectional"))
      (node (ref "U3") (pin "2") (pinfunction "DO_2") (pintype "bidirectional"))
    )
    (net (code "66") (name "FLASH_SHD") (class "Default")
      (node (ref "R127") (pin "2") (pinfunction "2_2") (pintype "passive"))
      (node (ref "TP1") (pin "T") (pinfunction "T_T") (pintype "bidirectional"))
      (node (ref "U2") (pin "28") (pinfunction "SD_DATA_2_28") (pintype "bidirectional"))
      (node (ref "U3") (pin "7") (pinfunction "/HOLD_7") (pintype "bidirectional"))
    )
    (net (code "67") (name "FLASH_SWP") (class "Default")
      (node (ref "R116") (pin "2") (pinfunction "2_2") (pintype "passive"))
      (node (ref "TP2") (pin "T") (pinfunction "T_T") (pintype "bidirectional"))
      (node (ref "U2") (pin "29") (pinfunction "SD_DATA_3_29") (pintype "bidirectional"))
      (node (ref "U3") (pin "3") (pinfunction "/WP_3") (pintype "bidirectional"))
    )
    (net (code "68") (name "FLASH_VDD") (class "Default")
      (node (ref "R2") (pin "2") (pinfunction "2_2") (pintype "passive"))
      (node (ref "U2") (pin "26") (pinfunction "VDD_SDIO_26") (pintype "bidirectional"))
    )
    (net (code "69") (name "FPGA_AR_D0{slash}RX") (class "Default")
      (node (ref "R181") (pin "1") (pinfunction "1_1") (pintype "passive"))
      (node (ref "U1") (pin "A12") (pinfunction "IO_L4P_T0_D04_14_A12") (pintype "bidirectional"))
      (node (ref "U17") (pin "4") (pinfunction "A3_4") (pintype "bidirectional"))
    )
    (net (code "70") (name "FPGA_AR_D1{slash}TX") (class "Default")
      (node (ref "R182") (pin "1") (pinfunction "1_1") (pintype "passive"))
      (node (ref "U1") (pin "C12") (pinfunction "IO_L6N_T0_D08_VREF_14_C12") (pintype "bidirectional"))
      (node (ref "U17") (pin "5") (pinfunction "A4_5") (pintype "bidirectional"))
    )
    (net (code "71") (name "FPGA_AR_D2") (class "Default")
      (node (ref "J2") (pin "1") (pinfunction "1_1") (pintype "bidirectional"))
      (node (ref "R152") (pin "1") (pinfunction "1_1") (pintype "passive"))
      (node (ref "R153") (pin "1") (pinfunction "1_1") (pintype "passive"))
      (node (ref "U1") (pin "A10") (pinfunction "IO_L3N_T0_DQS_EMCCLK_14_A10") (pintype "bidirectional"))
    )
    (net (code "72") (name "FPGA_AR_D3") (class "Default")
      (node (ref "J2") (pin "2") (pinfunction "2_2") (pintype "bidirectional"))
      (node (ref "R154") (pin "1") (pinfunction "1_1") (pintype "passive"))
      (node (ref "R155") (pin "1") (pinfunction "1_1") (pintype "passive"))
      (node (ref "U1") (pin "B6") (pinfunction "IO_0_34_B6") (pintype "bidirectional"))
    )
    (net (code "73") (name "FPGA_AR_D4") (class "Default")
      (node (ref "R156") (pin "1") (pinfunction "1_1") (pintype "passive"))
      (node (ref "R157") (pin "1") (pinfunction "1_1") (pintype "passive"))
      (node (ref "U1") (pin "A5") (pinfunction "IO_L4N_T0_34_A5") (pintype "bidirectional"))
    )
    (net (code "74") (name "FPGA_AR_D5") (class "Default")
      (node (ref "R158") (pin "1") (pinfunction "1_1") (pintype "passive"))
      (node (ref "R159") (pin "1") (pinfunction "1_1") (pintype "passive"))
      (node (ref "U1") (pin "B5") (pinfunction "IO_L4P_T0_34_B5") (pintype "bidirectional"))
    )
    (net (code "75") (name "FPGA_AR_D6") (class "Default")
      (node (ref "R172") (pin "1") (pinfunction "1_1") (pintype "passive"))
      (node (ref "R173") (pin "1") (pinfunction "1_1") (pintype "passive"))
      (node (ref "U1") (pin "A4") (pinfunction "IO_L2P_T0_34_A4") (pintype "bidirectional"))
    )
    (net (code "76") (name "FPGA_AR_D7") (class "Default")
      (node (ref "R174") (pin "1") (pinfunction "1_1") (pintype "passive"))
      (node (ref "R175") (pin "1") (pinfunction "1_1") (pintype "passive"))
      (node (ref "U1") (pin "A3") (pinfunction "IO_L2N_T0_34_A3") (pintype "bidirectional"))
    )
    (net (code "77") (name "FPGA_AR_D8") (class "Default")
      (node (ref "R176") (pin "1") (pinfunction "1_1") (pintype "passive"))
      (node (ref "R177") (pin "1") (pinfunction "1_1") (pintype "passive"))
      (node (ref "U1") (pin "B3") (pinfunction "IO_L3P_T0_DQS_34_B3") (pintype "bidirectional"))
    )
    (net (code "78") (name "FPGA_AR_D9") (class "Default")
      (node (ref "R178") (pin "1") (pinfunction "1_1") (pintype "passive"))
      (node (ref "R179") (pin "1") (pinfunction "1_1") (pintype "passive"))
      (node (ref "U1") (pin "A2") (pinfunction "IO_L3N_T0_DQS_34_A2") (pintype "bidirectional"))
    )
    (net (code "79") (name "FPGA_AR_D10") (class "Default")
      (node (ref "R160") (pin "1") (pinfunction "1_1") (pintype "passive"))
      (node (ref "R161") (pin "1") (pinfunction "1_1") (pintype "passive"))
      (node (ref "U1") (pin "B2") (pinfunction "IO_L5P_T0_34_B2") (pintype "bidirectional"))
    )
    (net (code "80") (name "FPGA_AR_D11") (class "Default")
      (node (ref "R162") (pin "1") (pinfunction "1_1") (pintype "passive"))
      (node (ref "R163") (pin "1") (pinfunction "1_1") (pintype "passive"))
      (node (ref "U1") (pin "B1") (pinfunction "IO_L5N_T0_34_B1") (pintype "bidirectional"))
    )
    (net (code "81") (name "FPGA_AR_D12") (class "Default")
      (node (ref "R164") (pin "1") (pinfunction "1_1") (pintype "passive"))
      (node (ref "R165") (pin "1") (pinfunction "1_1") (pintype "passive"))
      (node (ref "U1") (pin "H1") (pinfunction "IO_L14N_T2_SRCC_34_H1") (pintype "bidirectional"))
    )
    (net (code "82") (name "FPGA_AR_D13") (class "Default")
      (node (ref "R166") (pin "1") (pinfunction "1_1") (pintype "passive"))
      (node (ref "R167") (pin "1") (pinfunction "1_1") (pintype "passive"))
      (node (ref "U1") (pin "H2") (pinfunction "IO_L14P_T2_SRCC_34_H2") (pintype "bidirectional"))
    )
    (net (code "83") (name "FPGA_AR_DET") (class "Default")
      (node (ref "R49") (pin "2") (pinfunction "2_2") (pintype "passive"))
      (node (ref "R71") (pin "2") (pinfunction "2_2") (pintype "passive"))
      (node (ref "U1") (pin "B11") (pinfunction "IO_L1P_T0_D00_MOSI_14_B11") (pintype "bidirectional"))
    )
    (net (code "84") (name "FPGA_AR_MISO") (class "Default")
      (node (ref "U1") (pin "L5") (pinfunction "IO_25_34_L5") (pintype "bidirectional"))
      (node (ref "U18") (pin "4") (pinfunction "A3_4") (pintype "bidirectional"))
    )
    (net (code "85") (name "FPGA_AR_MOSI") (class "Default")
      (node (ref "U1") (pin "M5") (pinfunction "IO_L23P_T3_34_M5") (pintype "bidirectional"))
      (node (ref "U18") (pin "3") (pinfunction "A2_3") (pintype "bidirectional"))
    )
    (net (code "86") (name "FPGA_AR_OE1") (class "Default")
      (node (ref "R183") (pin "2") (pinfunction "2_2") (pintype "passive"))
      (node (ref "R184") (pin "2") (pinfunction "2_2") (pintype "passive"))
      (node (ref "U1") (pin "N4") (pinfunction "IO_L24N_T3_34_N4") (pintype "bidirectional"))
      (node (ref "U17") (pin "8") (pinfunction "OE_8") (pintype "bidirectional"))
    )
    (net (code "87") (name "FPGA_AR_OE2") (class "Default")
      (node (ref "R185") (pin "2") (pinfunction "2_2") (pintype "passive"))
      (node (ref "U1") (pin "M3") (pinfunction "IO_L19P_T3_34_M3") (pintype "bidirectional"))
      (node (ref "U18") (pin "8") (pinfunction "OE_8") (pintype "bidirectional"))
    )
    (net (code "88") (name "FPGA_AR_RESET") (class "Default")
      (node (ref "R186") (pin "1") (pinfunction "1_1") (pintype "passive"))
      (node (ref "U1") (pin "K4") (pinfunction "IO_L16P_T2_34_K4") (pintype "bidirectional"))
      (node (ref "U18") (pin "5") (pinfunction "A4_5") (pintype "bidirectional"))
    )
    (net (code "89") (name "FPGA_AR_SCK") (class "Default")
      (node (ref "U1") (pin "H13") (pinfunction "IO_L14P_T2_SRCC_14_H13") (pintype "bidirectional"))
      (node (ref "U18") (pin "2") (pinfunction "A1_2") (pintype "bidirectional"))
    )
    (net (code "90") (name "FPGA_CAM_CN") (class "Default")
      (node (ref "J6") (pin "23") (pinfunction "23_23") (pintype "bidirectional"))
      (node (ref "J6") (pin "8") (pinfunction "8_8") (pintype "bidirectional"))
      (node (ref "R100") (pin "1") (pinfunction "1_1") (pintype "passive"))
      (node (ref "U1") (pin "F11") (pinfunction "IO_L12N_T1_MRCC_14_F11") (pintype "bidirectional"))
    )
    (net (code "91") (name "FPGA_CAM_CP") (class "Default")
      (node (ref "J6") (pin "24") (pinfunction "24_24") (pintype "bidirectional"))
      (node (ref "J6") (pin "9") (pinfunction "9_9") (pintype "bidirectional"))
      (node (ref "R100") (pin "2") (pinfunction "2_2") (pintype "passive"))
      (node (ref "U1") (pin "G11") (pinfunction "IO_L12P_T1_MRCC_14_G11") (pintype "bidirectional"))
    )
    (net (code "92") (name "FPGA_CAM_DN1") (class "Default")
      (node (ref "J6") (pin "20") (pinfunction "20_20") (pintype "bidirectional"))
      (node (ref "J6") (pin "5") (pinfunction "5_5") (pintype "bidirectional"))
      (node (ref "R99") (pin "1") (pinfunction "1_1") (pintype "passive"))
      (node (ref "U1") (pin "P11") (pinfunction "IO_L24N_T3_D16_14_P11") (pintype "bidirectional"))
    )
    (net (code "93") (name "FPGA_CAM_DNO") (class "Default")
      (node (ref "J6") (pin "17") (pinfunction "17_17") (pintype "bidirectional"))
      (node (ref "J6") (pin "2") (pinfunction "2_2") (pintype "bidirectional"))
      (node (ref "R128") (pin "1") (pinfunction "1_1") (pintype "passive"))
      (node (ref "R98") (pin "1") (pinfunction "1_1") (pintype "passive"))
      (node (ref "U1") (pin "J12") (pinfunction "IO_L17N_T2_D29_14_J12") (pintype "bidirectional"))
    )
    (net (code "94") (name "FPGA_CAM_DP1") (class "Default")
      (node (ref "J6") (pin "21") (pinfunction "21_21") (pintype "bidirectional"))
      (node (ref "J6") (pin "6") (pinfunction "6_6") (pintype "bidirectional"))
      (node (ref "R99") (pin "2") (pinfunction "2_2") (pintype "passive"))
      (node (ref "U1") (pin "P10") (pinfunction "IO_L24P_T3_D17_14_P10") (pintype "bidirectional"))
    )
    (net (code "95") (name "FPGA_CAM_DPO") (class "Default")
      (node (ref "J6") (pin "18") (pinfunction "18_18") (pintype "bidirectional"))
      (node (ref "J6") (pin "3") (pinfunction "3_3") (pintype "bidirectional"))
      (node (ref "R129") (pin "1") (pinfunction "1_1") (pintype "passive"))
      (node (ref "R98") (pin "2") (pinfunction "2_2") (pintype "passive"))
      (node (ref "U1") (pin "J11") (pinfunction "IO_L17P_T2_D30_14_J11") (pintype "bidirectional"))
    )
    (net (code "96") (name "FPGA_CAM_GPIO1") (class "Default")
      (node (ref "J6") (pin "12") (pinfunction "12_12") (pintype "bidirectional"))
      (node (ref "J6") (pin "27") (pinfunction "27_27") (pintype "bidirectional"))
      (node (ref "U1") (pin "M11") (pinfunction "IO_L20P_T3_D24_14_M11") (pintype "bidirectional"))
    )
    (net (code "97") (name "FPGA_CAM_RST") (class "Default")
      (node (ref "J6") (pin "11") (pinfunction "11_11") (pintype "bidirectional"))
      (node (ref "J6") (pin "26") (pinfunction "26_26") (pintype "bidirectional"))
      (node (ref "R38") (pin "1") (pinfunction "1_1") (pintype "passive"))
      (node (ref "U1") (pin "M12") (pinfunction "IO_L20N_T3_D23_14_M12") (pintype "bidirectional"))
    )
    (net (code "98") (name "FPGA_CAM_SCL") (class "Default")
      (node (ref "J6") (pin "13") (pinfunction "13_13") (pintype "bidirectional"))
      (node (ref "J6") (pin "28") (pinfunction "28_28") (pintype "bidirectional"))
      (node (ref "R30") (pin "1") (pinfunction "1_1") (pintype "passive"))
      (node (ref "U1") (pin "K11") (pinfunction "IO_L19P_T3_D26_14_K11") (pintype "bidirectional"))
    )
    (net (code "99") (name "FPGA_CAM_SDA") (class "Default")
      (node (ref "J6") (pin "14") (pinfunction "14_14") (pintype "bidirectional"))
      (node (ref "J6") (pin "29") (pinfunction "29_29") (pintype "bidirectional"))
      (node (ref "R31") (pin "1") (pinfunction "1_1") (pintype "passive"))
      (node (ref "U1") (pin "K12") (pinfunction "IO_L19N_T3_D25_VREF_14_K12") (pintype "bidirectional"))
    )
    (net (code "100") (name "FPGA_CCLK") (class "Default")
      (node (ref "R24") (pin "2") (pinfunction "2_2") (pintype "passive"))
      (node (ref "U1") (pin "A8") (pinfunction "CCLK_0_A8") (pintype "bidirectional"))
    )
    (net (code "101") (name "FPGA_CCLK_ESP") (class "Default")
      (node (ref "R24") (pin "1") (pinfunction "1_1") (pintype "passive"))
      (node (ref "U2") (pin "27") (pinfunction "GPIO17_27") (pintype "bidirectional"))
    )
    (net (code "102") (name "FPGA_CONFIG_DIN") (class "Default")
      (node (ref "R27") (pin "2") (pinfunction "2_2") (pintype "passive"))
      (node (ref "U1") (pin "B12") (pinfunction "IO_L1N_T0_D01_DIN_14_B12") (pintype "bidirectional"))
    )
    (net (code "103") (name "FPGA_CONFIG_DIN_ESP") (class "Default")
      (node (ref "R27") (pin "1") (pinfunction "1_1") (pintype "passive"))
      (node (ref "U2") (pin "16") (pinfunction "GPIO27_16") (pintype "bidirectional"))
    )
    (net (code "104") (name "FPGA_DONE") (class "Default")
      (node (ref "D20") (pin "+") (pinfunction "+_+") (pintype "passive"))
      (node (ref "R26") (pin "2") (pinfunction "2_2") (pintype "passive"))
      (node (ref "R55") (pin "2") (pinfunction "2_2") (pintype "passive"))
      (node (ref "U1") (pin "P9") (pinfunction "DONE_0_P9") (pintype "bidirectional"))
    )
    (net (code "105") (name "FPGA_DONE_ESP") (class "Default")
      (node (ref "R26") (pin "1") (pinfunction "1_1") (pintype "passive"))
      (node (ref "U2") (pin "10") (pinfunction "VDET_1_10") (pintype "bidirectional"))
    )
    (net (code "106") (name "FPGA_ESP_IN1{slash}2") (class "Default")
      (node (ref "R133") (pin "1") (pinfunction "1_1") (pintype "passive"))
      (node (ref "SW2") (pin "14") (pinfunction "IN1_2_14") (pintype "bidirectional"))
      (node (ref "U1") (pin "H3") (pinfunction "IO_L13N_T2_MRCC_34_H3") (pintype "bidirectional"))
    )
    (net (code "107") (name "FPGA_ESP_IO5") (class "Default")
      (node (ref "R28") (pin "1") (pinfunction "1_1") (pintype "passive"))
      (node (ref "U1") (pin "E13") (pinfunction "IO_L10N_T1_D15_14_E13") (pintype "bidirectional"))
    )
    (net (code "108") (name "FPGA_ESP_IO6") (class "Default")
      (node (ref "R29") (pin "1") (pinfunction "1_1") (pintype "passive"))
      (node (ref "U1") (pin "F14") (pinfunction "IO_L9N_T1_DQS_D13_14_F14") (pintype "bidirectional"))
    )
    (net (code "109") (name "FPGA_ESP_IO7") (class "Default")
      (node (ref "R68") (pin "1") (pinfunction "1_1") (pintype "passive"))
      (node (ref "U1") (pin "F13") (pinfunction "IO_L10P_T1_D14_14_F13") (pintype "bidirectional"))
    )
    (net (code "110") (name "FPGA_ESP_IO8") (class "Default")
      (node (ref "R69") (pin "1") (pinfunction "1_1") (pintype "passive"))
      (node (ref "U1") (pin "G14") (pinfunction "IO_L9P_T1_DQS_14_G14") (pintype "bidirectional"))
    )
    (net (code "111") (name "FPGA_ESP_SCL") (class "Default")
      (node (ref "J4") (pin "1") (pinfunction "1_1") (pintype "bidirectional"))
      (node (ref "R180") (pin "1") (pinfunction "1_1") (pintype "passive"))
      (node (ref "SW2") (pin "1") (pinfunction "NC2_1") (pintype "bidirectional"))
      (node (ref "U1") (pin "P12") (pinfunction "IO_L22P_T3_D21_14_P12") (pintype "bidirectional"))
      (node (ref "U12") (pin "13") (pinfunction "SCL_13") (pintype "bidirectional"))
      (node (ref "U17") (pin "3") (pinfunction "A2_3") (pintype "bidirectional"))
    )
    (net (code "112") (name "FPGA_ESP_SDA") (class "Default")
      (node (ref "J4") (pin "2") (pinfunction "2_2") (pintype "bidirectional"))
      (node (ref "R144") (pin "1") (pinfunction "1_1") (pintype "passive"))
      (node (ref "SW2") (pin "13") (pinfunction "NC1_13") (pintype "bidirectional"))
      (node (ref "U1") (pin "P13") (pinfunction "IO_L22N_T3_D20_14_P13") (pintype "bidirectional"))
      (node (ref "U12") (pin "14") (pinfunction "SDA_14") (pintype "bidirectional"))
      (node (ref "U17") (pin "2") (pinfunction "A1_2") (pintype "bidirectional"))
    )
    (net (code "113") (name "FPGA_HDMI_SCL") (class "Default")
      (node (ref "R42") (pin "2") (pinfunction "2_2") (pintype "passive"))
      (node (ref "U1") (pin "F3") (pinfunction "IO_L8P_T1_34_F3") (pintype "bidirectional"))
      (node (ref "U13") (pin "3") (pinfunction "SCL1_3") (pintype "bidirectional"))
    )
    (net (code "114") (name "FPGA_HDMI_SDA") (class "Default")
      (node (ref "R43") (pin "2") (pinfunction "2_2") (pintype "passive"))
      (node (ref "U1") (pin "F2") (pinfunction "IO_L8N_T1_34_F2") (pintype "bidirectional"))
      (node (ref "U13") (pin "4") (pinfunction "SDA1_4") (pintype "bidirectional"))
    )
    (net (code "115") (name "FPGA_HDMI_TCK+") (class "Default")
      (node (ref "L7") (pin "4") (pinfunction "2_4") (pintype "bidirectional"))
      (node (ref "R78") (pin "2") (pinfunction "2_2") (pintype "passive"))
      (node (ref "R90") (pin "2") (pinfunction "2_2") (pintype "passive"))
      (node (ref "U1") (pin "G4") (pinfunction "IO_L12P_T1_MRCC_34_G4") (pintype "bidirectional"))
    )
    (net (code "116") (name "FPGA_HDMI_TCK-") (class "Default")
      (node (ref "L7") (pin "3") (pinfunction "3_3") (pintype "bidirectional"))
      (node (ref "R79") (pin "2") (pinfunction "2_2") (pintype "passive"))
      (node (ref "R91") (pin "2") (pinfunction "2_2") (pintype "passive"))
      (node (ref "U1") (pin "F4") (pinfunction "IO_L12N_T1_MRCC_34_F4") (pintype "bidirectional"))
    )
    (net (code "117") (name "FPGA_HDMI_TD0+") (class "Default")
      (node (ref "L5") (pin "4") (pinfunction "2_4") (pintype "bidirectional"))
      (node (ref "R76") (pin "2") (pinfunction "2_2") (pintype "passive"))
      (node (ref "R88") (pin "2") (pinfunction "2_2") (pintype "passive"))
      (node (ref "U1") (pin "G1") (pinfunction "IO_L9P_T1_DQS_34_G1") (pintype "bidirectional"))
    )
    (net (code "118") (name "FPGA_HDMI_TD0-") (class "Default")
      (node (ref "L5") (pin "3") (pinfunction "3_3") (pintype "bidirectional"))
      (node (ref "R77") (pin "2") (pinfunction "2_2") (pintype "passive"))
      (node (ref "R89") (pin "2") (pinfunction "2_2") (pintype "passive"))
      (node (ref "U1") (pin "F1") (pinfunction "IO_L9N_T1_DQS_34_F1") (pintype "bidirectional"))
    )
    (net (code "119") (name "FPGA_HDMI_TD1+") (class "Default")
      (node (ref "L4") (pin "4") (pinfunction "2_4") (pintype "bidirectional"))
      (node (ref "R74") (pin "2") (pinfunction "2_2") (pintype "passive"))
      (node (ref "R86") (pin "2") (pinfunction "2_2") (pintype "passive"))
      (node (ref "U1") (pin "E2") (pinfunction "IO_L10P_T1_34_E2") (pintype "bidirectional"))
    )
    (net (code "120") (name "FPGA_HDMI_TD1-") (class "Default")
      (node (ref "L4") (pin "3") (pinfunction "3_3") (pintype "bidirectional"))
      (node (ref "R75") (pin "2") (pinfunction "2_2") (pintype "passive"))
      (node (ref "R87") (pin "2") (pinfunction "2_2") (pintype "passive"))
      (node (ref "U1") (pin "D2") (pinfunction "IO_L10N_T1_34_D2") (pintype "bidirectional"))
    )
    (net (code "121") (name "FPGA_HDMI_TD2+") (class "Default")
      (node (ref "L3") (pin "4") (pinfunction "2_4") (pintype "bidirectional"))
      (node (ref "R72") (pin "2") (pinfunction "2_2") (pintype "passive"))
      (node (ref "R80") (pin "2") (pinfunction "2_2") (pintype "passive"))
      (node (ref "U1") (pin "D1") (pinfunction "IO_L11P_T1_SRCC_34_D1") (pintype "bidirectional"))
    )
    (net (code "122") (name "FPGA_HDMI_TD2-") (class "Default")
      (node (ref "L3") (pin "3") (pinfunction "3_3") (pintype "bidirectional"))
      (node (ref "R73") (pin "2") (pinfunction "2_2") (pintype "passive"))
      (node (ref "R81") (pin "2") (pinfunction "2_2") (pintype "passive"))
      (node (ref "U1") (pin "C1") (pinfunction "IO_L11N_T1_SRCC_34_C1") (pintype "bidirectional"))
    )
    (net (code "123") (name "FPGA_INTB") (class "Default")
      (node (ref "R25") (pin "2") (pinfunction "2_2") (pintype "passive"))
      (node (ref "R54") (pin "2") (pinfunction "2_2") (pintype "passive"))
      (node (ref "U1") (pin "P8") (pinfunction "INIT_B_0_P8") (pintype "bidirectional"))
    )
    (net (code "124") (name "FPGA_INTB_ESP") (class "Default")
      (node (ref "R25") (pin "1") (pinfunction "1_1") (pintype "passive"))
      (node (ref "U2") (pin "15") (pinfunction "GPIO26_15") (pintype "bidirectional"))
    )
    (net (code "125") (name "FPGA_IO0") (class "Default")
      (node (ref "J10") (pin "1") (pinfunction "1_1") (pintype "bidirectional"))
      (node (ref "U1") (pin "N14") (pinfunction "IO_L21P_T3_DQS_14_N14") (pintype "bidirectional"))
    )
    (net (code "126") (name "FPGA_IO1") (class "Default")
      (node (ref "J10") (pin "2") (pinfunction "2_2") (pintype "bidirectional"))
      (node (ref "U1") (pin "M14") (pinfunction "IO_L21N_T3_DQS_D22_14_M14") (pintype "bidirectional"))
    )
    (net (code "127") (name "FPGA_IO2") (class "Default")
      (node (ref "J10") (pin "3") (pinfunction "3_3") (pintype "bidirectional"))
      (node (ref "U1") (pin "C4") (pinfunction "IO_L6N_T0_VREF_34_C4") (pintype "bidirectional"))
    )
    (net (code "128") (name "FPGA_IO3") (class "Default")
      (node (ref "J10") (pin "4") (pinfunction "4_4") (pintype "bidirectional"))
      (node (ref "U1") (pin "B13") (pinfunction "IO_L5P_T0_D06_14_B13") (pintype "bidirectional"))
    )
    (net (code "129") (name "FPGA_IO4") (class "Default")
      (node (ref "J10") (pin "5") (pinfunction "5_5") (pintype "bidirectional"))
      (node (ref "U1") (pin "N10") (pinfunction "IO_L23P_T3_D19_14_N10") (pintype "bidirectional"))
    )
    (net (code "130") (name "FPGA_IO5") (class "Default")
      (node (ref "J10") (pin "6") (pinfunction "6_6") (pintype "bidirectional"))
      (node (ref "U1") (pin "M10") (pinfunction "IO_25_14_M10") (pintype "bidirectional"))
    )
    (net (code "131") (name "FPGA_IO6") (class "Default")
      (node (ref "J10") (pin "7") (pinfunction "7_7") (pintype "bidirectional"))
      (node (ref "U1") (pin "B14") (pinfunction "IO_L5N_T0_D07_14_B14") (pintype "bidirectional"))
    )
    (net (code "132") (name "FPGA_IO7") (class "Default")
      (node (ref "J10") (pin "8") (pinfunction "8_8") (pintype "bidirectional"))
      (node (ref "U1") (pin "D3") (pinfunction "IO_L1P_T0_34_D3") (pintype "bidirectional"))
    )
    (net (code "133") (name "FPGA_IO8") (class "Default")
      (node (ref "J10") (pin "9") (pinfunction "9_9") (pintype "bidirectional"))
      (node (ref "U1") (pin "P5") (pinfunction "IO_L24P_T3_34_P5") (pintype "bidirectional"))
    )
    (net (code "134") (name "FPGA_IO9") (class "Default")
      (node (ref "J10") (pin "10") (pinfunction "10_10") (pintype "bidirectional"))
      (node (ref "U1") (pin "E11") (pinfunction "IO_0_14_E11") (pintype "bidirectional"))
    )
    (net (code "135") (name "FPGA_IO10") (class "Default")
      (node (ref "BUTTON1") (pin "1") (pinfunction "A0_1") (pintype "bidirectional"))
      (node (ref "BUTTON1") (pin "2") (pinfunction "A1_2") (pintype "bidirectional"))
      (node (ref "C96") (pin "1") (pinfunction "1_1") (pintype "passive"))
      (node (ref "R102") (pin "2") (pinfunction "2_2") (pintype "passive"))
      (node (ref "U1") (pin "C3") (pinfunction "IO_L1N_T0_34_C3") (pintype "bidirectional"))
    )
    (net (code "136") (name "FPGA_IO11") (class "Default")
      (node (ref "BUTTON2") (pin "1") (pinfunction "A0_1") (pintype "bidirectional"))
      (node (ref "BUTTON2") (pin "2") (pinfunction "A1_2") (pintype "bidirectional"))
      (node (ref "C98") (pin "1") (pinfunction "1_1") (pintype "passive"))
      (node (ref "R103") (pin "2") (pinfunction "2_2") (pintype "passive"))
      (node (ref "U1") (pin "M4") (pinfunction "IO_L23N_T3_34_M4") (pintype "bidirectional"))
    )
    (net (code "137") (name "FPGA_IO12") (class "Default")
      (node (ref "R128") (pin "2") (pinfunction "2_2") (pintype "passive"))
      (node (ref "U1") (pin "C10") (pinfunction "IO_L2N_T0_D03_14_C10") (pintype "bidirectional"))
    )
    (net (code "138") (name "FPGA_IO13") (class "Default")
      (node (ref "R129") (pin "2") (pinfunction "2_2") (pintype "passive"))
      (node (ref "U1") (pin "D10") (pinfunction "IO_L2P_T0_D02_14_D10") (pintype "bidirectional"))
    )
    (net (code "139") (name "FPGA_K1") (class "Default")
      (node (ref "R64") (pin "1") (pinfunction "1_1") (pintype "passive"))
      (node (ref "SW4") (pin "1") (pinfunction "1_1") (pintype "bidirectional"))
      (node (ref "U1") (pin "M2") (pinfunction "IO_L19N_T3_VREF_34_M2") (pintype "bidirectional"))
    )
    (net (code "140") (name "FPGA_K2") (class "Default")
      (node (ref "R63") (pin "1") (pinfunction "1_1") (pintype "passive"))
      (node (ref "SW4") (pin "2") (pinfunction "2_2") (pintype "bidirectional"))
      (node (ref "U1") (pin "L2") (pinfunction "IO_L22N_T3_34_L2") (pintype "bidirectional"))
    )
    (net (code "141") (name "FPGA_K3") (class "Default")
      (node (ref "R60") (pin "1") (pinfunction "1_1") (pintype "passive"))
      (node (ref "SW4") (pin "3") (pinfunction "3_3") (pintype "bidirectional"))
      (node (ref "U1") (pin "L3") (pinfunction "IO_L22P_T3_34_L3") (pintype "bidirectional"))
    )
    (net (code "142") (name "FPGA_K4") (class "Default")
      (node (ref "R59") (pin "1") (pinfunction "1_1") (pintype "passive"))
      (node (ref "SW4") (pin "4") (pinfunction "4_4") (pintype "bidirectional"))
      (node (ref "U1") (pin "K3") (pinfunction "IO_L16N_T2_34_K3") (pintype "bidirectional"))
    )
    (net (code "143") (name "FPGA_LED1") (class "Default")
      (node (ref "D18") (pin "+") (pinfunction "+_+") (pintype "passive"))
      (node (ref "U1") (pin "J1") (pinfunction "IO_L15N_T2_DQS_34_J1") (pintype "bidirectional"))
    )
    (net (code "144") (name "FPGA_LED2") (class "Default")
      (node (ref "D19") (pin "+") (pinfunction "+_+") (pintype "passive"))
      (node (ref "U1") (pin "A13") (pinfunction "IO_L4N_T0_D05_14_A13") (pintype "bidirectional"))
    )
    (net (code "145") (name "FPGA_M0") (class "Default")
      (node (ref "R57") (pin "2") (pinfunction "2_2") (pintype "passive"))
      (node (ref "U1") (pin "M7") (pinfunction "M0_0_M7") (pintype "bidirectional"))
    )
    (net (code "146") (name "FPGA_M1") (class "Default")
      (node (ref "R130") (pin "1") (pinfunction "1_1") (pintype "passive"))
      (node (ref "SW4") (pin "5") (pinfunction "5_5") (pintype "bidirectional"))
      (node (ref "U1") (pin "M8") (pinfunction "M1_0_M8") (pintype "bidirectional"))
    )
    (net (code "147") (name "FPGA_M2") (class "Default")
      (node (ref "R56") (pin "2") (pinfunction "2_2") (pintype "passive"))
      (node (ref "U1") (pin "M9") (pinfunction "M2_0_M9") (pintype "bidirectional"))
    )
    (net (code "148") (name "FPGA_PROGRAM") (class "Default")
      (node (ref "R23") (pin "2") (pinfunction "2_2") (pintype "passive"))
      (node (ref "R53") (pin "2") (pinfunction "2_2") (pintype "passive"))
      (node (ref "U1") (pin "L7") (pinfunction "PROGRAM_B_0_L7") (pintype "bidirectional"))
    )
    (net (code "149") (name "FPGA_PROGRAM_ESP") (class "Default")
      (node (ref "R23") (pin "1") (pinfunction "1_1") (pintype "passive"))
      (node (ref "U2") (pin "14") (pinfunction "GPIO25_14") (pintype "bidirectional"))
    )
    (net (code "150") (name "FPGA_QSPI_CLK") (class "Default")
      (node (ref "R84") (pin "1") (pinfunction "1_1") (pintype "passive"))
      (node (ref "U1") (pin "H14") (pinfunction "IO_L14N_T2_SRCC_14_H14") (pintype "bidirectional"))
    )
    (net (code "151") (name "FPGA_QSPI_CS") (class "Default")
      (node (ref "R115") (pin "1") (pinfunction "1_1") (pintype "passive"))
      (node (ref "U1") (pin "M13") (pinfunction "IO_L15P_T2_DQS_RDWR_B_14_M13") (pintype "bidirectional"))
    )
    (net (code "152") (name "FPGA_QSPI_D") (class "Default")
      (node (ref "R141") (pin "1") (pinfunction "1_1") (pintype "passive"))
      (node (ref "U1") (pin "P2") (pinfunction "IO_L20P_T3_34_P2") (pintype "bidirectional"))
    )
    (net (code "153") (name "FPGA_QSPI_HD") (class "Default")
      (node (ref "R142") (pin "1") (pinfunction "1_1") (pintype "passive"))
      (node (ref "U1") (pin "D13") (pinfunction "IO_L8N_T1_D12_14_D13") (pintype "bidirectional"))
    )
    (net (code "154") (name "FPGA_QSPI_Q") (class "Default")
      (node (ref "R140") (pin "1") (pinfunction "1_1") (pintype "passive"))
      (node (ref "U1") (pin "L14") (pinfunction "IO_L15N_T2_DQS_DOUT_CSO_B_14_L14") (pintype "bidirectional"))
    )
    (net (code "155") (name "FPGA_QSPI_WP") (class "Default")
      (node (ref "R143") (pin "1") (pinfunction "1_1") (pintype "passive"))
      (node (ref "U1") (pin "J13") (pinfunction "IO_L18P_T2_D28_14_J13") (pintype "bidirectional"))
    )
    (net (code "156") (name "FPGA_RGB") (class "Default")
      (node (ref "LED1") (pin "3") (pinfunction "DIN_3") (pintype "bidirectional"))
      (node (ref "U1") (pin "N11") (pinfunction "IO_L23N_T3_D18_14_N11") (pintype "bidirectional"))
    )
    (net (code "157") (name "FPGA_RST") (class "Default")
      (node (ref "C95") (pin "1") (pinfunction "1_1") (pintype "passive"))
      (node (ref "FPGA_RST") (pin "1") (pinfunction "A0_1") (pintype "bidirectional"))
      (node (ref "FPGA_RST") (pin "2") (pinfunction "A1_2") (pintype "bidirectional"))
      (node (ref "R101") (pin "2") (pinfunction "2_2") (pintype "passive"))
      (node (ref "U1") (pin "D14") (pinfunction "IO_L11P_T1_SRCC_14_D14") (pintype "bidirectional"))
    )
    (net (code "158") (name "FPGA_TCK") (class "Default")
      (node (ref "J8") (pin "4") (pinfunction "4_4") (pintype "bidirectional"))
      (node (ref "U1") (pin "A7") (pinfunction "TCK_0_A7") (pintype "bidirectional"))
    )
    (net (code "159") (name "FPGA_TDI") (class "Default")
      (node (ref "J8") (pin "6") (pinfunction "6_6") (pintype "bidirectional"))
      (node (ref "U1") (pin "P7") (pinfunction "TDI_0_P7") (pintype "bidirectional"))
    )
    (net (code "160") (name "FPGA_TDO") (class "Default")
      (node (ref "J8") (pin "5") (pinfunction "5_5") (pintype "bidirectional"))
      (node (ref "U1") (pin "P6") (pinfunction "TDO_0_P6") (pintype "bidirectional"))
    )
    (net (code "161") (name "FPGA_TMS") (class "Default")
      (node (ref "J8") (pin "3") (pinfunction "3_3") (pintype "bidirectional"))
      (node (ref "U1") (pin "M6") (pinfunction "TMS_0_M6") (pintype "bidirectional"))
    )
    (net (code "162") (name "GND") (class "Default")
      (node (ref "ANT1") (pin "2") (pinfunction "GND1_2") (pintype "bidirectional"))
      (node (ref "ANT1") (pin "3") (pinfunction "GND2_3") (pintype "bidirectional"))
      (node (ref "BOOT") (pin "3") (pinfunction "B0_3") (pintype "bidirectional"))
      (node (ref "BOOT") (pin "4") (pinfunction "B1_4") (pintype "bidirectional"))
      (node (ref "BUTTON1") (pin "3") (pinfunction "B0_3") (pintype "bidirectional"))
      (node (ref "BUTTON1") (pin "4") (pinfunction "B1_4") (pintype "bidirectional"))
      (node (ref "BUTTON2") (pin "3") (pinfunction "B0_3") (pintype "bidirectional"))
      (node (ref "BUTTON2") (pin "4") (pinfunction "B1_4") (pintype "bidirectional"))
      (node (ref "C1") (pin "1") (pinfunction "1_1") (pintype "passive"))
      (node (ref "C10") (pin "2") (pinfunction "2_2") (pintype "passive"))
      (node (ref "C100") (pin "2") (pinfunction "2_2") (pintype "passive"))
      (node (ref "C101") (pin "1") (pinfunction "1_1") (pintype "passive"))
      (node (ref "C102") (pin "2") (pinfunction "2_2") (pintype "passive"))
      (node (ref "C103") (pin "1") (pinfunction "1_1") (pintype "passive"))
      (node (ref "C104") (pin "2") (pinfunction "2_2") (pintype "passive"))
      (node (ref "C105") (pin "2") (pinfunction "2_2") (pintype "passive"))
      (node (ref "C106") (pin "1") (pinfunction "1_1") (pintype "passive"))
      (node (ref "C11") (pin "2") (pinfunction "2_2") (pintype "passive"))
      (node (ref "C12") (pin "2") (pinfunction "2_2") (pintype "passive"))
      (node (ref "C13") (pin "1") (pinfunction "1_1") (pintype "passive"))
      (node (ref "C14") (pin "1") (pinfunction "1_1") (pintype "passive"))
      (node (ref "C15") (pin "1") (pinfunction "1_1") (pintype "passive"))
      (node (ref "C16") (pin "1") (pinfunction "1_1") (pintype "passive"))
      (node (ref "C17") (pin "1") (pinfunction "1_1") (pintype "passive"))
      (node (ref "C18") (pin "1") (pinfunction "1_1") (pintype "passive"))
      (node (ref "C2") (pin "1") (pinfunction "1_1") (pintype "passive"))
      (node (ref "C21") (pin "2") (pinfunction "2_2") (pintype "passive"))
      (node (ref "C22") (pin "2") (pinfunction "2_2") (pintype "passive"))
      (node (ref "C23") (pin "2") (pinfunction "2_2") (pintype "passive"))
      (node (ref "C24") (pin "2") (pinfunction "2_2") (pintype "passive"))
      (node (ref "C25") (pin "2") (pinfunction "2_2") (pintype "passive"))
      (node (ref "C26") (pin "2") (pinfunction "2_2") (pintype "passive"))
      (node (ref "C27") (pin "2") (pinfunction "2_2") (pintype "passive"))
      (node (ref "C28") (pin "2") (pinfunction "2_2") (pintype "passive"))
      (node (ref "C29") (pin "2") (pinfunction "2_2") (pintype "passive"))
      (node (ref "C3") (pin "1") (pinfunction "1_1") (pintype "passive"))
      (node (ref "C30") (pin "2") (pinfunction "2_2") (pintype "passive"))
      (node (ref "C31") (pin "2") (pinfunction "2_2") (pintype "passive"))
      (node (ref "C32") (pin "2") (pinfunction "2_2") (pintype "passive"))
      (node (ref "C33") (pin "2") (pinfunction "2_2") (pintype "passive"))
      (node (ref "C34") (pin "2") (pinfunction "2_2") (pintype "passive"))
      (node (ref "C35") (pin "2") (pinfunction "2_2") (pintype "passive"))
      (node (ref "C36") (pin "2") (pinfunction "2_2") (pintype "passive"))
      (node (ref "C37") (pin "2") (pinfunction "2_2") (pintype "passive"))
      (node (ref "C38") (pin "2") (pinfunction "2_2") (pintype "passive"))
      (node (ref "C39") (pin "2") (pinfunction "2_2") (pintype "passive"))
      (node (ref "C4") (pin "2") (pinfunction "2_2") (pintype "passive"))
      (node (ref "C40") (pin "2") (pinfunction "2_2") (pintype "passive"))
      (node (ref "C41") (pin "2") (pinfunction "2_2") (pintype "passive"))
      (node (ref "C42") (pin "2") (pinfunction "2_2") (pintype "passive"))
      (node (ref "C43") (pin "2") (pinfunction "2_2") (pintype "passive"))
      (node (ref "C44") (pin "2") (pinfunction "2_2") (pintype "passive"))
      (node (ref "C45") (pin "2") (pinfunction "2_2") (pintype "passive"))
      (node (ref "C46") (pin "2") (pinfunction "2_2") (pintype "passive"))
      (node (ref "C47") (pin "1") (pinfunction "1_1") (pintype "passive"))
      (node (ref "C48") (pin "1") (pinfunction "1_1") (pintype "passive"))
      (node (ref "C49") (pin "1") (pinfunction "1_1") (pintype "passive"))
      (node (ref "C5") (pin "2") (pinfunction "2_2") (pintype "passive"))
      (node (ref "C50") (pin "2") (pinfunction "2_2") (pintype "passive"))
      (node (ref "C51") (pin "2") (pinfunction "2_2") (pintype "passive"))
      (node (ref "C52") (pin "1") (pinfunction "1_1") (pintype "passive"))
      (node (ref "C54") (pin "1") (pinfunction "1_1") (pintype "passive"))
      (node (ref "C55") (pin "1") (pinfunction "1_1") (pintype "passive"))
      (node (ref "C56") (pin "1") (pinfunction "1_1") (pintype "passive"))
      (node (ref "C57") (pin "1") (pinfunction "1_1") (pintype "passive"))
      (node (ref "C58") (pin "1") (pinfunction "1_1") (pintype "passive"))
      (node (ref "C59") (pin "2") (pinfunction "2_2") (pintype "passive"))
      (node (ref "C6") (pin "2") (pinfunction "2_2") (pintype "passive"))
      (node (ref "C60") (pin "2") (pinfunction "2_2") (pintype "passive"))
      (node (ref "C61") (pin "1") (pinfunction "1_1") (pintype "passive"))
      (node (ref "C62") (pin "1") (pinfunction "1_1") (pintype "passive"))
      (node (ref "C63") (pin "2") (pinfunction "2_2") (pintype "passive"))
      (node (ref "C64") (pin "2") (pinfunction "2_2") (pintype "passive"))
      (node (ref "C65") (pin "2") (pinfunction "2_2") (pintype "passive"))
      (node (ref "C66") (pin "2") (pinfunction "2_2") (pintype "passive"))
      (node (ref "C67") (pin "2") (pinfunction "2_2") (pintype "passive"))
      (node (ref "C68") (pin "2") (pinfunction "2_2") (pintype "passive"))
      (node (ref "C69") (pin "1") (pinfunction "1_1") (pintype "passive"))
      (node (ref "C7") (pin "2") (pinfunction "2_2") (pintype "passive"))
      (node (ref "C70") (pin "1") (pinfunction "1_1") (pintype "passive"))
      (node (ref "C71") (pin "2") (pinfunction "2_2") (pintype "passive"))
      (node (ref "C72") (pin "2") (pinfunction "2_2") (pintype "passive"))
      (node (ref "C73") (pin "2") (pinfunction "2_2") (pintype "passive"))
      (node (ref "C74") (pin "1") (pinfunction "1_1") (pintype "passive"))
      (node (ref "C75") (pin "2") (pinfunction "2_2") (pintype "passive"))
      (node (ref "C76") (pin "1") (pinfunction "1_1") (pintype "passive"))
      (node (ref "C77") (pin "1") (pinfunction "1_1") (pintype "passive"))
      (node (ref "C78") (pin "2") (pinfunction "2_2") (pintype "passive"))
      (node (ref "C79") (pin "2") (pinfunction "2_2") (pintype "passive"))
      (node (ref "C8") (pin "2") (pinfunction "2_2") (pintype "passive"))
      (node (ref "C80") (pin "2") (pinfunction "2_2") (pintype "passive"))
      (node (ref "C81") (pin "2") (pinfunction "2_2") (pintype "passive"))
      (node (ref "C82") (pin "1") (pinfunction "1_1") (pintype "passive"))
      (node (ref "C83") (pin "2") (pinfunction "2_2") (pintype "passive"))
      (node (ref "C84") (pin "2") (pinfunction "2_2") (pintype "passive"))
      (node (ref "C85") (pin "1") (pinfunction "1_1") (pintype "passive"))
      (node (ref "C86") (pin "2") (pinfunction "2_2") (pintype "passive"))
      (node (ref "C87") (pin "2") (pinfunction "2_2") (pintype "passive"))
      (node (ref "C9") (pin "2") (pinfunction "2_2") (pintype "passive"))
      (node (ref "C91") (pin "1") (pinfunction "1_1") (pintype "passive"))
      (node (ref "C92") (pin "1") (pinfunction "1_1") (pintype "passive"))
      (node (ref "C94") (pin "1") (pinfunction "1_1") (pintype "passive"))
      (node (ref "C95") (pin "2") (pinfunction "2_2") (pintype "passive"))
      (node (ref "C96") (pin "2") (pinfunction "2_2") (pintype "passive"))
      (node (ref "C97") (pin "1") (pinfunction "1_1") (pintype "passive"))
      (node (ref "C98") (pin "2") (pinfunction "2_2") (pintype "passive"))
      (node (ref "C99") (pin "2") (pinfunction "2_2") (pintype "passive"))
      (node (ref "D1") (pin "1") (pinfunction "1_1") (pintype "bidirectional"))
      (node (ref "D11") (pin "1") (pinfunction "1_1") (pintype "bidirectional"))
      (node (ref "D12") (pin "1") (pinfunction "1_1") (pintype "bidirectional"))
      (node (ref "D13") (pin "1") (pinfunction "1_1") (pintype "bidirectional"))
      (node (ref "D14") (pin "1") (pinfunction "1_1") (pintype "bidirectional"))
      (node (ref "D15") (pin "1") (pinfunction "1_1") (pintype "bidirectional"))
      (node (ref "D16") (pin "1") (pinfunction "1_1") (pintype "bidirectional"))
      (node (ref "D17") (pin "1") (pinfunction "1_1") (pintype "bidirectional"))
      (node (ref "D2") (pin "1") (pinfunction "1_1") (pintype "bidirectional"))
      (node (ref "D21") (pin "2") (pinfunction "2_2") (pintype "bidirectional"))
      (node (ref "D3") (pin "-") (pinfunction "-_-") (pintype "passive"))
      (node (ref "D5") (pin "1") (pinfunction "1_1") (pintype "bidirectional"))
      (node (ref "D6") (pin "1") (pinfunction "1_1") (pintype "bidirectional"))
      (node (ref "D7") (pin "1") (pinfunction "1_1") (pintype "bidirectional"))
      (node (ref "D8") (pin "1") (pinfunction "1_1") (pintype "bidirectional"))
      (node (ref "D9") (pin "1") (pinfunction "1_1") (pintype "bidirectional"))
      (node (ref "FB7") (pin "1") (pinfunction "1_1") (pintype "bidirectional"))
      (node (ref "FB8") (pin "2") (pinfunction "2_2") (pintype "bidirectional"))
      (node (ref "FB9") (pin "2") (pinfunction "2_2") (pintype "bidirectional"))
      (node (ref "FPGA_RST") (pin "3") (pinfunction "B0_3") (pintype "bidirectional"))
      (node (ref "FPGA_RST") (pin "4") (pinfunction "B1_4") (pintype "bidirectional"))
      (node (ref "J1") (pin "2") (pinfunction "P$2_2") (pintype "bidirectional"))
      (node (ref "J1") (pin "3") (pinfunction "P$3_3") (pintype "bidirectional"))
      (node (ref "J2") (pin "4") (pinfunction "4_4") (pintype "bidirectional"))
      (node (ref "J3") (pin "6") (pinfunction "VSS_6") (pintype "bidirectional"))
      (node (ref "J3") (pin "9") (pinfunction "GND_9") (pintype "bidirectional"))
      (node (ref "J4") (pin "4") (pinfunction "4_4") (pintype "bidirectional"))
      (node (ref "J5") (pin "4") (pinfunction "4_4") (pintype "bidirectional"))
      (node (ref "J6") (pin "1") (pinfunction "1_1") (pintype "bidirectional"))
      (node (ref "J6") (pin "10") (pinfunction "10_10") (pintype "bidirectional"))
      (node (ref "J6") (pin "16") (pinfunction "16_16") (pintype "bidirectional"))
      (node (ref "J6") (pin "19") (pinfunction "19_19") (pintype "bidirectional"))
      (node (ref "J6") (pin "22") (pinfunction "22_22") (pintype "bidirectional"))
      (node (ref "J6") (pin "25") (pinfunction "25_25") (pintype "bidirectional"))
      (node (ref "J6") (pin "4") (pinfunction "4_4") (pintype "bidirectional"))
      (node (ref "J6") (pin "7") (pinfunction "7_7") (pintype "bidirectional"))
      (node (ref "J8") (pin "2") (pinfunction "2_2") (pintype "bidirectional"))
      (node (ref "J9") (pin "1") (pinfunction "TMDS_DATA2_SHIELD_1") (pintype "bidirectional"))
      (node (ref "J9") (pin "10") (pinfunction "TMDS_CLOCK_SHIELD_10") (pintype "bidirectional"))
      (node (ref "J9") (pin "13") (pinfunction "DDC/CEC_GROUND_13") (pintype "bidirectional"))
      (node (ref "J9") (pin "4") (pinfunction "TMDS_DATA1_SHIELD_4") (pintype "bidirectional"))
      (node (ref "J9") (pin "7") (pinfunction "TMDS_DATA0_SHIELD_7") (pintype "bidirectional"))
      (node (ref "L1") (pin "1") (pinfunction "1_1") (pintype "passive"))
      (node (ref "L2") (pin "1") (pinfunction "1_1") (pintype "passive"))
      (node (ref "LED1") (pin "2") (pinfunction "VSS_2") (pintype "bidirectional"))
      (node (ref "LED2") (pin "2") (pinfunction "VSS_2") (pintype "bidirectional"))
      (node (ref "Q1") (pin "2") (pinfunction "S_2") (pintype "passive"))
      (node (ref "R11") (pin "2") (pinfunction "2_2") (pintype "passive"))
      (node (ref "R118") (pin "2") (pinfunction "2_2") (pintype "passive"))
      (node (ref "R120") (pin "2") (pinfunction "2_2") (pintype "passive"))
      (node (ref "R122") (pin "2") (pinfunction "2_2") (pintype "passive"))
      (node (ref "R124") (pin "2") (pinfunction "2_2") (pintype "passive"))
      (node (ref "R126") (pin "1") (pinfunction "1_1") (pintype "passive"))
      (node (ref "R130") (pin "2") (pinfunction "2_2") (pintype "passive"))
      (node (ref "R133") (pin "2") (pinfunction "2_2") (pintype "passive"))
      (node (ref "R145") (pin "1") (pinfunction "1_1") (pintype "passive"))
      (node (ref "R149") (pin "1") (pinfunction "1_1") (pintype "passive"))
      (node (ref "R15") (pin "2") (pinfunction "2_2") (pintype "passive"))
      (node (ref "R153") (pin "2") (pinfunction "2_2") (pintype "passive"))
      (node (ref "R155") (pin "2") (pinfunction "2_2") (pintype "passive"))
      (node (ref "R157") (pin "2") (pinfunction "2_2") (pintype "passive"))
      (node (ref "R159") (pin "2") (pinfunction "2_2") (pintype "passive"))
      (node (ref "R161") (pin "2") (pinfunction "2_2") (pintype "passive"))
      (node (ref "R163") (pin "2") (pinfunction "2_2") (pintype "passive"))
      (node (ref "R165") (pin "2") (pinfunction "2_2") (pintype "passive"))
      (node (ref "R167") (pin "2") (pinfunction "2_2") (pintype "passive"))
      (node (ref "R173") (pin "2") (pinfunction "2_2") (pintype "passive"))
      (node (ref "R175") (pin "2") (pinfunction "2_2") (pintype "passive"))
      (node (ref "R177") (pin "2") (pinfunction "2_2") (pintype "passive"))
      (node (ref "R179") (pin "2") (pinfunction "2_2") (pintype "passive"))
      (node (ref "R184") (pin "1") (pinfunction "1_1") (pintype "passive"))
      (node (ref "R185") (pin "1") (pinfunction "1_1") (pintype "passive"))
      (node (ref "R19") (pin "1") (pinfunction "1_1") (pintype "passive"))
      (node (ref "R20") (pin "1") (pinfunction "1_1") (pintype "passive"))
      (node (ref "R22") (pin "2") (pinfunction "2_2") (pintype "passive"))
      (node (ref "R33") (pin "2") (pinfunction "2_2") (pintype "passive"))
      (node (ref "R35") (pin "2") (pinfunction "2_2") (pintype "passive"))
      (node (ref "R38") (pin "2") (pinfunction "2_2") (pintype "passive"))
      (node (ref "R44") (pin "1") (pinfunction "1_1") (pintype "passive"))
      (node (ref "R45") (pin "1") (pinfunction "1_1") (pintype "passive"))
      (node (ref "R46") (pin "1") (pinfunction "1_1") (pintype "passive"))
      (node (ref "R59") (pin "2") (pinfunction "2_2") (pintype "passive"))
      (node (ref "R6") (pin "1") (pinfunction "1_1") (pintype "passive"))
      (node (ref "R60") (pin "2") (pinfunction "2_2") (pintype "passive"))
      (node (ref "R63") (pin "2") (pinfunction "2_2") (pintype "passive"))
      (node (ref "R64") (pin "2") (pinfunction "2_2") (pintype "passive"))
      (node (ref "R65") (pin "2") (pinfunction "2_2") (pintype "passive"))
      (node (ref "R67") (pin "1") (pinfunction "1_1") (pintype "passive"))
      (node (ref "R7") (pin "2") (pinfunction "2_2") (pintype "passive"))
      (node (ref "R71") (pin "1") (pinfunction "1_1") (pintype "passive"))
      (node (ref "RST") (pin "3") (pinfunction "B0_3") (pintype "bidirectional"))
      (node (ref "RST") (pin "4") (pinfunction "B1_4") (pintype "bidirectional"))
      (node (ref "SW2") (pin "2") (pinfunction "GND_2") (pintype "bidirectional"))
      (node (ref "U1") (pin "A1") (pinfunction "GND_A1") (pintype "bidirectional"))
      (node (ref "U1") (pin "A11") (pinfunction "GND_A11") (pintype "bidirectional"))
      (node (ref "U1") (pin "A14") (pinfunction "GND_A14") (pintype "bidirectional"))
      (node (ref "U1") (pin "A6") (pinfunction "GND_A6") (pintype "bidirectional"))
      (node (ref "U1") (pin "A9") (pinfunction "GND_A9") (pintype "bidirectional"))
      (node (ref "U1") (pin "B4") (pinfunction "GND_B4") (pintype "bidirectional"))
      (node (ref "U1") (pin "B7") (pinfunction "GND_B7") (pintype "bidirectional"))
      (node (ref "U1") (pin "B8") (pinfunction "NC_B8") (pintype "bidirectional"))
      (node (ref "U1") (pin "B9") (pinfunction "GND_B9") (pintype "bidirectional"))
      (node (ref "U1") (pin "C13") (pinfunction "GND_C13") (pintype "bidirectional"))
      (node (ref "U1") (pin "C2") (pinfunction "GND_C2") (pintype "bidirectional"))
      (node (ref "U1") (pin "C6") (pinfunction "GND_C6") (pintype "bidirectional"))
      (node (ref "U1") (pin "C7") (pinfunction "GND_C7") (pintype "bidirectional"))
      (node (ref "U1") (pin "C8") (pinfunction "GND_C8") (pintype "bidirectional"))
      (node (ref "U1") (pin "C9") (pinfunction "GND_C9") (pintype "bidirectional"))
      (node (ref "U1") (pin "D11") (pinfunction "GND_D11") (pintype "bidirectional"))
      (node (ref "U1") (pin "D5") (pinfunction "GND_D5") (pintype "bidirectional"))
      (node (ref "U1") (pin "D7") (pinfunction "GND_D7") (pintype "bidirectional"))
      (node (ref "U1") (pin "D9") (pinfunction "GND_D9") (pintype "bidirectional"))
      (node (ref "U1") (pin "E1") (pinfunction "GND_E1") (pintype "bidirectional"))
      (node (ref "U1") (pin "E10") (pinfunction "GND_E10") (pintype "bidirectional"))
      (node (ref "U1") (pin "E14") (pinfunction "GND_E14") (pintype "bidirectional"))
      (node (ref "U1") (pin "E3") (pinfunction "GND_E3") (pintype "bidirectional"))
      (node (ref "U1") (pin "E6") (pinfunction "GND_E6") (pintype "bidirectional"))
      (node (ref "U1") (pin "E8") (pinfunction "GND_E8") (pintype "bidirectional"))
      (node (ref "U1") (pin "F5") (pinfunction "GND_F5") (pintype "bidirectional"))
      (node (ref "U1") (pin "F7") (pinfunction "NC_F7") (pintype "bidirectional"))
      (node (ref "U1") (pin "F9") (pinfunction "GND_F9") (pintype "bidirectional"))
      (node (ref "U1") (pin "G10") (pinfunction "GND_G10") (pintype "bidirectional"))
      (node (ref "U1") (pin "G12") (pinfunction "GND_G12") (pintype "bidirectional"))
      (node (ref "U1") (pin "G3") (pinfunction "GND_G3") (pintype "bidirectional"))
      (node (ref "U1") (pin "G6") (pinfunction "GND_G6") (pintype "bidirectional"))
      (node (ref "U1") (pin "G7") (pinfunction "NC_G7") (pintype "bidirectional"))
      (node (ref "U1") (pin "G8") (pinfunction "NC_G8") (pintype "bidirectional"))
      (node (ref "U1") (pin "H5") (pinfunction "GND_H5") (pintype "bidirectional"))
      (node (ref "U1") (pin "H7") (pinfunction "NC_H7") (pintype "bidirectional"))
      (node (ref "U1") (pin "H8") (pinfunction "NC_H8") (pintype "bidirectional"))
      (node (ref "U1") (pin "H9") (pinfunction "GND_H9") (pintype "bidirectional"))
      (node (ref "U1") (pin "J10") (pinfunction "GND_J10") (pintype "bidirectional"))
      (node (ref "U1") (pin "J6") (pinfunction "GND_J6") (pintype "bidirectional"))
      (node (ref "U1") (pin "J7") (pinfunction "DXN_0_J7") (pintype "bidirectional"))
      (node (ref "U1") (pin "J8") (pinfunction "DXP_0_J8") (pintype "bidirectional"))
      (node (ref "U1") (pin "K1") (pinfunction "GND_K1") (pintype "bidirectional"))
      (node (ref "U1") (pin "K14") (pinfunction "GND_K14") (pintype "bidirectional"))
      (node (ref "U1") (pin "K5") (pinfunction "GND_K5") (pintype "bidirectional"))
      (node (ref "U1") (pin "K7") (pinfunction "GND_K7") (pintype "bidirectional"))
      (node (ref "U1") (pin "K9") (pinfunction "GND_K9") (pintype "bidirectional"))
      (node (ref "U1") (pin "L10") (pinfunction "GND_L10") (pintype "bidirectional"))
      (node (ref "U1") (pin "L11") (pinfunction "GND_L11") (pintype "bidirectional"))
      (node (ref "U1") (pin "L4") (pinfunction "GND_L4") (pintype "bidirectional"))
      (node (ref "U1") (pin "L6") (pinfunction "GND_L6") (pintype "bidirectional"))
      (node (ref "U1") (pin "L8") (pinfunction "GND_L8") (pintype "bidirectional"))
      (node (ref "U1") (pin "N12") (pinfunction "GND_N12") (pintype "bidirectional"))
      (node (ref "U1") (pin "N3") (pinfunction "GND_N3") (pintype "bidirectional"))
      (node (ref "U1") (pin "N5") (pinfunction "GND_N5") (pintype "bidirectional"))
      (node (ref "U1") (pin "N9") (pinfunction "GND_N9") (pintype "bidirectional"))
      (node (ref "U1") (pin "P1") (pinfunction "GND_P1") (pintype "bidirectional"))
      (node (ref "U1") (pin "P14") (pinfunction "GND_P14") (pintype "bidirectional"))
      (node (ref "U10") (pin "15") (pinfunction "GND_15") (pintype "bidirectional"))
      (node (ref "U10") (pin "26") (pinfunction "GND_26") (pintype "bidirectional"))
      (node (ref "U10") (pin "27") (pinfunction "GND_27") (pintype "bidirectional"))
      (node (ref "U11") (pin "15") (pinfunction "PGND_15") (pintype "bidirectional"))
      (node (ref "U11") (pin "16") (pinfunction "PGND_16") (pintype "bidirectional"))
      (node (ref "U11") (pin "7") (pinfunction "FSW_7") (pintype "bidirectional"))
      (node (ref "U11") (pin "8") (pinfunction "DEF_8") (pintype "bidirectional"))
      (node (ref "U11") (pin "PAD") (pinfunction "PAD_PAD") (pintype "bidirectional"))
      (node (ref "U12") (pin "2") (pinfunction "SDX_2") (pintype "bidirectional"))
      (node (ref "U12") (pin "3") (pinfunction "SCX_3") (pintype "bidirectional"))
      (node (ref "U12") (pin "6") (pinfunction "GND_6") (pintype "bidirectional"))
      (node (ref "U12") (pin "7") (pinfunction "GND_7") (pintype "bidirectional"))
      (node (ref "U13") (pin "1") (pinfunction "GND_1") (pintype "bidirectional"))
      (node (ref "U15") (pin "3") (pinfunction "3_3") (pintype "bidirectional"))
      (node (ref "U15") (pin "8") (pinfunction "8_8") (pintype "bidirectional"))
      (node (ref "U16") (pin "3") (pinfunction "3_3") (pintype "bidirectional"))
      (node (ref "U16") (pin "8") (pinfunction "8_8") (pintype "bidirectional"))
      (node (ref "U17") (pin "7") (pinfunction "GND_7") (pintype "bidirectional"))
      (node (ref "U18") (pin "7") (pinfunction "GND_7") (pintype "bidirectional"))
      (node (ref "U2") (pin "PAD") (pinfunction "GND_PAD") (pintype "bidirectional"))
      (node (ref "U3") (pin "4") (pinfunction "GND_4") (pintype "bidirectional"))
      (node (ref "U4") (pin "2") (pinfunction "DVSS_2") (pintype "bidirectional"))
      (node (ref "U4") (pin "23") (pinfunction "VRB_23") (pintype "bidirectional"))
      (node (ref "U4") (pin "24") (pinfunction "DVSS_24") (pintype "bidirectional"))
      (node (ref "U5") (pin "3") (pinfunction "GND_3") (pintype "bidirectional"))
      (node (ref "U5") (pin "PAD") (pinfunction "PAD_PAD") (pintype "bidirectional"))
      (node (ref "U7") (pin "1") (pinfunction "GND_1") (pintype "bidirectional"))
      (node (ref "U8") (pin "2") (pinfunction "VSS_2") (pintype "bidirectional"))
      (node (ref "U9") (pin "2") (pinfunction "VSS_2") (pintype "bidirectional"))
      (node (ref "USB2") (pin "A1_B12") (pinfunction "A1/B12/GND_A1_B12") (pintype "bidirectional"))
      (node (ref "USB2") (pin "B1_A12") (pinfunction "B1/A12/GND_B1_A12") (pintype "bidirectional"))
      (node (ref "X2") (pin "2") (pinfunction "GND_2") (pintype "bidirectional"))
      (node (ref "X3") (pin "2") (pinfunction "GND_2") (pintype "bidirectional"))
      (node (ref "X3") (pin "4") (pinfunction "GND_4") (pintype "bidirectional"))
    )
    (net (code "163") (name "GND_SIGNAL") (class "Default")
      (node (ref "C53") (pin "1") (pinfunction "1_1") (pintype "passive"))
      (node (ref "R11") (pin "1") (pinfunction "1_1") (pintype "passive"))
      (node (ref "R135") (pin "2") (pinfunction "2_2") (pintype "passive"))
      (node (ref "U11") (pin "6") (pinfunction "AGND_6") (pintype "bidirectional"))
    )
    (net (code "164") (name "GPIO0") (class "Default")
      (node (ref "BOOT") (pin "1") (pinfunction "A0_1") (pintype "bidirectional"))
      (node (ref "BOOT") (pin "2") (pinfunction "A1_2") (pintype "bidirectional"))
      (node (ref "Q5") (pin "3") (pinfunction "C_3") (pintype "passive"))
      (node (ref "R4") (pin "1") (pinfunction "1_1") (pintype "passive"))
      (node (ref "U2") (pin "23") (pinfunction "GPIO0_23") (pintype "bidirectional"))
    )
    (net (code "165") (name "HDMI_5V") (class "Default")
      (node (ref "C18") (pin "2") (pinfunction "2_2") (pintype "passive"))
      (node (ref "C94") (pin "2") (pinfunction "2_2") (pintype "passive"))
      (node (ref "D4") (pin "-") (pinfunction "-_-") (pintype "passive"))
      (node (ref "D6") (pin "2") (pinfunction "2_2") (pintype "bidirectional"))
      (node (ref "J9") (pin "18") (pinfunction "+5V_POWER_18") (pintype "bidirectional"))
      (node (ref "R39") (pin "1") (pinfunction "1_1") (pintype "passive"))
      (node (ref "R40") (pin "1") (pinfunction "1_1") (pintype "passive"))
      (node (ref "R41") (pin "1") (pinfunction "1_1") (pintype "passive"))
    )
    (net (code "166") (name "HDMI_CEC") (class "Default")
      (node (ref "D9") (pin "2") (pinfunction "2_2") (pintype "bidirectional"))
      (node (ref "J9") (pin "14") (pinfunction "CEC_14") (pintype "bidirectional"))
      (node (ref "R93") (pin "2") (pinfunction "2_2") (pintype "passive"))
      (node (ref "U1") (pin "E4") (pinfunction "IO_L7P_T1_34_E4") (pintype "bidirectional"))
    )
    (net (code "167") (name "HDMI_DDCSCL") (class "Default")
      (node (ref "D8") (pin "2") (pinfunction "2_2") (pintype "bidirectional"))
      (node (ref "J9") (pin "15") (pinfunction "SCL_15") (pintype "bidirectional"))
      (node (ref "R40") (pin "2") (pinfunction "2_2") (pintype "passive"))
      (node (ref "U13") (pin "6") (pinfunction "SCL2_6") (pintype "bidirectional"))
    )
    (net (code "168") (name "HDMI_DDCSDA") (class "Default")
      (node (ref "D7") (pin "2") (pinfunction "2_2") (pintype "bidirectional"))
      (node (ref "J9") (pin "16") (pinfunction "SDA_16") (pintype "bidirectional"))
      (node (ref "R41") (pin "2") (pinfunction "2_2") (pintype "passive"))
      (node (ref "U13") (pin "5") (pinfunction "SDA2_5") (pintype "bidirectional"))
    )
    (net (code "169") (name "HDMI_HPD") (class "Default")
      (node (ref "D5") (pin "2") (pinfunction "2_2") (pintype "bidirectional"))
      (node (ref "J9") (pin "19") (pinfunction "HOT_PLUG_DETECT_19") (pintype "bidirectional"))
      (node (ref "R67") (pin "2") (pinfunction "2_2") (pintype "passive"))
      (node (ref "R70") (pin "1") (pinfunction "1_1") (pintype "passive"))
    )
    (net (code "170") (name "HDMI_HPD_DET") (class "Default")
      (node (ref "Q1") (pin "3") (pinfunction "D_3") (pintype "passive"))
      (node (ref "R21") (pin "1") (pinfunction "1_1") (pintype "passive"))
      (node (ref "U1") (pin "D4") (pinfunction "IO_L7N_T1_34_D4") (pintype "bidirectional"))
    )
    (net (code "171") (name "HDMI_TCK+") (class "Default")
      (node (ref "J9") (pin "11") (pinfunction "TMDS_CLOCK+_11") (pintype "bidirectional"))
      (node (ref "L7") (pin "1") (pinfunction "1_1") (pintype "bidirectional"))
      (node (ref "R90") (pin "1") (pinfunction "1_1") (pintype "passive"))
      (node (ref "U16") (pin "4") (pinfunction "4_4") (pintype "bidirectional"))
      (node (ref "U16") (pin "7") (pinfunction "7_7") (pintype "bidirectional"))
    )
    (net (code "172") (name "HDMI_TCK-") (class "Default")
      (node (ref "J9") (pin "12") (pinfunction "TMDS_CLOCK-_12") (pintype "bidirectional"))
      (node (ref "L7") (pin "2") (pinfunction "4_2") (pintype "bidirectional"))
      (node (ref "R91") (pin "1") (pinfunction "1_1") (pintype "passive"))
      (node (ref "U16") (pin "5") (pinfunction "5_5") (pintype "bidirectional"))
      (node (ref "U16") (pin "6") (pinfunction "6_6") (pintype "bidirectional"))
    )
    (net (code "173") (name "HDMI_TD0+") (class "Default")
      (node (ref "J9") (pin "8") (pinfunction "TMDS_DATA0+_8") (pintype "bidirectional"))
      (node (ref "L5") (pin "1") (pinfunction "1_1") (pintype "bidirectional"))
      (node (ref "R88") (pin "1") (pinfunction "1_1") (pintype "passive"))
      (node (ref "U16") (pin "1") (pinfunction "1_1") (pintype "bidirectional"))
      (node (ref "U16") (pin "10") (pinfunction "10_10") (pintype "bidirectional"))
    )
    (net (code "174") (name "HDMI_TD0-") (class "Default")
      (node (ref "J9") (pin "9") (pinfunction "TMDS_DATA0-_9") (pintype "bidirectional"))
      (node (ref "L5") (pin "2") (pinfunction "4_2") (pintype "bidirectional"))
      (node (ref "R89") (pin "1") (pinfunction "1_1") (pintype "passive"))
      (node (ref "U16") (pin "2") (pinfunction "2_2") (pintype "bidirectional"))
      (node (ref "U16") (pin "9") (pinfunction "9_9") (pintype "bidirectional"))
    )
    (net (code "175") (name "HDMI_TD1+") (class "Default")
      (node (ref "J9") (pin "5") (pinfunction "TMDS_DATA1+_5") (pintype "bidirectional"))
      (node (ref "L4") (pin "1") (pinfunction "1_1") (pintype "bidirectional"))
      (node (ref "R86") (pin "1") (pinfunction "1_1") (pintype "passive"))
      (node (ref "U15") (pin "4") (pinfunction "4_4") (pintype "bidirectional"))
      (node (ref "U15") (pin "7") (pinfunction "7_7") (pintype "bidirectional"))
    )
    (net (code "176") (name "HDMI_TD1-") (class "Default")
      (node (ref "J9") (pin "6") (pinfunction "TMDS_DATA1-_6") (pintype "bidirectional"))
      (node (ref "L4") (pin "2") (pinfunction "4_2") (pintype "bidirectional"))
      (node (ref "R87") (pin "1") (pinfunction "1_1") (pintype "passive"))
      (node (ref "U15") (pin "5") (pinfunction "5_5") (pintype "bidirectional"))
      (node (ref "U15") (pin "6") (pinfunction "6_6") (pintype "bidirectional"))
    )
    (net (code "177") (name "HDMI_TD2+") (class "Default")
      (node (ref "J9") (pin "2") (pinfunction "TMDS_DATA2+_2") (pintype "bidirectional"))
      (node (ref "L3") (pin "1") (pinfunction "1_1") (pintype "bidirectional"))
      (node (ref "R80") (pin "1") (pinfunction "1_1") (pintype "passive"))
      (node (ref "U15") (pin "1") (pinfunction "1_1") (pintype "bidirectional"))
      (node (ref "U15") (pin "10") (pinfunction "10_10") (pintype "bidirectional"))
    )
    (net (code "178") (name "HDMI_TD2-") (class "Default")
      (node (ref "J9") (pin "3") (pinfunction "TMDS_DATA2-_3") (pintype "bidirectional"))
      (node (ref "L3") (pin "2") (pinfunction "4_2") (pintype "bidirectional"))
      (node (ref "R81") (pin "1") (pinfunction "1_1") (pintype "passive"))
      (node (ref "U15") (pin "2") (pinfunction "2_2") (pintype "bidirectional"))
      (node (ref "U15") (pin "9") (pinfunction "9_9") (pintype "bidirectional"))
    )
    (net (code "179") (name "IMU_AD") (class "Default")
      (node (ref "R114") (pin "1") (pinfunction "1_1") (pintype "passive"))
      (node (ref "U1") (pin "J14") (pinfunction "IO_L18N_T2_D27_14_J14") (pintype "bidirectional"))
      (node (ref "U12") (pin "1") (pinfunction "SDO/SA0_1") (pintype "bidirectional"))
    )
    (net (code "180") (name "IMU_INT2") (class "Default")
      (node (ref "U1") (pin "L12") (pinfunction "IO_L16P_T2_CSI_B_14_L12") (pintype "bidirectional"))
      (node (ref "U12") (pin "9") (pinfunction "INT2_9") (pintype "bidirectional"))
    )
    (net (code "181") (name "Net-(ANT1-D)") (class "Default")
      (node (ref "ANT1") (pin "1") (pinfunction "D_1") (pintype "bidirectional"))
      (node (ref "L2") (pin "2") (pinfunction "2_2") (pintype "passive"))
      (node (ref "R58") (pin "1") (pinfunction "1_1") (pintype "passive"))
    )
    (net (code "182") (name "Net-(C12-Pad1)") (class "Default")
      (node (ref "C12") (pin "1") (pinfunction "1_1") (pintype "passive"))
      (node (ref "J6") (pin "15") (pinfunction "15_15") (pintype "bidirectional"))
      (node (ref "J6") (pin "30") (pinfunction "30_30") (pintype "bidirectional"))
      (node (ref "R37") (pin "1") (pinfunction "1_1") (pintype "passive"))
    )
    (net (code "183") (name "Net-(C26-Pad1)") (class "Default")
      (node (ref "C26") (pin "1") (pinfunction "1_1") (pintype "passive"))
      (node (ref "FB2") (pin "2") (pinfunction "2_2") (pintype "bidirectional"))
      (node (ref "U4") (pin "14") (pinfunction "AVDD_14") (pintype "bidirectional"))
      (node (ref "U4") (pin "15") (pinfunction "AVDD_15") (pintype "bidirectional"))
      (node (ref "U4") (pin "18") (pinfunction "AVDD_18") (pintype "bidirectional"))
    )
    (net (code "184") (name "Net-(D3-Pad+)") (class "Default")
      (node (ref "D3") (pin "+") (pinfunction "+_+") (pintype "passive"))
      (node (ref "R13") (pin "2") (pinfunction "2_2") (pintype "passive"))
    )
    (net (code "185") (name "Net-(D4-Pad+)") (class "Default")
      (node (ref "D4") (pin "+") (pinfunction "+_+") (pintype "passive"))
      (node (ref "F2") (pin "1") (pinfunction "1_1") (pintype "bidirectional"))
    )
    (net (code "186") (name "Net-(D10-Pad-)") (class "Default")
      (node (ref "D10") (pin "-") (pinfunction "-_-") (pintype "passive"))
      (node (ref "R93") (pin "1") (pinfunction "1_1") (pintype "passive"))
    )
    (net (code "187") (name "Net-(D18-Pad-)") (class "Default")
      (node (ref "D18") (pin "-") (pinfunction "-_-") (pintype "passive"))
      (node (ref "R44") (pin "2") (pinfunction "2_2") (pintype "passive"))
    )
    (net (code "188") (name "Net-(D19-Pad-)") (class "Default")
      (node (ref "D19") (pin "-") (pinfunction "-_-") (pintype "passive"))
      (node (ref "R45") (pin "2") (pinfunction "2_2") (pintype "passive"))
    )
    (net (code "189") (name "Net-(D20-Pad-)") (class "Default")
      (node (ref "D20") (pin "-") (pinfunction "-_-") (pintype "passive"))
      (node (ref "R46") (pin "2") (pinfunction "2_2") (pintype "passive"))
    )
    (net (code "190") (name "Net-(FB6-Pad2)") (class "Default")
      (node (ref "FB6") (pin "2") (pinfunction "2_2") (pintype "bidirectional"))
      (node (ref "SW1") (pin "CH1A") (pinfunction "CH1A_CH1A") (pintype "bidirectional"))
      (node (ref "SW1") (pin "CH2A") (pinfunction "CH2A_CH2A") (pintype "bidirectional"))
    )
    (net (code "191") (name "Net-(FB8-Pad1)") (class "Default")
      (node (ref "FB8") (pin "1") (pinfunction "1_1") (pintype "bidirectional"))
      (node (ref "USB2") (pin "S1") (pinfunction "S1_S1") (pintype "bidirectional"))
      (node (ref "USB2") (pin "S2") (pinfunction "S2_S2") (pintype "bidirectional"))
      (node (ref "USB2") (pin "S5") (pinfunction "S1_S5") (pintype "bidirectional"))
      (node (ref "USB2") (pin "S6") (pinfunction "S2_S6") (pintype "bidirectional"))
    )
    (net (code "192") (name "Net-(FB9-Pad1)") (class "Default")
      (node (ref "FB9") (pin "1") (pinfunction "1_1") (pintype "bidirectional"))
      (node (ref "J3") (pin "13") (pinfunction "GND_13") (pintype "bidirectional"))
      (node (ref "J3") (pin "14") (pinfunction "GND_14") (pintype "bidirectional"))
    )
    (net (code "193") (name "Net-(J3-CD)") (class "Default")
      (node (ref "D11") (pin "2") (pinfunction "2_2") (pintype "bidirectional"))
      (node (ref "J3") (pin "10") (pinfunction "CD_10") (pintype "bidirectional"))
      (node (ref "R107") (pin "2") (pinfunction "2_2") (pintype "passive"))
      (node (ref "R85") (pin "1") (pinfunction "1_1") (pintype "passive"))
    )
    (net (code "194") (name "Net-(J3-CLK)") (class "Default")
      (node (ref "C79") (pin "1") (pinfunction "1_1") (pintype "passive"))
      (node (ref "D15") (pin "2") (pinfunction "2_2") (pintype "bidirectional"))
      (node (ref "J3") (pin "5") (pinfunction "CLK_5") (pintype "bidirectional"))
      (node (ref "R111") (pin "2") (pinfunction "2_2") (pintype "passive"))
      (node (ref "R97") (pin "1") (pinfunction "1_1") (pintype "passive"))
    )
    (net (code "195") (name "Net-(J3-CMD)") (class "Default")
      (node (ref "D14") (pin "2") (pinfunction "2_2") (pintype "bidirectional"))
      (node (ref "J3") (pin "3") (pinfunction "CMD_3") (pintype "bidirectional"))
      (node (ref "R110") (pin "2") (pinfunction "2_2") (pintype "passive"))
      (node (ref "R96") (pin "1") (pinfunction "1_1") (pintype "passive"))
    )
    (net (code "196") (name "Net-(J3-DAT0)") (class "Default")
      (node (ref "D16") (pin "2") (pinfunction "2_2") (pintype "bidirectional"))
      (node (ref "J3") (pin "7") (pinfunction "DAT0_7") (pintype "bidirectional"))
      (node (ref "R105") (pin "1") (pinfunction "1_1") (pintype "passive"))
      (node (ref "R112") (pin "2") (pinfunction "2_2") (pintype "passive"))
    )
    (net (code "197") (name "Net-(J3-DAT1)") (class "Default")
      (node (ref "D17") (pin "2") (pinfunction "2_2") (pintype "bidirectional"))
      (node (ref "J3") (pin "8") (pinfunction "DAT1_8") (pintype "bidirectional"))
      (node (ref "R106") (pin "1") (pinfunction "1_1") (pintype "passive"))
      (node (ref "R113") (pin "2") (pinfunction "2_2") (pintype "passive"))
    )
    (net (code "198") (name "Net-(J3-DAT2)") (class "Default")
      (node (ref "D12") (pin "2") (pinfunction "2_2") (pintype "bidirectional"))
      (node (ref "J3") (pin "1") (pinfunction "DAT2_1") (pintype "bidirectional"))
      (node (ref "R108") (pin "2") (pinfunction "2_2") (pintype "passive"))
      (node (ref "R94") (pin "1") (pinfunction "1_1") (pintype "passive"))
    )
    (net (code "199") (name "Net-(J3-DAT3{slash}CD)") (class "Default")
      (node (ref "D13") (pin "2") (pinfunction "2_2") (pintype "bidirectional"))
      (node (ref "J3") (pin "2") (pinfunction "DAT3/CD_2") (pintype "bidirectional"))
      (node (ref "R109") (pin "2") (pinfunction "2_2") (pintype "passive"))
      (node (ref "R95") (pin "1") (pinfunction "1_1") (pintype "passive"))
    )
    (net (code "200") (name "Net-(J3-VDD)") (class "Default")
      (node (ref "C81") (pin "1") (pinfunction "1_1") (pintype "passive"))
      (node (ref "C82") (pin "2") (pinfunction "2_2") (pintype "passive"))
      (node (ref "FB4") (pin "2") (pinfunction "2_2") (pintype "bidirectional"))
      (node (ref "J3") (pin "4") (pinfunction "VDD_4") (pintype "bidirectional"))
      (node (ref "R105") (pin "2") (pinfunction "2_2") (pintype "passive"))
      (node (ref "R106") (pin "2") (pinfunction "2_2") (pintype "passive"))
      (node (ref "R85") (pin "2") (pinfunction "2_2") (pintype "passive"))
      (node (ref "R94") (pin "2") (pinfunction "2_2") (pintype "passive"))
      (node (ref "R95") (pin "2") (pinfunction "2_2") (pintype "passive"))
      (node (ref "R96") (pin "2") (pinfunction "2_2") (pintype "passive"))
      (node (ref "R97") (pin "2") (pinfunction "2_2") (pintype "passive"))
    )
    (net (code "201") (name "Net-(J9-SHELL2)") (class "Default")
      (node (ref "FB7") (pin "2") (pinfunction "2_2") (pintype "bidirectional"))
      (node (ref "J9") (pin "P2") (pinfunction "SHELL2_P2") (pintype "bidirectional"))
      (node (ref "J9") (pin "P3") (pinfunction "SHELL3_P3") (pintype "bidirectional"))
    )
    (net (code "202") (name "Net-(L6-Pad1)") (class "Default")
      (node (ref "L6") (pin "1") (pinfunction "1_1") (pintype "passive"))
      (node (ref "R61") (pin "2") (pinfunction "2_2") (pintype "passive"))
      (node (ref "U11") (pin "1") (pinfunction "SW_1") (pintype "bidirectional"))
      (node (ref "U11") (pin "2") (pinfunction "SW_2") (pintype "bidirectional"))
      (node (ref "U11") (pin "3") (pinfunction "SW_3") (pintype "bidirectional"))
    )
    (net (code "203") (name "Net-(LED1-DOUT)") (class "Default")
      (node (ref "LED1") (pin "1") (pinfunction "DOUT_1") (pintype "bidirectional"))
      (node (ref "LED2") (pin "3") (pinfunction "DIN_3") (pintype "bidirectional"))
    )
    (net (code "204") (name "Net-(LED1-VDD)") (class "Default")
      (node (ref "C91") (pin "2") (pinfunction "2_2") (pintype "passive"))
      (node (ref "C92") (pin "2") (pinfunction "2_2") (pintype "passive"))
      (node (ref "LED1") (pin "4") (pinfunction "VDD_4") (pintype "bidirectional"))
      (node (ref "LED2") (pin "4") (pinfunction "VDD_4") (pintype "bidirectional"))
      (node (ref "R66") (pin "2") (pinfunction "2_2") (pintype "passive"))
    )
    (net (code "205") (name "Net-(Q1-G)") (class "Default")
      (node (ref "Q1") (pin "1") (pinfunction "G_1") (pintype "passive"))
      (node (ref "R70") (pin "2") (pinfunction "2_2") (pintype "passive"))
    )
    (net (code "206") (name "Net-(Q2-D)") (class "Default")
      (node (ref "Q2") (pin "3") (pinfunction "D_3") (pintype "passive"))
      (node (ref "Q3") (pin "3") (pinfunction "D_3") (pintype "passive"))
    )
    (net (code "207") (name "Net-(Q4-B)") (class "Default")
      (node (ref "Q4") (pin "1") (pinfunction "B_1") (pintype "passive"))
      (node (ref "R9") (pin "1") (pinfunction "1_1") (pintype "passive"))
    )
    (net (code "208") (name "Net-(Q4-E)") (class "Default")
      (node (ref "Q4") (pin "2") (pinfunction "E_2") (pintype "passive"))
      (node (ref "R14") (pin "2") (pinfunction "2_2") (pintype "passive"))
      (node (ref "U5") (pin "24") (pinfunction "RTS_24") (pintype "bidirectional"))
    )
    (net (code "209") (name "Net-(Q5-B)") (class "Default")
      (node (ref "Q5") (pin "1") (pinfunction "B_1") (pintype "passive"))
      (node (ref "R14") (pin "1") (pinfunction "1_1") (pintype "passive"))
    )
    (net (code "210") (name "Net-(Q5-E)") (class "Default")
      (node (ref "Q5") (pin "2") (pinfunction "E_2") (pintype "passive"))
      (node (ref "R9") (pin "2") (pinfunction "2_2") (pintype "passive"))
      (node (ref "U5") (pin "28") (pinfunction "DTR_28") (pintype "bidirectional"))
    )
    (net (code "211") (name "Net-(R6-Pad2)") (class "Default")
      (node (ref "R6") (pin "2") (pinfunction "2_2") (pintype "passive"))
      (node (ref "U4") (pin "20") (pinfunction "AVSS_20") (pintype "bidirectional"))
      (node (ref "U4") (pin "21") (pinfunction "AVSS_21") (pintype "bidirectional"))
    )
    (net (code "212") (name "Net-(R51-Pad2)") (class "Default")
      (node (ref "R51") (pin "2") (pinfunction "2_2") (pintype "passive"))
      (node (ref "SW4") (pin "7") (pinfunction "7_7") (pintype "bidirectional"))
    )
    (net (code "213") (name "Net-(R52-Pad2)") (class "Default")
      (node (ref "R52") (pin "2") (pinfunction "2_2") (pintype "passive"))
      (node (ref "SW4") (pin "8") (pinfunction "8_8") (pintype "bidirectional"))
    )
    (net (code "214") (name "Net-(R82-Pad2)") (class "Default")
      (node (ref "R82") (pin "2") (pinfunction "2_2") (pintype "passive"))
      (node (ref "SW4") (pin "6") (pinfunction "6_6") (pintype "bidirectional"))
    )
    (net (code "215") (name "Net-(R83-Pad2)") (class "Default")
      (node (ref "R83") (pin "2") (pinfunction "2_2") (pintype "passive"))
      (node (ref "SW4") (pin "9") (pinfunction "9_9") (pintype "bidirectional"))
    )
    (net (code "216") (name "Net-(R92-Pad2)") (class "Default")
      (node (ref "R92") (pin "2") (pinfunction "2_2") (pintype "passive"))
      (node (ref "SW4") (pin "10") (pinfunction "10_10") (pintype "bidirectional"))
    )
    (net (code "217") (name "Net-(U1-IO_L3P_T0_DQS_PUDC_B_14)") (class "Default")
      (node (ref "R65") (pin "1") (pinfunction "1_1") (pintype "passive"))
      (node (ref "U1") (pin "B10") (pinfunction "IO_L3P_T0_DQS_PUDC_B_14_B10") (pintype "bidirectional"))
    )
    (net (code "218") (name "Net-(U2-CAP1)") (class "Default")
      (node (ref "C20") (pin "1") (pinfunction "1_1") (pintype "passive"))
      (node (ref "C21") (pin "1") (pinfunction "1_1") (pintype "passive"))
      (node (ref "R1") (pin "1") (pinfunction "1_1") (pintype "passive"))
      (node (ref "U2") (pin "48") (pinfunction "CAP1_48") (pintype "bidirectional"))
    )
    (net (code "219") (name "Net-(U2-CAP2)") (class "Default")
      (node (ref "C20") (pin "2") (pinfunction "2_2") (pintype "passive"))
      (node (ref "R1") (pin "2") (pinfunction "2_2") (pintype "passive"))
      (node (ref "U2") (pin "47") (pinfunction "CAP2_47") (pintype "bidirectional"))
    )
    (net (code "220") (name "Net-(U2-LNA_IN)") (class "Default")
      (node (ref "L1") (pin "2") (pinfunction "2_2") (pintype "passive"))
      (node (ref "R58") (pin "2") (pinfunction "2_2") (pintype "passive"))
      (node (ref "U2") (pin "2") (pinfunction "LNA_IN_2") (pintype "bidirectional"))
    )
    (net (code "221") (name "Net-(U3-VCC)") (class "Default")
      (node (ref "C24") (pin "1") (pinfunction "1_1") (pintype "passive"))
      (node (ref "R2") (pin "1") (pinfunction "1_1") (pintype "passive"))
      (node (ref "R3") (pin "1") (pinfunction "1_1") (pintype "passive"))
      (node (ref "U3") (pin "8") (pinfunction "VCC_8") (pintype "bidirectional"))
    )
    (net (code "222") (name "Net-(U5-D+)") (class "Default")
      (node (ref "L15") (pin "4") (pinfunction "4_4") (pintype "bidirectional"))
      (node (ref "U5") (pin "4") (pinfunction "D+_4") (pintype "bidirectional"))
    )
    (net (code "223") (name "Net-(U5-D-)") (class "Default")
      (node (ref "L15") (pin "1") (pinfunction "1_1") (pintype "bidirectional"))
      (node (ref "U5") (pin "5") (pinfunction "D-_5") (pintype "bidirectional"))
    )
    (net (code "224") (name "Net-(U5-RXD)") (class "Default")
      (node (ref "C83") (pin "1") (pinfunction "1_1") (pintype "passive"))
      (node (ref "R12") (pin "2") (pinfunction "2_2") (pintype "passive"))
      (node (ref "U5") (pin "25") (pinfunction "RXD_25") (pintype "bidirectional"))
    )
    (net (code "225") (name "Net-(U5-TXD)") (class "Default")
      (node (ref "R10") (pin "2") (pinfunction "2_2") (pintype "passive"))
      (node (ref "U5") (pin "26") (pinfunction "TXD_26") (pintype "bidirectional"))
    )
    (net (code "226") (name "Net-(U5-~{RST})") (class "Default")
      (node (ref "C13") (pin "2") (pinfunction "2_2") (pintype "passive"))
      (node (ref "R8") (pin "1") (pinfunction "1_1") (pintype "passive"))
      (node (ref "U5") (pin "9") (pinfunction "~{RST}_9") (pintype "bidirectional"))
    )
    (net (code "227") (name "Net-(U6-AVDD{slash}VREF)") (class "Default")
      (node (ref "C29") (pin "1") (pinfunction "1_1") (pintype "passive"))
      (node (ref "FB3") (pin "1") (pinfunction "1_1") (pintype "bidirectional"))
      (node (ref "U6") (pin "4") (pinfunction "AVDD/VREF_4") (pintype "bidirectional"))
    )
    (net (code "228") (name "Net-(U6-GND)") (class "Default")
      (node (ref "R7") (pin "1") (pinfunction "1_1") (pintype "passive"))
      (node (ref "U6") (pin "5") (pinfunction "GND_5") (pintype "bidirectional"))
    )
    (net (code "229") (name "Net-(U11-EN)") (class "Default")
      (node (ref "R62") (pin "2") (pinfunction "2_2") (pintype "passive"))
      (node (ref "U11") (pin "13") (pinfunction "EN_13") (pintype "bidirectional"))
    )
    (net (code "230") (name "Net-(U11-FB)") (class "Default")
      (node (ref "R134") (pin "2") (pinfunction "2_2") (pintype "passive"))
      (node (ref "R135") (pin "1") (pinfunction "1_1") (pintype "passive"))
      (node (ref "U11") (pin "5") (pinfunction "FB_5") (pintype "bidirectional"))
    )
    (net (code "231") (name "Net-(U11-PG)") (class "Default")
      (node (ref "R61") (pin "1") (pinfunction "1_1") (pintype "passive"))
      (node (ref "U11") (pin "4") (pinfunction "PG_4") (pintype "bidirectional"))
    )
    (net (code "232") (name "Net-(U11-SS{slash}TR)") (class "Default")
      (node (ref "C53") (pin "2") (pinfunction "2_2") (pintype "passive"))
      (node (ref "U11") (pin "9") (pinfunction "SS/TR_9") (pintype "bidirectional"))
    )
    (net (code "233") (name "Net-(U11-VOS)") (class "Default")
      (node (ref "C74") (pin "2") (pinfunction "2_2") (pintype "passive"))
      (node (ref "C76") (pin "2") (pinfunction "2_2") (pintype "passive"))
      (node (ref "C77") (pin "2") (pinfunction "2_2") (pintype "passive"))
      (node (ref "FB6") (pin "1") (pinfunction "1_1") (pintype "bidirectional"))
      (node (ref "L6") (pin "2") (pinfunction "2_2") (pintype "passive"))
      (node (ref "R134") (pin "1") (pinfunction "1_1") (pintype "passive"))
      (node (ref "U11") (pin "14") (pinfunction "VOS_14") (pintype "bidirectional"))
    )
    (net (code "234") (name "Net-(U12-CS)") (class "Default")
      (node (ref "R117") (pin "1") (pinfunction "1_1") (pintype "passive"))
      (node (ref "U12") (pin "12") (pinfunction "CS_12") (pintype "bidirectional"))
    )
    (net (code "235") (name "Net-(U13-EN)") (class "Default")
      (node (ref "R39") (pin "2") (pinfunction "2_2") (pintype "passive"))
      (node (ref "U13") (pin "7") (pinfunction "VREF2_7") (pintype "bidirectional"))
      (node (ref "U13") (pin "8") (pinfunction "EN_8") (pintype "bidirectional"))
    )
    (net (code "236") (name "Net-(USB2-A4{slash}B9{slash}VBUS)") (class "Default")
      (node (ref "D21") (pin "1") (pinfunction "1_1") (pintype "bidirectional"))
      (node (ref "F1") (pin "2") (pinfunction "2_2") (pintype "bidirectional"))
      (node (ref "USB2") (pin "A4_B9") (pinfunction "A4/B9/VBUS_A4_B9") (pintype "bidirectional"))
      (node (ref "USB2") (pin "B4_A9") (pinfunction "B4/A9/VBUS_B4_A9") (pintype "bidirectional"))
    )
    (net (code "237") (name "Net-(USB2-A5{slash}CC1)") (class "Default")
      (node (ref "R22") (pin "1") (pinfunction "1_1") (pintype "passive"))
      (node (ref "USB2") (pin "A5") (pinfunction "A5/CC1_A5") (pintype "bidirectional"))
    )
    (net (code "238") (name "Net-(USB2-B5{slash}CC2)") (class "Default")
      (node (ref "R15") (pin "1") (pinfunction "1_1") (pintype "passive"))
      (node (ref "USB2") (pin "B5") (pinfunction "B5/CC2_B5") (pintype "bidirectional"))
    )
    (net (code "239") (name "Net-(X2-ENABLE)") (class "Default")
      (node (ref "R149") (pin "2") (pinfunction "2_2") (pintype "passive"))
      (node (ref "R50") (pin "1") (pinfunction "1_1") (pintype "passive"))
      (node (ref "X2") (pin "1") (pinfunction "ENABLE_1") (pintype "bidirectional"))
    )
    (net (code "240") (name "Net-(X2-OUT)") (class "Default")
      (node (ref "R16") (pin "1") (pinfunction "1_1") (pintype "passive"))
      (node (ref "X2") (pin "3") (pinfunction "OUT_3") (pintype "bidirectional"))
    )
    (net (code "241") (name "Net-(X3-X2)") (class "Default")
      (node (ref "C2") (pin "2") (pinfunction "2_2") (pintype "passive"))
      (node (ref "R47") (pin "2") (pinfunction "2_2") (pintype "passive"))
      (node (ref "X3") (pin "3") (pinfunction "X2_3") (pintype "bidirectional"))
    )
    (net (code "242") (name "POWER_BAR") (class "Default")
      (node (ref "C16") (pin "2") (pinfunction "2_2") (pintype "passive"))
      (node (ref "C17") (pin "2") (pinfunction "2_2") (pintype "passive"))
      (node (ref "R8") (pin "2") (pinfunction "2_2") (pintype "passive"))
      (node (ref "U5") (pin "6") (pinfunction "VDD_6") (pintype "bidirectional"))
    )
    (net (code "243") (name "SDCARD_CCLK") (class "Default")
      (node (ref "C80") (pin "1") (pinfunction "1_1") (pintype "passive"))
      (node (ref "R111") (pin "1") (pinfunction "1_1") (pintype "passive"))
      (node (ref "U2") (pin "17") (pinfunction "MTMS_17") (pintype "bidirectional"))
    )
    (net (code "244") (name "SDCARD_CD") (class "Default")
      (node (ref "R107") (pin "1") (pinfunction "1_1") (pintype "passive"))
      (node (ref "U2") (pin "25") (pinfunction "GPIO16_25") (pintype "bidirectional"))
    )
    (net (code "245") (name "SDCARD_CMD") (class "Default")
      (node (ref "R110") (pin "1") (pinfunction "1_1") (pintype "passive"))
      (node (ref "U2") (pin "21") (pinfunction "MTDO_21") (pintype "bidirectional"))
    )
    (net (code "246") (name "SDCARD_D0") (class "Default")
      (node (ref "R112") (pin "1") (pinfunction "1_1") (pintype "passive"))
      (node (ref "U2") (pin "22") (pinfunction "GPIO2_22") (pintype "bidirectional"))
    )
    (net (code "247") (name "SDCARD_D1") (class "Default")
      (node (ref "R113") (pin "1") (pinfunction "1_1") (pintype "passive"))
      (node (ref "U2") (pin "24") (pinfunction "GPIO4_24") (pintype "bidirectional"))
    )
    (net (code "248") (name "SDCARD_D2") (class "Default")
      (node (ref "R108") (pin "1") (pinfunction "1_1") (pintype "passive"))
      (node (ref "U2") (pin "18") (pinfunction "MTDI_18") (pintype "bidirectional"))
    )
    (net (code "249") (name "SDCARD_D3") (class "Default")
      (node (ref "R109") (pin "1") (pinfunction "1_1") (pintype "passive"))
      (node (ref "U2") (pin "20") (pinfunction "MTCK_20") (pintype "bidirectional"))
    )
    (net (code "250") (name "SYSCLK") (class "Default")
      (node (ref "C71") (pin "1") (pinfunction "1_1") (pintype "passive"))
      (node (ref "R16") (pin "2") (pinfunction "2_2") (pintype "passive"))
      (node (ref "U1") (pin "H4") (pinfunction "IO_L13P_T2_MRCC_34_H4") (pintype "bidirectional"))
    )
    (net (code "251") (name "U0RXD") (class "Default")
      (node (ref "C100") (pin "1") (pinfunction "1_1") (pintype "passive"))
      (node (ref "R10") (pin "1") (pinfunction "1_1") (pintype "passive"))
      (node (ref "U2") (pin "40") (pinfunction "U0RXD_40") (pintype "bidirectional"))
    )
    (net (code "252") (name "U0TXD") (class "Default")
      (node (ref "R12") (pin "1") (pinfunction "1_1") (pintype "passive"))
      (node (ref "U2") (pin "41") (pinfunction "U0TXD_41") (pintype "bidirectional"))
    )
    (net (code "253") (name "VCC_1V") (class "Default")
      (node (ref "C31") (pin "1") (pinfunction "1_1") (pintype "passive"))
      (node (ref "C32") (pin "1") (pinfunction "1_1") (pintype "passive"))
      (node (ref "C33") (pin "1") (pinfunction "1_1") (pintype "passive"))
      (node (ref "C34") (pin "1") (pinfunction "1_1") (pintype "passive"))
      (node (ref "C35") (pin "1") (pinfunction "1_1") (pintype "passive"))
      (node (ref "C36") (pin "1") (pinfunction "1_1") (pintype "passive"))
      (node (ref "C37") (pin "1") (pinfunction "1_1") (pintype "passive"))
      (node (ref "C38") (pin "1") (pinfunction "1_1") (pintype "passive"))
      (node (ref "C39") (pin "1") (pinfunction "1_1") (pintype "passive"))
      (node (ref "C41") (pin "1") (pinfunction "1_1") (pintype "passive"))
      (node (ref "C45") (pin "1") (pinfunction "1_1") (pintype "passive"))
      (node (ref "C46") (pin "1") (pinfunction "1_1") (pintype "passive"))
      (node (ref "C52") (pin "2") (pinfunction "2_2") (pintype "passive"))
      (node (ref "C58") (pin "2") (pinfunction "2_2") (pintype "passive"))
      (node (ref "C59") (pin "1") (pinfunction "1_1") (pintype "passive"))
      (node (ref "C60") (pin "1") (pinfunction "1_1") (pintype "passive"))
      (node (ref "U1") (pin "D6") (pinfunction "VCCINT_D6") (pintype "bidirectional"))
      (node (ref "U1") (pin "D8") (pinfunction "VCCINT_D8") (pintype "bidirectional"))
      (node (ref "U1") (pin "E5") (pinfunction "VCCBRAM_E5") (pintype "bidirectional"))
      (node (ref "U1") (pin "E7") (pinfunction "VCCINT_E7") (pintype "bidirectional"))
      (node (ref "U1") (pin "E9") (pinfunction "VCCINT_E9") (pintype "bidirectional"))
      (node (ref "U1") (pin "F6") (pinfunction "VCCINT_F6") (pintype "bidirectional"))
      (node (ref "U1") (pin "G5") (pinfunction "VCCBRAM_G5") (pintype "bidirectional"))
      (node (ref "U1") (pin "G9") (pinfunction "VCCINT_G9") (pintype "bidirectional"))
      (node (ref "U1") (pin "H6") (pinfunction "VCCINT_H6") (pintype "bidirectional"))
      (node (ref "U1") (pin "J5") (pinfunction "VCCBRAM_J5") (pintype "bidirectional"))
      (node (ref "U1") (pin "J9") (pinfunction "VCCINT_J9") (pintype "bidirectional"))
      (node (ref "U1") (pin "K6") (pinfunction "VCCINT_K6") (pintype "bidirectional"))
      (node (ref "U1") (pin "K8") (pinfunction "VCCINT_K8") (pintype "bidirectional"))
      (node (ref "U8") (pin "5") (pinfunction "VOUT_5") (pintype "bidirectional"))
    )
    (net (code "254") (name "VCC_1V8") (class "Default")
      (node (ref "C40") (pin "1") (pinfunction "1_1") (pintype "passive"))
      (node (ref "C42") (pin "1") (pinfunction "1_1") (pintype "passive"))
      (node (ref "C43") (pin "1") (pinfunction "1_1") (pintype "passive"))
      (node (ref "C44") (pin "1") (pinfunction "1_1") (pintype "passive"))
      (node (ref "C61") (pin "2") (pinfunction "2_2") (pintype "passive"))
      (node (ref "C62") (pin "2") (pinfunction "2_2") (pintype "passive"))
      (node (ref "C63") (pin "1") (pinfunction "1_1") (pintype "passive"))
      (node (ref "C64") (pin "1") (pinfunction "1_1") (pintype "passive"))
      (node (ref "U1") (pin "F10") (pinfunction "VCCAUX_F10") (pintype "bidirectional"))
      (node (ref "U1") (pin "F8") (pinfunction "NC_F8") (pintype "bidirectional"))
      (node (ref "U1") (pin "H10") (pinfunction "VCCAUX_H10") (pintype "bidirectional"))
      (node (ref "U1") (pin "K10") (pinfunction "VCCAUX_K10") (pintype "bidirectional"))
      (node (ref "U1") (pin "L9") (pinfunction "VCCAUX_L9") (pintype "bidirectional"))
      (node (ref "U9") (pin "5") (pinfunction "VOUT_5") (pintype "bidirectional"))
    )
    (net (code "255") (name "VCC_3V3") (class "Default")
      (node (ref "C105") (pin "1") (pinfunction "1_1") (pintype "passive"))
      (node (ref "C106") (pin "2") (pinfunction "2_2") (pintype "passive"))
      (node (ref "C25") (pin "1") (pinfunction "1_1") (pintype "passive"))
      (node (ref "C27") (pin "1") (pinfunction "1_1") (pintype "passive"))
      (node (ref "C28") (pin "1") (pinfunction "1_1") (pintype "passive"))
      (node (ref "C30") (pin "1") (pinfunction "1_1") (pintype "passive"))
      (node (ref "C48") (pin "2") (pinfunction "2_2") (pintype "passive"))
      (node (ref "C49") (pin "2") (pinfunction "2_2") (pintype "passive"))
      (node (ref "C50") (pin "1") (pinfunction "1_1") (pintype "passive"))
      (node (ref "C51") (pin "1") (pinfunction "1_1") (pintype "passive"))
      (node (ref "C72") (pin "1") (pinfunction "1_1") (pintype "passive"))
      (node (ref "C73") (pin "1") (pinfunction "1_1") (pintype "passive"))
      (node (ref "C75") (pin "1") (pinfunction "1_1") (pintype "passive"))
      (node (ref "C78") (pin "1") (pinfunction "1_1") (pintype "passive"))
      (node (ref "C85") (pin "2") (pinfunction "2_2") (pintype "passive"))
      (node (ref "C90") (pin "2") (pinfunction "2_2") (pintype "passive"))
      (node (ref "D10") (pin "+") (pinfunction "+_+") (pintype "passive"))
      (node (ref "FB1") (pin "2") (pinfunction "2_2") (pintype "bidirectional"))
      (node (ref "FB2") (pin "1") (pinfunction "1_1") (pintype "bidirectional"))
      (node (ref "FB3") (pin "2") (pinfunction "2_2") (pintype "bidirectional"))
      (node (ref "FB4") (pin "1") (pinfunction "1_1") (pintype "bidirectional"))
      (node (ref "FB5") (pin "1") (pinfunction "1_1") (pintype "bidirectional"))
      (node (ref "J2") (pin "3") (pinfunction "3_3") (pintype "bidirectional"))
      (node (ref "J4") (pin "3") (pinfunction "3_3") (pintype "bidirectional"))
      (node (ref "J8") (pin "1") (pinfunction "1_1") (pintype "bidirectional"))
      (node (ref "Q2") (pin "2") (pinfunction "S_2") (pintype "passive"))
      (node (ref "R101") (pin "1") (pinfunction "1_1") (pintype "passive"))
      (node (ref "R102") (pin "1") (pinfunction "1_1") (pintype "passive"))
      (node (ref "R103") (pin "1") (pinfunction "1_1") (pintype "passive"))
      (node (ref "R144") (pin "2") (pinfunction "2_2") (pintype "passive"))
      (node (ref "R147") (pin "2") (pinfunction "2_2") (pintype "passive"))
      (node (ref "R148") (pin "1") (pinfunction "1_1") (pintype "passive"))
      (node (ref "R17") (pin "2") (pinfunction "2_2") (pintype "passive"))
      (node (ref "R18") (pin "2") (pinfunction "2_2") (pintype "passive"))
      (node (ref "R180") (pin "2") (pinfunction "2_2") (pintype "passive"))
      (node (ref "R181") (pin "2") (pinfunction "2_2") (pintype "passive"))
      (node (ref "R182") (pin "2") (pinfunction "2_2") (pintype "passive"))
      (node (ref "R183") (pin "1") (pinfunction "1_1") (pintype "passive"))
      (node (ref "R186") (pin "2") (pinfunction "2_2") (pintype "passive"))
      (node (ref "R21") (pin "2") (pinfunction "2_2") (pintype "passive"))
      (node (ref "R30") (pin "2") (pinfunction "2_2") (pintype "passive"))
      (node (ref "R31") (pin "2") (pinfunction "2_2") (pintype "passive"))
      (node (ref "R37") (pin "2") (pinfunction "2_2") (pintype "passive"))
      (node (ref "R42") (pin "1") (pinfunction "1_1") (pintype "passive"))
      (node (ref "R43") (pin "1") (pinfunction "1_1") (pintype "passive"))
      (node (ref "R48") (pin "2") (pinfunction "2_2") (pintype "passive"))
      (node (ref "R50") (pin "2") (pinfunction "2_2") (pintype "passive"))
      (node (ref "R51") (pin "1") (pinfunction "1_1") (pintype "passive"))
      (node (ref "R52") (pin "1") (pinfunction "1_1") (pintype "passive"))
      (node (ref "R53") (pin "1") (pinfunction "1_1") (pintype "passive"))
      (node (ref "R54") (pin "1") (pinfunction "1_1") (pintype "passive"))
      (node (ref "R55") (pin "1") (pinfunction "1_1") (pintype "passive"))
      (node (ref "R56") (pin "1") (pinfunction "1_1") (pintype "passive"))
      (node (ref "R57") (pin "1") (pinfunction "1_1") (pintype "passive"))
      (node (ref "R66") (pin "1") (pinfunction "1_1") (pintype "passive"))
      (node (ref "R72") (pin "1") (pinfunction "1_1") (pintype "passive"))
      (node (ref "R73") (pin "1") (pinfunction "1_1") (pintype "passive"))
      (node (ref "R74") (pin "1") (pinfunction "1_1") (pintype "passive"))
      (node (ref "R75") (pin "1") (pinfunction "1_1") (pintype "passive"))
      (node (ref "R76") (pin "1") (pinfunction "1_1") (pintype "passive"))
      (node (ref "R77") (pin "1") (pinfunction "1_1") (pintype "passive"))
      (node (ref "R78") (pin "1") (pinfunction "1_1") (pintype "passive"))
      (node (ref "R79") (pin "1") (pinfunction "1_1") (pintype "passive"))
      (node (ref "R82") (pin "1") (pinfunction "1_1") (pintype "passive"))
      (node (ref "R83") (pin "1") (pinfunction "1_1") (pintype "passive"))
      (node (ref "R92") (pin "1") (pinfunction "1_1") (pintype "passive"))
      (node (ref "U1") (pin "G13") (pinfunction "VCCO_14_G13") (pintype "bidirectional"))
      (node (ref "U1") (pin "G2") (pinfunction "VCCO_34_G2") (pintype "bidirectional"))
      (node (ref "U1") (pin "K13") (pinfunction "VCCO_14_K13") (pintype "bidirectional"))
      (node (ref "U1") (pin "K2") (pinfunction "VCCO_34_K2") (pintype "bidirectional"))
      (node (ref "U1") (pin "N13") (pinfunction "VCCO_14_N13") (pintype "bidirectional"))
      (node (ref "U1") (pin "N2") (pinfunction "VCCO_34_N2") (pintype "bidirectional"))
      (node (ref "U1") (pin "N6") (pinfunction "VCCO_0_N6") (pintype "bidirectional"))
      (node (ref "U1") (pin "N7") (pinfunction "CFGBVS_0_N7") (pintype "bidirectional"))
      (node (ref "U1") (pin "N8") (pinfunction "VCCO_0_N8") (pintype "bidirectional"))
      (node (ref "U13") (pin "2") (pinfunction "VREF1_2") (pintype "bidirectional"))
      (node (ref "U17") (pin "1") (pinfunction "VCCA_1") (pintype "bidirectional"))
      (node (ref "U18") (pin "1") (pinfunction "VCCA_1") (pintype "bidirectional"))
      (node (ref "U4") (pin "11") (pinfunction "DVDD_11") (pintype "bidirectional"))
      (node (ref "U4") (pin "13") (pinfunction "DVDD_13") (pintype "bidirectional"))
      (node (ref "U4") (pin "17") (pinfunction "VRT_17") (pintype "bidirectional"))
      (node (ref "U7") (pin "2") (pinfunction "OUT_2") (pintype "bidirectional"))
      (node (ref "U7") (pin "TER") (pinfunction "OUT_TER") (pintype "bidirectional"))
      (node (ref "X2") (pin "4") (pinfunction "VDD_4") (pintype "bidirectional"))
    )
    (net (code "256") (name "VCC_3V3_AR") (class "Default")
      (node (ref "Q3") (pin "2") (pinfunction "S_2") (pintype "passive"))
      (node (ref "R148") (pin "2") (pinfunction "2_2") (pintype "passive"))
      (node (ref "R49") (pin "1") (pinfunction "1_1") (pintype "passive"))
      (node (ref "U10") (pin "29") (pinfunction "3V3_29") (pintype "bidirectional"))
    )
    (net (code "257") (name "VCC_5V") (class "Default")
      (node (ref "C10") (pin "1") (pinfunction "1_1") (pintype "passive"))
      (node (ref "C101") (pin "2") (pinfunction "2_2") (pintype "passive"))
      (node (ref "C102") (pin "1") (pinfunction "1_1") (pintype "passive"))
      (node (ref "C103") (pin "2") (pinfunction "2_2") (pintype "passive"))
      (node (ref "C104") (pin "1") (pinfunction "1_1") (pintype "passive"))
      (node (ref "C11") (pin "1") (pinfunction "1_1") (pintype "passive"))
      (node (ref "C65") (pin "1") (pinfunction "1_1") (pintype "passive"))
      (node (ref "C66") (pin "1") (pinfunction "1_1") (pintype "passive"))
      (node (ref "C67") (pin "1") (pinfunction "1_1") (pintype "passive"))
      (node (ref "C68") (pin "1") (pinfunction "1_1") (pintype "passive"))
      (node (ref "C69") (pin "2") (pinfunction "2_2") (pintype "passive"))
      (node (ref "C70") (pin "2") (pinfunction "2_2") (pintype "passive"))
      (node (ref "C90") (pin "1") (pinfunction "1_1") (pintype "passive"))
      (node (ref "C93") (pin "1") (pinfunction "1_1") (pintype "passive"))
      (node (ref "F2") (pin "2") (pinfunction "2_2") (pintype "bidirectional"))
      (node (ref "J15") (pin "1") (pinfunction "P$1_1") (pintype "bidirectional"))
      (node (ref "R13") (pin "1") (pinfunction "1_1") (pintype "passive"))
      (node (ref "R146") (pin "2") (pinfunction "2_2") (pintype "passive"))
      (node (ref "R150") (pin "2") (pinfunction "2_2") (pintype "passive"))
      (node (ref "R151") (pin "2") (pinfunction "2_2") (pintype "passive"))
      (node (ref "R171") (pin "2") (pinfunction "2_2") (pintype "passive"))
      (node (ref "R187") (pin "1") (pinfunction "1_1") (pintype "passive"))
      (node (ref "SW1") (pin "COM1") (pinfunction "COM1_COM1") (pintype "bidirectional"))
      (node (ref "SW1") (pin "COM2") (pinfunction "COM2_COM2") (pintype "bidirectional"))
      (node (ref "SW2") (pin "10") (pinfunction "V+_10") (pintype "bidirectional"))
      (node (ref "U17") (pin "14") (pinfunction "VCCB_14") (pintype "bidirectional"))
      (node (ref "U18") (pin "14") (pinfunction "VCCB_14") (pintype "bidirectional"))
      (node (ref "U7") (pin "3") (pinfunction "IN_3") (pintype "bidirectional"))
      (node (ref "U8") (pin "1") (pinfunction "VIN_1") (pintype "bidirectional"))
      (node (ref "U8") (pin "3") (pinfunction "CE_3") (pintype "bidirectional"))
      (node (ref "U9") (pin "1") (pinfunction "VIN_1") (pintype "bidirectional"))
      (node (ref "U9") (pin "3") (pinfunction "CE_3") (pintype "bidirectional"))
    )
    (net (code "258") (name "VCC_5V_AR") (class "Default")
      (node (ref "J15") (pin "2") (pinfunction "P$2_2") (pintype "bidirectional"))
      (node (ref "J5") (pin "6") (pinfunction "6_6") (pintype "bidirectional"))
      (node (ref "U10") (pin "28") (pinfunction "5V_28") (pintype "bidirectional"))
    )
    (net (code "259") (name "VCC_ESP") (class "Default")
      (node (ref "C22") (pin "1") (pinfunction "1_1") (pintype "passive"))
      (node (ref "C23") (pin "1") (pinfunction "1_1") (pintype "passive"))
      (node (ref "C4") (pin "1") (pinfunction "1_1") (pintype "passive"))
      (node (ref "C5") (pin "1") (pinfunction "1_1") (pintype "passive"))
      (node (ref "C6") (pin "1") (pinfunction "1_1") (pintype "passive"))
      (node (ref "C7") (pin "1") (pinfunction "1_1") (pintype "passive"))
      (node (ref "C8") (pin "1") (pinfunction "1_1") (pintype "passive"))
      (node (ref "C9") (pin "1") (pinfunction "1_1") (pintype "passive"))
      (node (ref "FB1") (pin "1") (pinfunction "1_1") (pintype "bidirectional"))
      (node (ref "R104") (pin "1") (pinfunction "1_1") (pintype "passive"))
      (node (ref "R116") (pin "1") (pinfunction "1_1") (pintype "passive"))
      (node (ref "R125") (pin "2") (pinfunction "2_2") (pintype "passive"))
      (node (ref "R127") (pin "1") (pinfunction "1_1") (pintype "passive"))
      (node (ref "R3") (pin "2") (pinfunction "2_2") (pintype "passive"))
      (node (ref "R4") (pin "2") (pinfunction "2_2") (pintype "passive"))
      (node (ref "R5") (pin "2") (pinfunction "2_2") (pintype "passive"))
      (node (ref "U2") (pin "1") (pinfunction "VDDA_1") (pintype "bidirectional"))
      (node (ref "U2") (pin "19") (pinfunction "VDD3P3_RTC_19") (pintype "bidirectional"))
      (node (ref "U2") (pin "3") (pinfunction "VDD3P3_3") (pintype "bidirectional"))
      (node (ref "U2") (pin "37") (pinfunction "VDD3P3_CPU_37") (pintype "bidirectional"))
      (node (ref "U2") (pin "4") (pinfunction "VDD3P3_4") (pintype "bidirectional"))
      (node (ref "U2") (pin "43") (pinfunction "VDDA_43") (pintype "bidirectional"))
      (node (ref "U2") (pin "46") (pinfunction "VDDA_46") (pintype "bidirectional"))
    )
    (net (code "260") (name "VERSION_1") (class "Default")
      (node (ref "R18") (pin "1") (pinfunction "1_1") (pintype "passive"))
      (node (ref "R20") (pin "2") (pinfunction "2_2") (pintype "passive"))
      (node (ref "U1") (pin "P4") (pinfunction "IO_L21P_T3_DQS_34_P4") (pintype "bidirectional"))
    )
    (net (code "261") (name "VERSION_2") (class "Default")
      (node (ref "R17") (pin "1") (pinfunction "1_1") (pintype "passive"))
      (node (ref "R19") (pin "2") (pinfunction "2_2") (pintype "passive"))
      (node (ref "U1") (pin "P3") (pinfunction "IO_L21N_T3_DQS_34_P3") (pintype "bidirectional"))
    )
    (net (code "262") (name "VERSION_3") (class "Default")
      (node (ref "R145") (pin "2") (pinfunction "2_2") (pintype "passive"))
      (node (ref "R147") (pin "1") (pinfunction "1_1") (pintype "passive"))
      (node (ref "U1") (pin "C14") (pinfunction "IO_L11N_T1_SRCC_14_C14") (pintype "bidirectional"))
    )
    (net (code "263") (name "VIN") (class "Default")
      (node (ref "C47") (pin "2") (pinfunction "2_2") (pintype "passive"))
      (node (ref "C54") (pin "2") (pinfunction "2_2") (pintype "passive"))
      (node (ref "C55") (pin "2") (pinfunction "2_2") (pintype "passive"))
      (node (ref "C56") (pin "2") (pinfunction "2_2") (pintype "passive"))
      (node (ref "C57") (pin "2") (pinfunction "2_2") (pintype "passive"))
      (node (ref "C93") (pin "2") (pinfunction "2_2") (pintype "passive"))
      (node (ref "R62") (pin "1") (pinfunction "1_1") (pintype "passive"))
      (node (ref "TP5") (pin "T") (pinfunction "T_T") (pintype "bidirectional"))
      (node (ref "U10") (pin "25") (pinfunction "VIN_25") (pintype "bidirectional"))
      (node (ref "U11") (pin "10") (pinfunction "AVIN_10") (pintype "bidirectional"))
      (node (ref "U11") (pin "11") (pinfunction "PVIN_11") (pintype "bidirectional"))
      (node (ref "U11") (pin "12") (pinfunction "PVIN_12") (pintype "bidirectional"))
    )
    (net (code "264") (name "VUSB") (class "Default")
      (node (ref "C1") (pin "2") (pinfunction "2_2") (pintype "passive"))
      (node (ref "C14") (pin "2") (pinfunction "2_2") (pintype "passive"))
      (node (ref "C15") (pin "2") (pinfunction "2_2") (pintype "passive"))
      (node (ref "F1") (pin "1") (pinfunction "1_1") (pintype "bidirectional"))
      (node (ref "SW1") (pin "CH1B") (pinfunction "CH1B_CH1B") (pintype "bidirectional"))
      (node (ref "SW1") (pin "CH2B") (pinfunction "CH2B_CH2B") (pintype "bidirectional"))
      (node (ref "U5") (pin "7") (pinfunction "REGIN_7") (pintype "bidirectional"))
      (node (ref "U5") (pin "8") (pinfunction "VBUS_8") (pintype "bidirectional"))
    )
    (net (code "265") (name "XTAL_N") (class "Default")
      (node (ref "R47") (pin "1") (pinfunction "1_1") (pintype "passive"))
      (node (ref "U2") (pin "44") (pinfunction "XTAL_N_44") (pintype "bidirectional"))
    )
    (net (code "266") (name "XTAL_P") (class "Default")
      (node (ref "C3") (pin "2") (pinfunction "2_2") (pintype "passive"))
      (node (ref "U2") (pin "45") (pinfunction "XTAL_P_45") (pintype "bidirectional"))
      (node (ref "X3") (pin "1") (pinfunction "X1_1") (pintype "bidirectional"))
    )
    (net (code "267") (name "unconnected-(J3-GND-Pad11)") (class "Default")
      (node (ref "J3") (pin "11") (pinfunction "GND_11") (pintype "bidirectional"))
    )
    (net (code "268") (name "unconnected-(J3-GND-Pad12)") (class "Default")
      (node (ref "J3") (pin "12") (pinfunction "GND_12") (pintype "bidirectional"))
    )
    (net (code "269") (name "unconnected-(J3-GND-Pad15)") (class "Default")
      (node (ref "J3") (pin "15") (pinfunction "GND_15") (pintype "bidirectional"))
    )
    (net (code "270") (name "unconnected-(J3-GND-Pad16)") (class "Default")
      (node (ref "J3") (pin "16") (pinfunction "GND_16") (pintype "bidirectional"))
    )
    (net (code "271") (name "unconnected-(J9-SHELL1-PadP1)") (class "Default")
      (node (ref "J9") (pin "P1") (pinfunction "SHELL1_P1") (pintype "bidirectional"))
    )
    (net (code "272") (name "unconnected-(J9-SHELL4-PadP4)") (class "Default")
      (node (ref "J9") (pin "P4") (pinfunction "SHELL4_P4") (pintype "bidirectional"))
    )
    (net (code "273") (name "unconnected-(J9-UTILITY-Pad17)") (class "Default")
      (node (ref "J9") (pin "17") (pinfunction "UTILITY_17") (pintype "bidirectional"))
    )
    (net (code "274") (name "unconnected-(J15-P$3-Pad3)") (class "Default")
      (node (ref "J15") (pin "3") (pinfunction "P$3_3") (pintype "bidirectional"))
    )
    (net (code "275") (name "unconnected-(LED2-DOUT-Pad1)") (class "Default")
      (node (ref "LED2") (pin "1") (pinfunction "DOUT_1") (pintype "bidirectional"))
    )
    (net (code "276") (name "unconnected-(SW2-COM3-Pad4)") (class "Default")
      (node (ref "SW2") (pin "4") (pinfunction "COM3_4") (pintype "bidirectional"))
    )
    (net (code "277") (name "unconnected-(SW2-COM4-Pad8)") (class "Default")
      (node (ref "SW2") (pin "8") (pinfunction "COM4_8") (pintype "bidirectional"))
    )
    (net (code "278") (name "unconnected-(SW2-IN3_4-Pad6)") (class "Default")
      (node (ref "SW2") (pin "6") (pinfunction "IN3_4_6") (pintype "bidirectional"))
    )
    (net (code "279") (name "unconnected-(SW2-NC3-Pad5)") (class "Default")
      (node (ref "SW2") (pin "5") (pinfunction "NC3_5") (pintype "bidirectional"))
    )
    (net (code "280") (name "unconnected-(SW2-NC4-Pad9)") (class "Default")
      (node (ref "SW2") (pin "9") (pinfunction "NC4_9") (pintype "bidirectional"))
    )
    (net (code "281") (name "unconnected-(SW2-NO3-Pad3)") (class "Default")
      (node (ref "SW2") (pin "3") (pinfunction "NO3_3") (pintype "bidirectional"))
    )
    (net (code "282") (name "unconnected-(SW2-NO4-Pad7)") (class "Default")
      (node (ref "SW2") (pin "7") (pinfunction "NO4_7") (pintype "bidirectional"))
    )
    (net (code "283") (name "unconnected-(U4-VRBS-Pad22)") (class "Default")
      (node (ref "U4") (pin "22") (pinfunction "VRBS_22") (pintype "bidirectional"))
    )
    (net (code "284") (name "unconnected-(U4-VRTS-Pad16)") (class "Default")
      (node (ref "U4") (pin "16") (pinfunction "VRTS_16") (pintype "bidirectional"))
    )
    (net (code "285") (name "unconnected-(U5-CTS-Pad23)") (class "Default")
      (node (ref "U5") (pin "23") (pinfunction "CTS_23") (pintype "bidirectional"))
    )
    (net (code "286") (name "unconnected-(U5-DCD-Pad1)") (class "Default")
      (node (ref "U5") (pin "1") (pinfunction "DCD_1") (pintype "bidirectional"))
    )
    (net (code "287") (name "unconnected-(U5-DSR-Pad27)") (class "Default")
      (node (ref "U5") (pin "27") (pinfunction "DSR_27") (pintype "bidirectional"))
    )
    (net (code "288") (name "unconnected-(U5-NC-Pad10)") (class "Default")
      (node (ref "U5") (pin "10") (pinfunction "NC_10") (pintype "bidirectional"))
    )
    (net (code "289") (name "unconnected-(U5-NC-Pad13)") (class "Default")
      (node (ref "U5") (pin "13") (pinfunction "NC_13") (pintype "bidirectional"))
    )
    (net (code "290") (name "unconnected-(U5-NC-Pad14)") (class "Default")
      (node (ref "U5") (pin "14") (pinfunction "NC_14") (pintype "bidirectional"))
    )
    (net (code "291") (name "unconnected-(U5-NC-Pad15)") (class "Default")
      (node (ref "U5") (pin "15") (pinfunction "NC_15") (pintype "bidirectional"))
    )
    (net (code "292") (name "unconnected-(U5-NC-Pad16)") (class "Default")
      (node (ref "U5") (pin "16") (pinfunction "NC_16") (pintype "bidirectional"))
    )
    (net (code "293") (name "unconnected-(U5-NC-Pad17)") (class "Default")
      (node (ref "U5") (pin "17") (pinfunction "NC_17") (pintype "bidirectional"))
    )
    (net (code "294") (name "unconnected-(U5-NC-Pad19)") (class "Default")
      (node (ref "U5") (pin "19") (pinfunction "NC_19") (pintype "bidirectional"))
    )
    (net (code "295") (name "unconnected-(U5-NC-Pad20)") (class "Default")
      (node (ref "U5") (pin "20") (pinfunction "NC_20") (pintype "bidirectional"))
    )
    (net (code "296") (name "unconnected-(U5-NC-Pad21)") (class "Default")
      (node (ref "U5") (pin "21") (pinfunction "NC_21") (pintype "bidirectional"))
    )
    (net (code "297") (name "unconnected-(U5-NC-Pad22)") (class "Default")
      (node (ref "U5") (pin "22") (pinfunction "NC_22") (pintype "bidirectional"))
    )
    (net (code "298") (name "unconnected-(U5-RI-Pad2)") (class "Default")
      (node (ref "U5") (pin "2") (pinfunction "RI_2") (pintype "bidirectional"))
    )
    (net (code "299") (name "unconnected-(U5-SUSPEND-Pad12)") (class "Default")
      (node (ref "U5") (pin "12") (pinfunction "SUSPEND_12") (pintype "bidirectional"))
    )
    (net (code "300") (name "unconnected-(U5-VPP-Pad18)") (class "Default")
      (node (ref "U5") (pin "18") (pinfunction "VPP_18") (pintype "bidirectional"))
    )
    (net (code "301") (name "unconnected-(U5-~{SUSPEND}-Pad11)") (class "Default")
      (node (ref "U5") (pin "11") (pinfunction "~{SUSPEND}_11") (pintype "bidirectional"))
    )
    (net (code "302") (name "unconnected-(U8-NC-Pad4)") (class "Default")
      (node (ref "U8") (pin "4") (pinfunction "NC_4") (pintype "bidirectional"))
    )
    (net (code "303") (name "unconnected-(U9-NC-Pad4)") (class "Default")
      (node (ref "U9") (pin "4") (pinfunction "NC_4") (pintype "bidirectional"))
    )
    (net (code "304") (name "unconnected-(U10-ADC6-Pad32)") (class "Default")
      (node (ref "U10") (pin "32") (pinfunction "ADC6_32") (pintype "bidirectional"))
    )
    (net (code "305") (name "unconnected-(U10-ADC7-Pad31)") (class "Default")
      (node (ref "U10") (pin "31") (pinfunction "ADC7_31") (pintype "bidirectional"))
    )
    (net (code "306") (name "unconnected-(U10-AREF-Pad16)") (class "Default")
      (node (ref "U10") (pin "16") (pinfunction "AREF_16") (pintype "bidirectional"))
    )
    (net (code "307") (name "unconnected-(U12-INT1-Pad4)") (class "Default")
      (node (ref "U12") (pin "4") (pinfunction "INT1_4") (pintype "bidirectional"))
    )
    (net (code "308") (name "unconnected-(U12-NC-Pad11)") (class "Default")
      (node (ref "U12") (pin "11") (pinfunction "NC_11") (pintype "bidirectional"))
    )
    (net (code "309") (name "unconnected-(U12-OCS-Pad10)") (class "Default")
      (node (ref "U12") (pin "10") (pinfunction "OCS_10") (pintype "bidirectional"))
    )
    (net (code "310") (name "unconnected-(U17-NC-Pad6)") (class "Default")
      (node (ref "U17") (pin "6") (pinfunction "NC_6") (pintype "bidirectional"))
    )
    (net (code "311") (name "unconnected-(U17-NC-Pad9)") (class "Default")
      (node (ref "U17") (pin "9") (pinfunction "NC_9") (pintype "bidirectional"))
    )
    (net (code "312") (name "unconnected-(U18-NC-Pad6)") (class "Default")
      (node (ref "U18") (pin "6") (pinfunction "NC_6") (pintype "bidirectional"))
    )
    (net (code "313") (name "unconnected-(U18-NC-Pad9)") (class "Default")
      (node (ref "U18") (pin "9") (pinfunction "NC_9") (pintype "bidirectional"))
    )
    (net (code "314") (name "unconnected-(USB2-A8{slash}SBU1-PadA8)") (class "Default")
      (node (ref "USB2") (pin "A8") (pinfunction "A8/SBU1_A8") (pintype "bidirectional"))
    )
    (net (code "315") (name "unconnected-(USB2-B8{slash}SBU2-PadB8)") (class "Default")
      (node (ref "USB2") (pin "B8") (pinfunction "B8/SBU2_B8") (pintype "bidirectional"))
    )
    (net (code "316") (name "unconnected-(USB2-PadS3)") (class "Default")
      (node (ref "USB2") (pin "S3") (pinfunction "S3_S3") (pintype "bidirectional"))
    )
    (net (code "317") (name "unconnected-(USB2-PadS4)") (class "Default")
      (node (ref "USB2") (pin "S4") (pinfunction "S4_S4") (pintype "bidirectional"))
    )
  )
)
